# PCB_KioskMB_r3_4-01.net
KiCad netlist of a schematic drawn in EAGLE
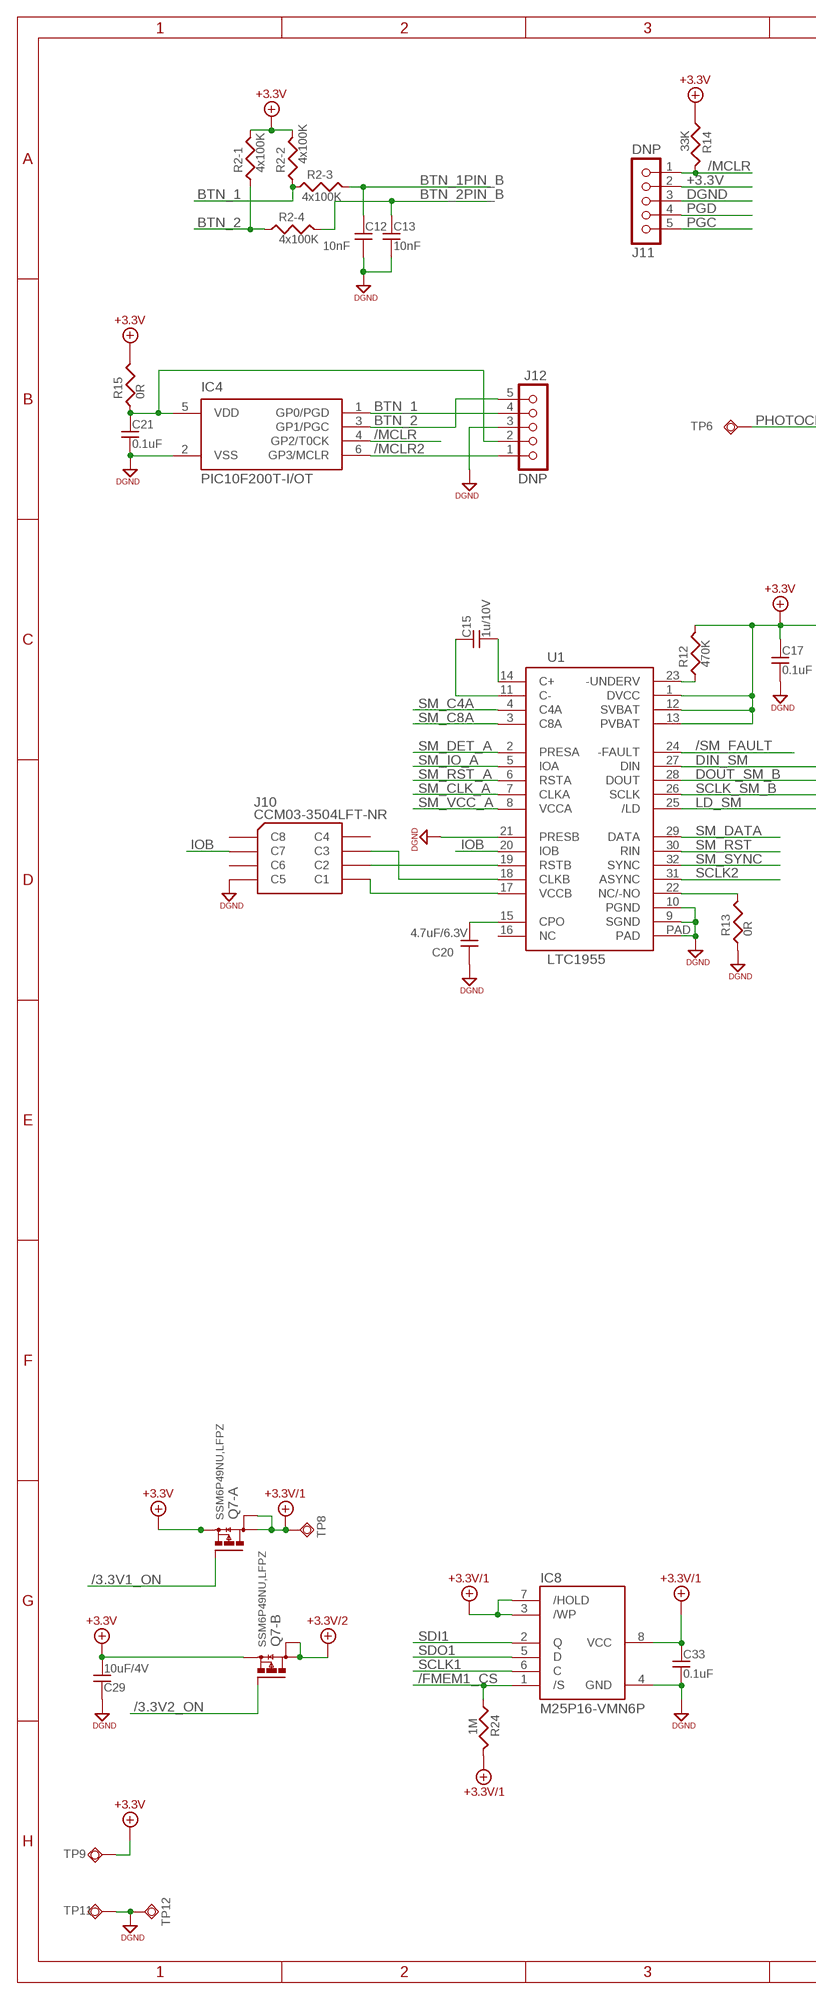
[diagram p0: schematic, sheet 1, part 1 of 2]
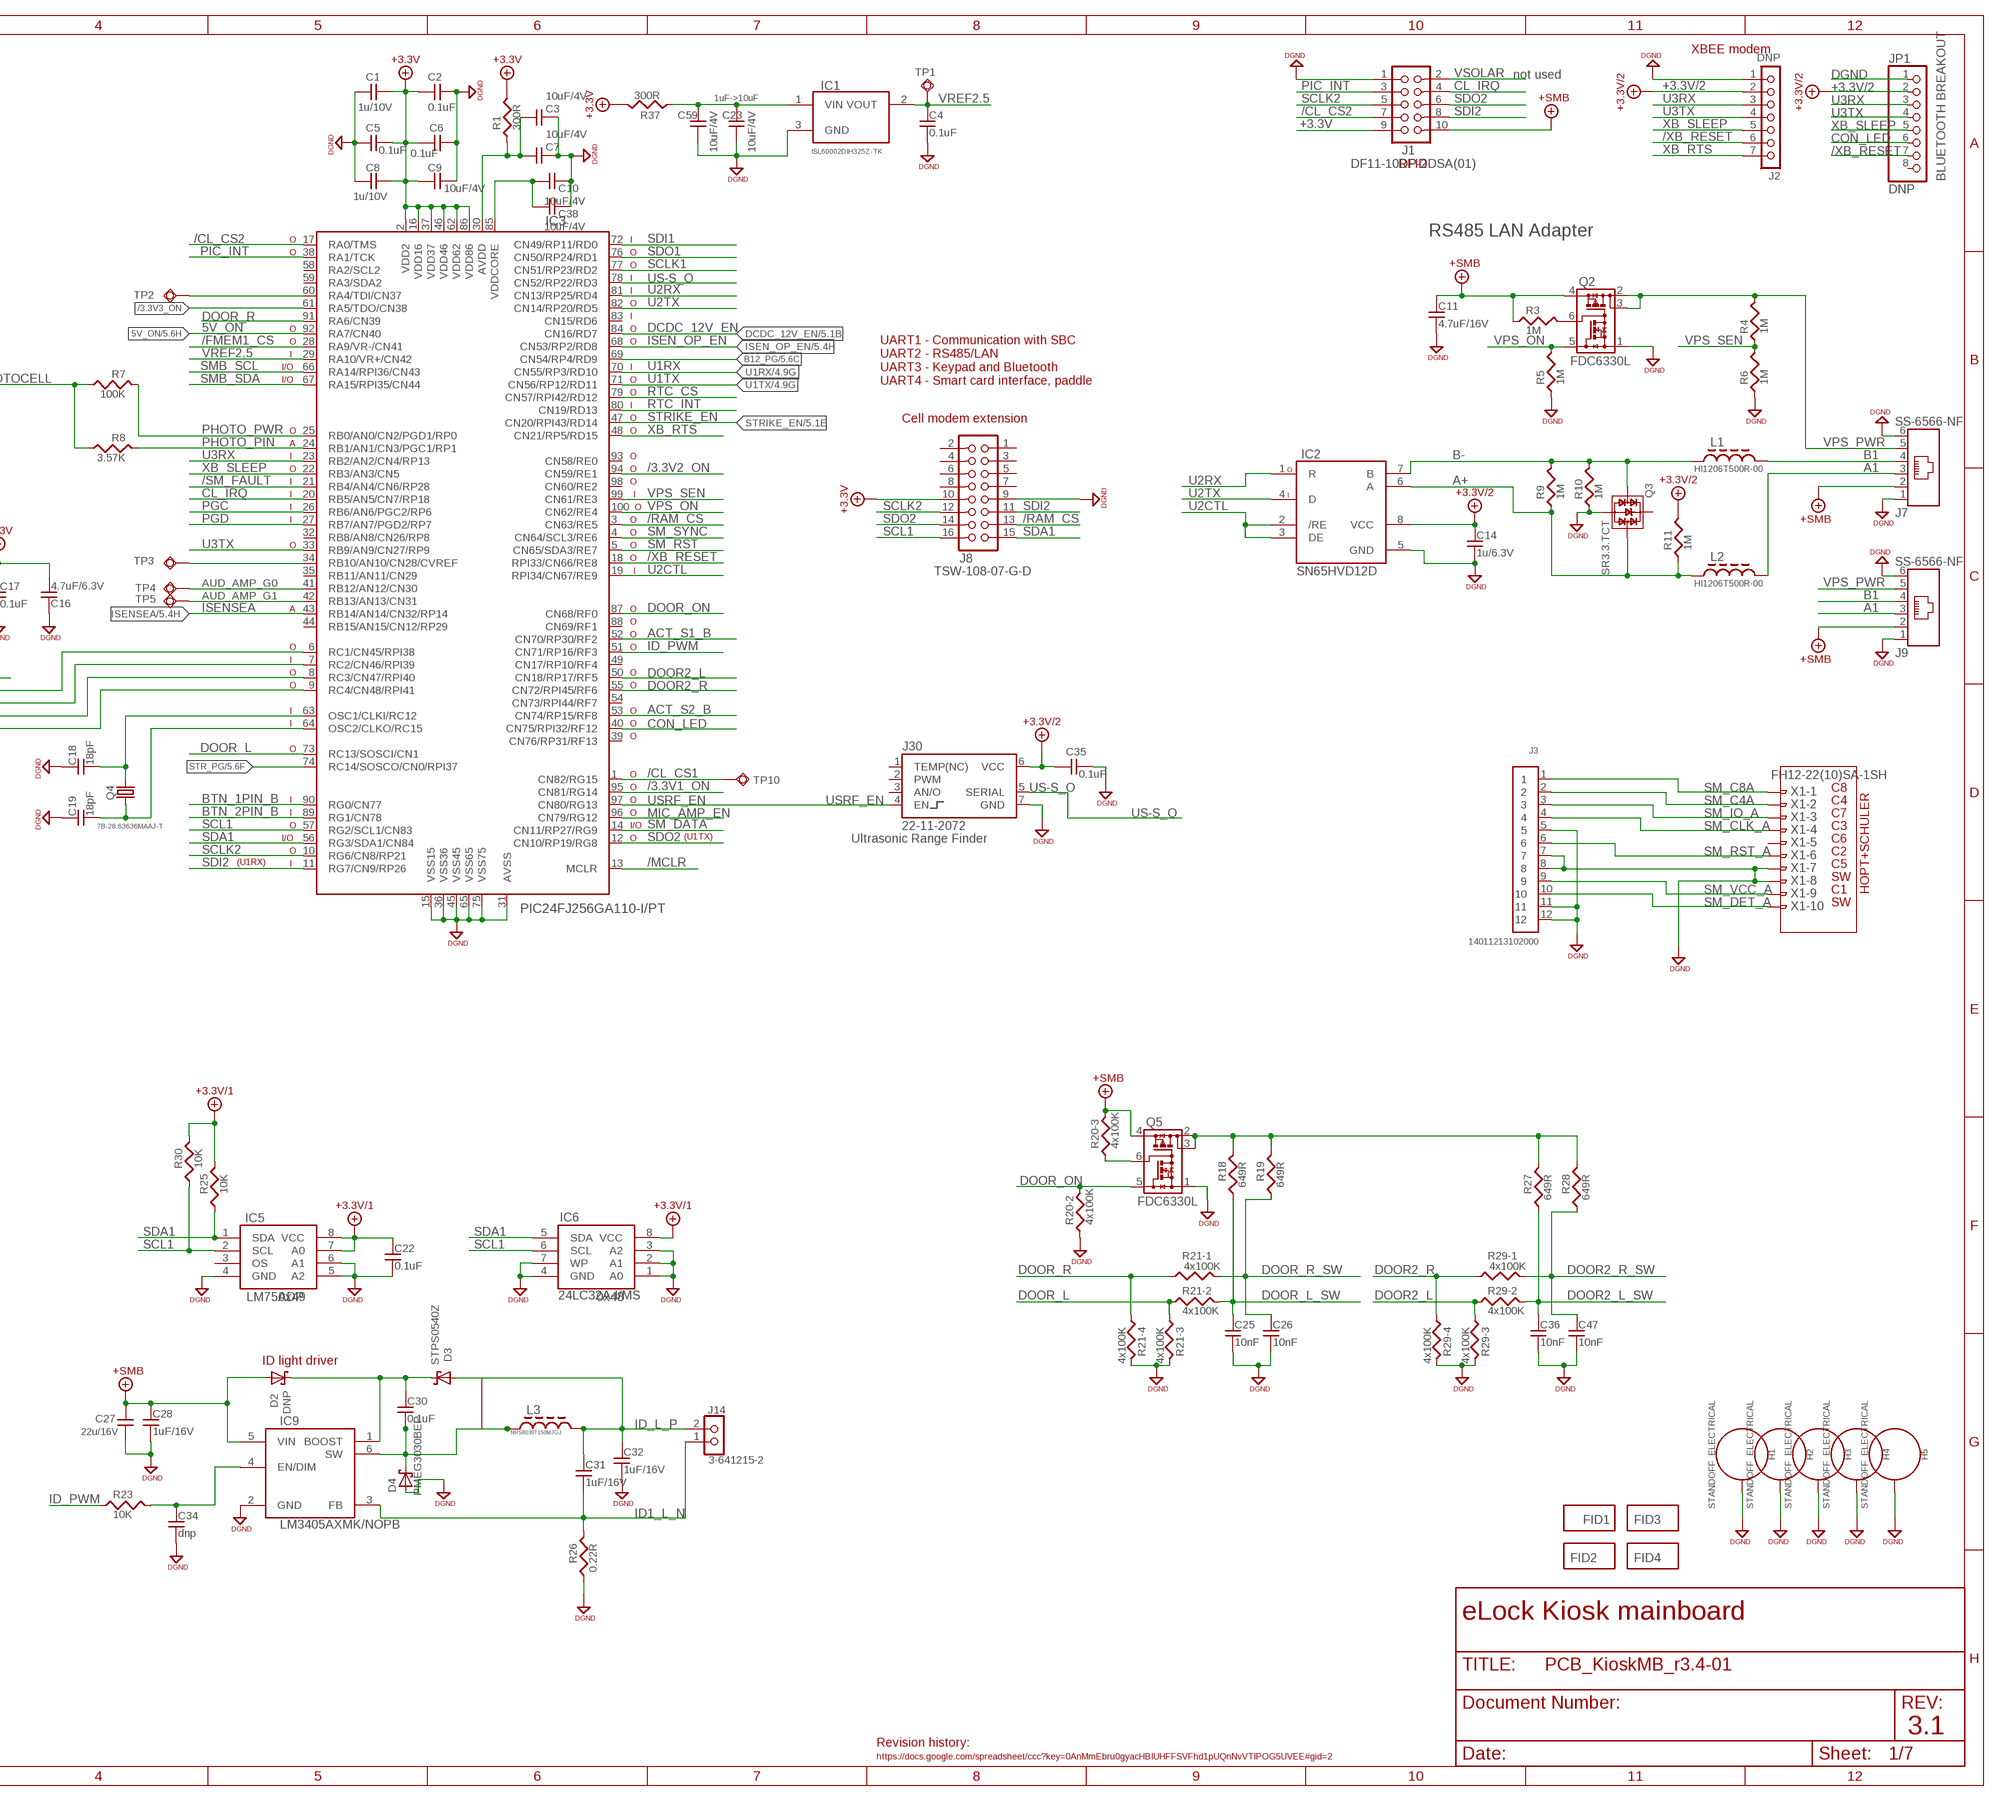
[diagram p1: schematic, sheet 1, part 2 of 2]
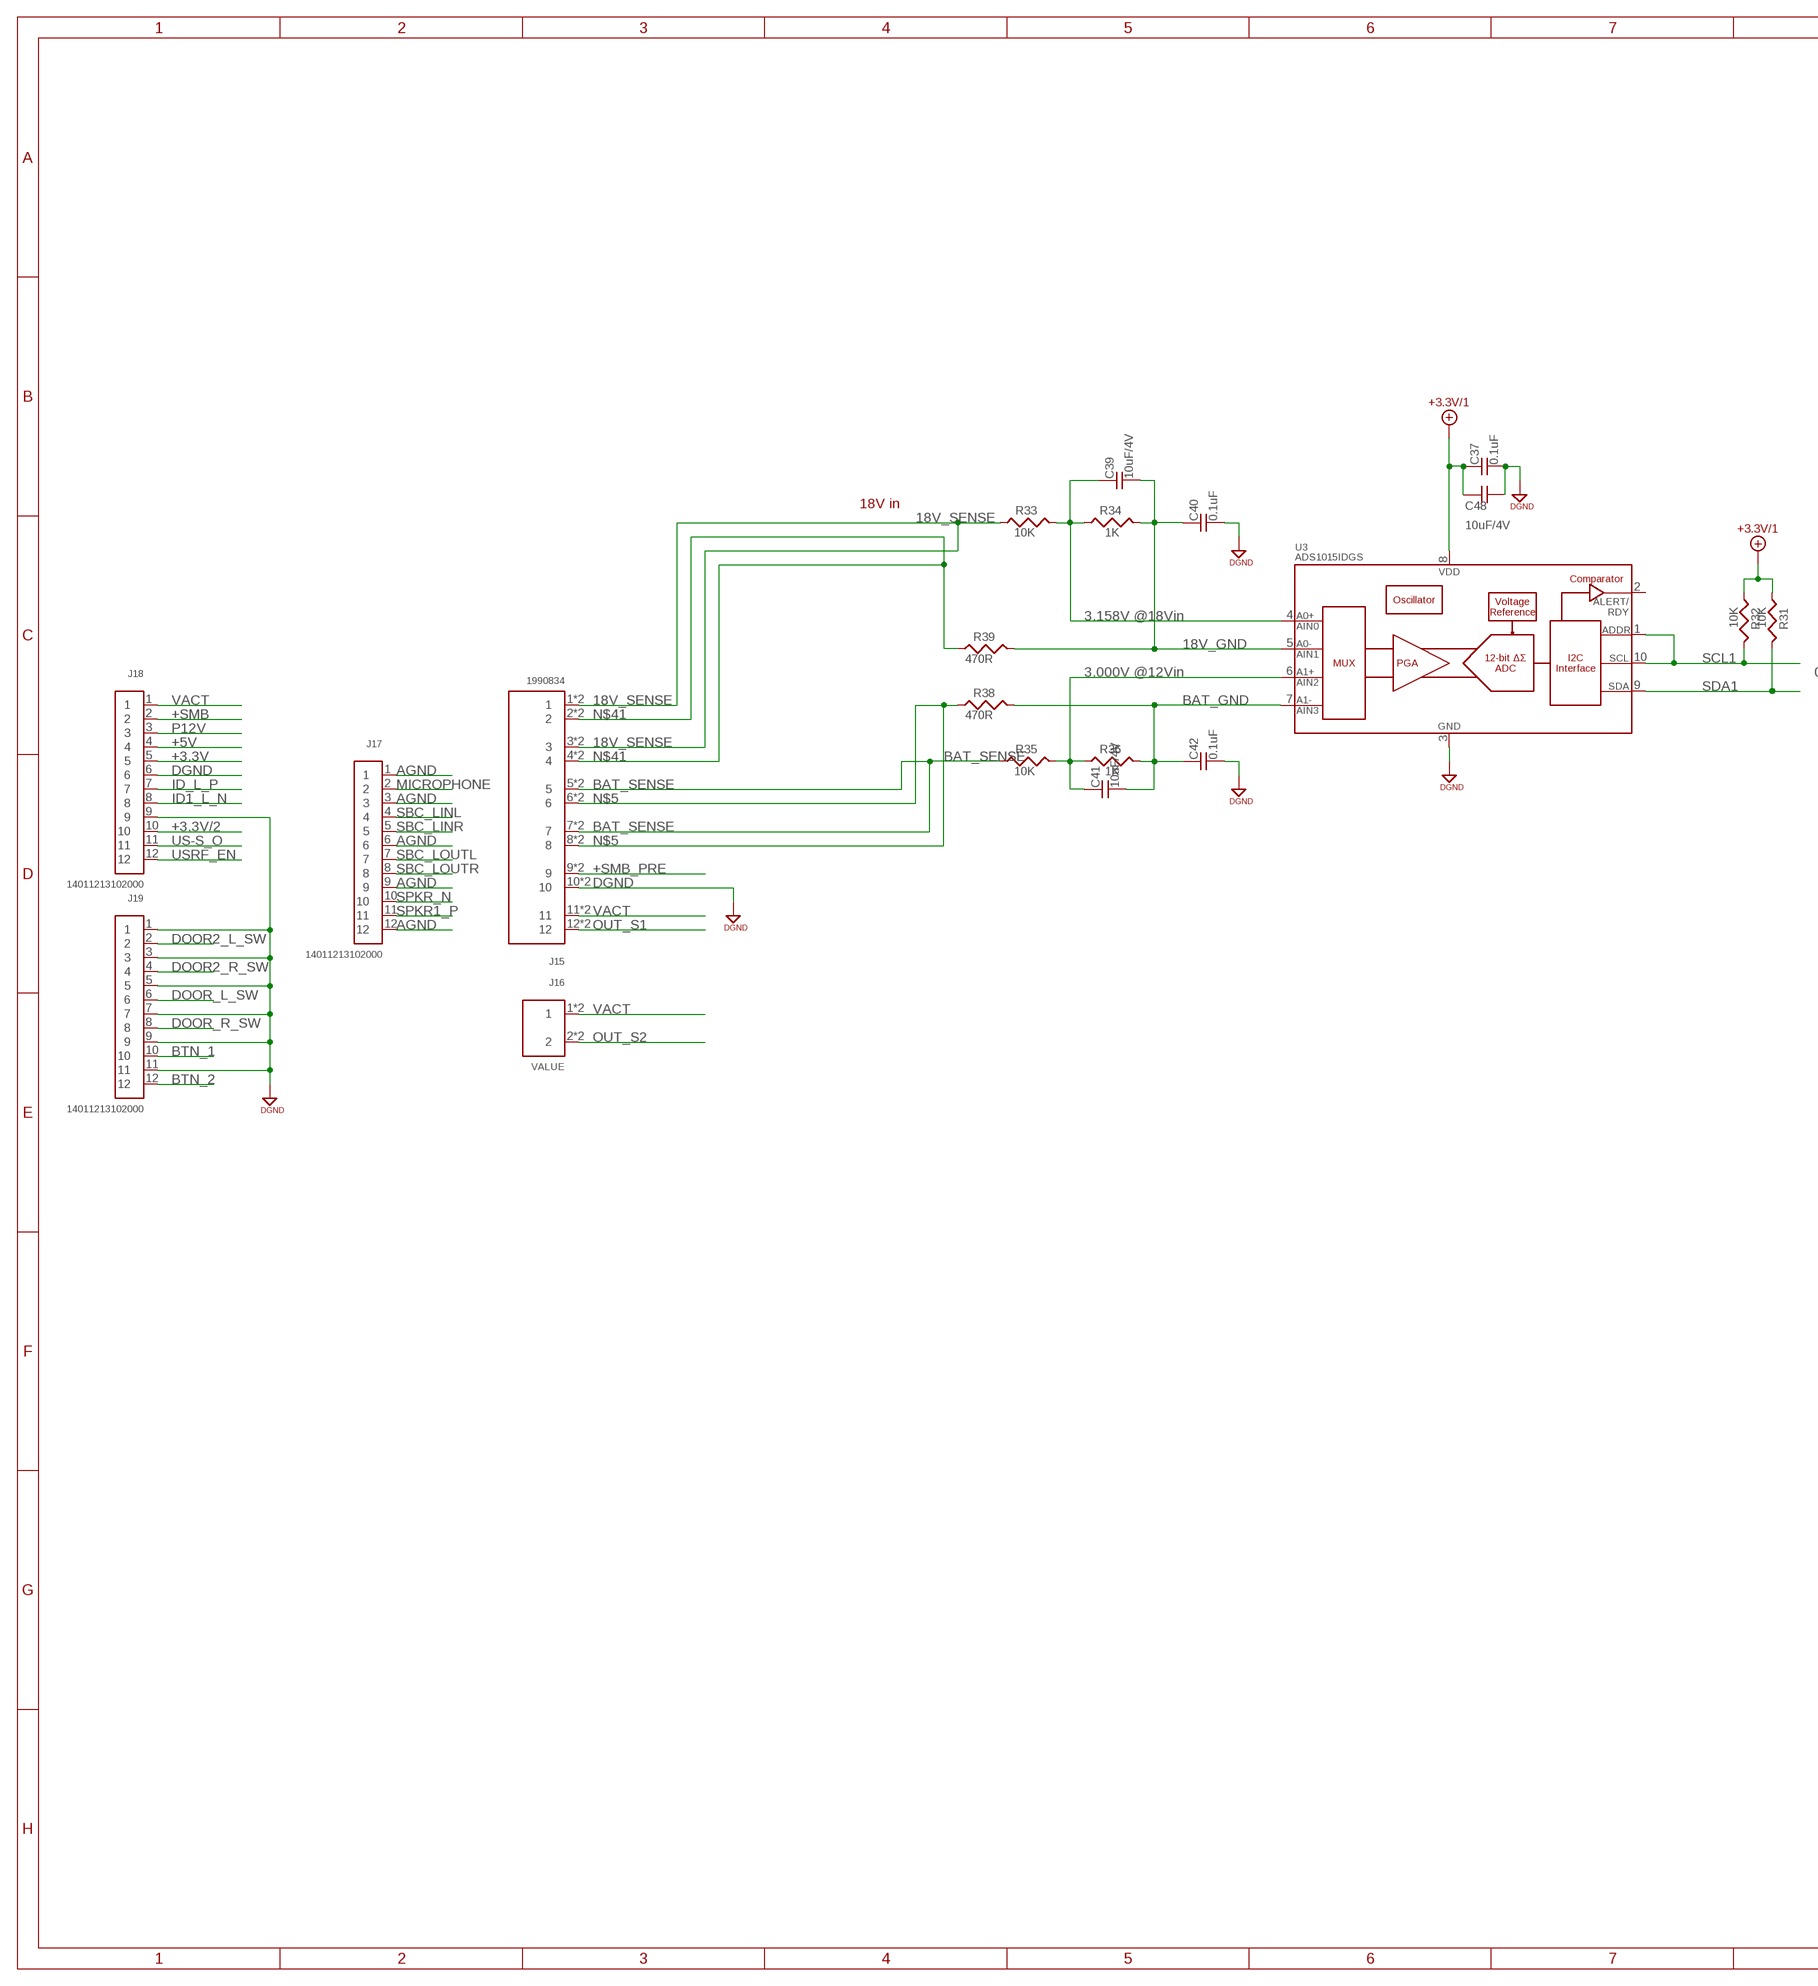
[diagram p2: schematic, sheet 2, part 1 of 2]
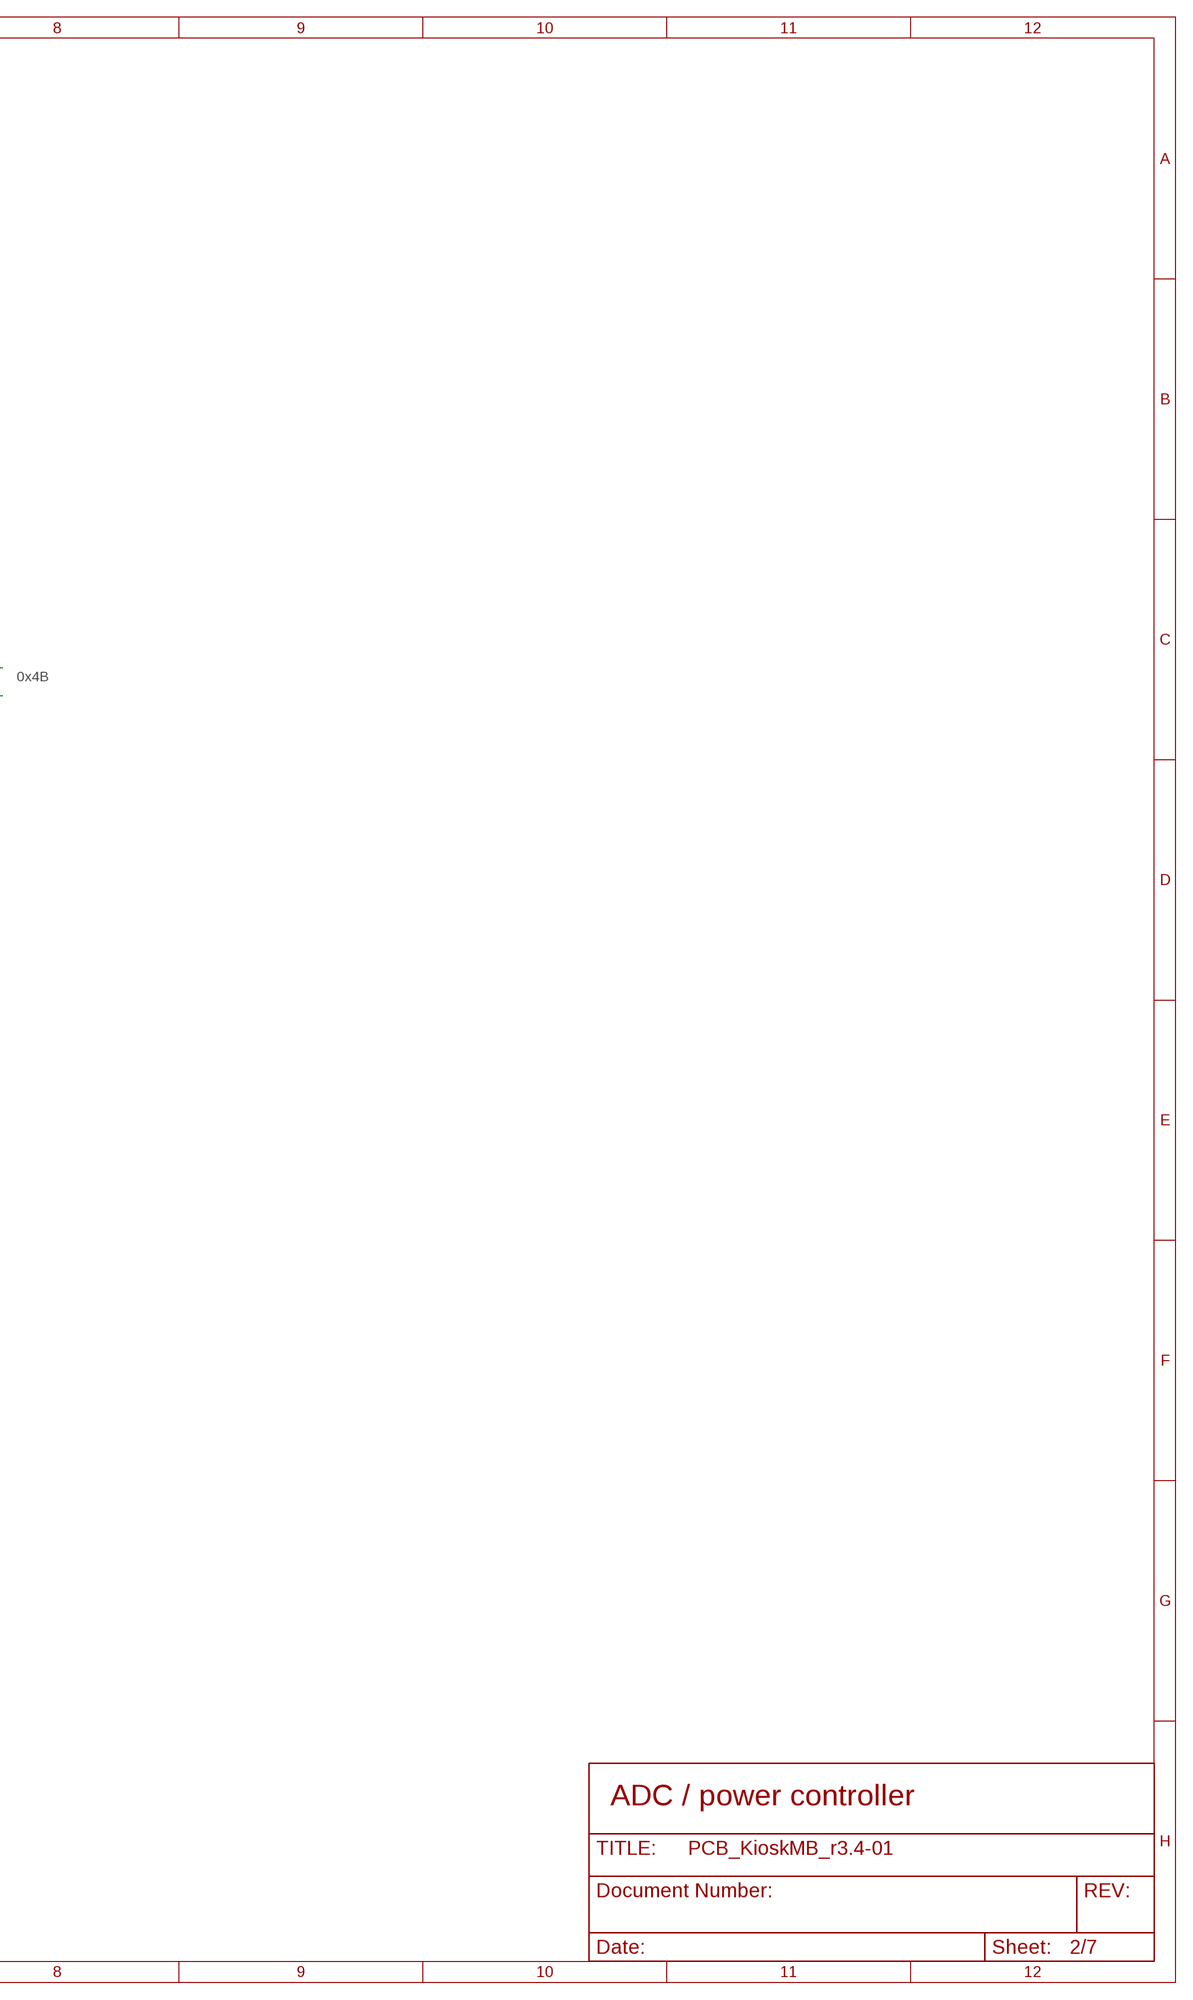
[diagram p3: schematic, sheet 2, part 2 of 2]
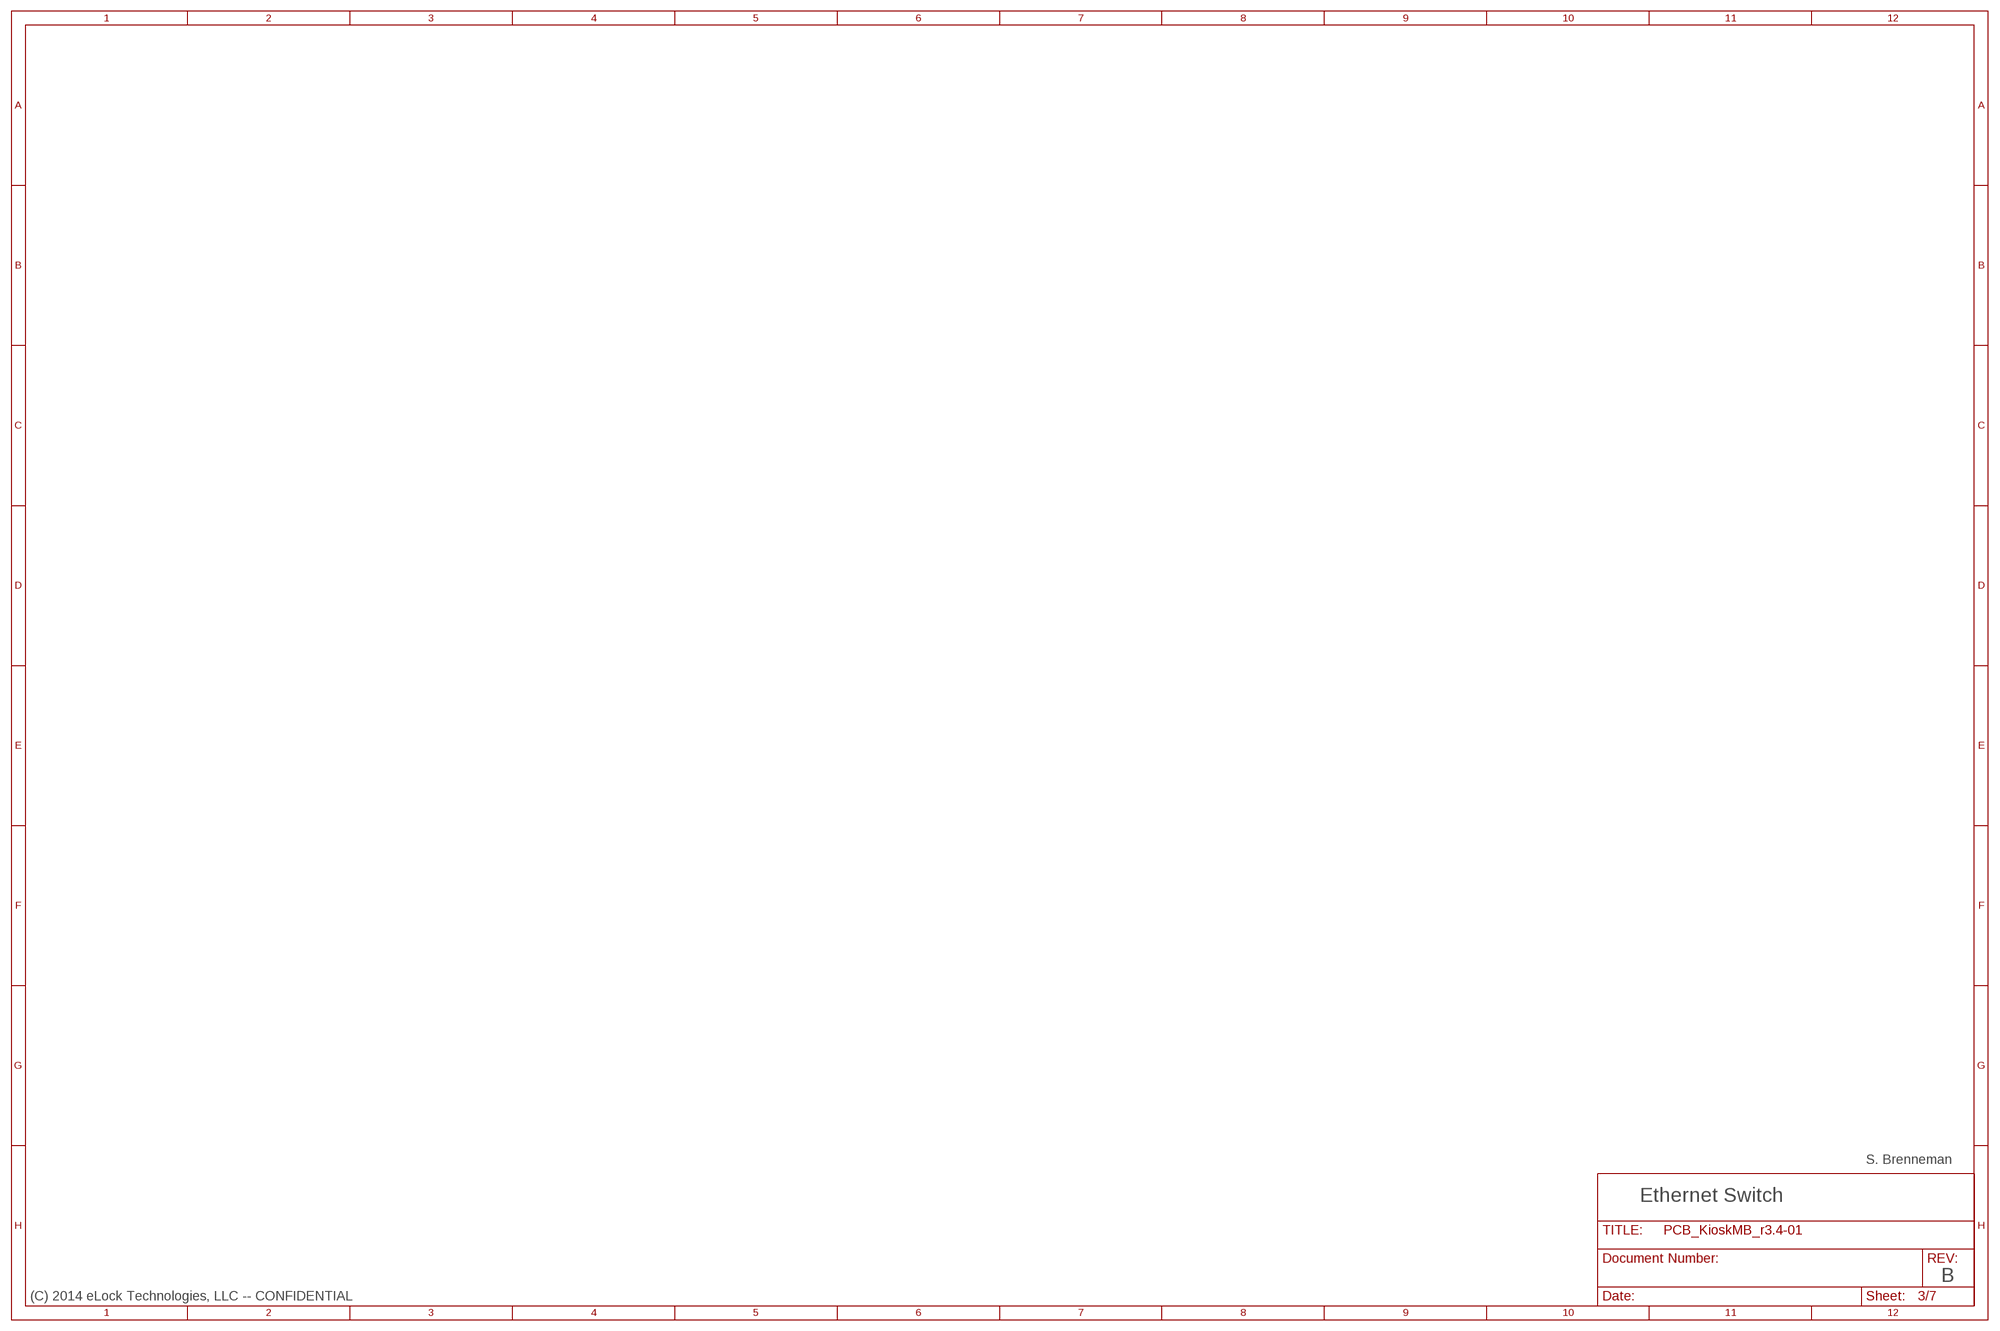
[diagram p4: schematic, sheet 3]
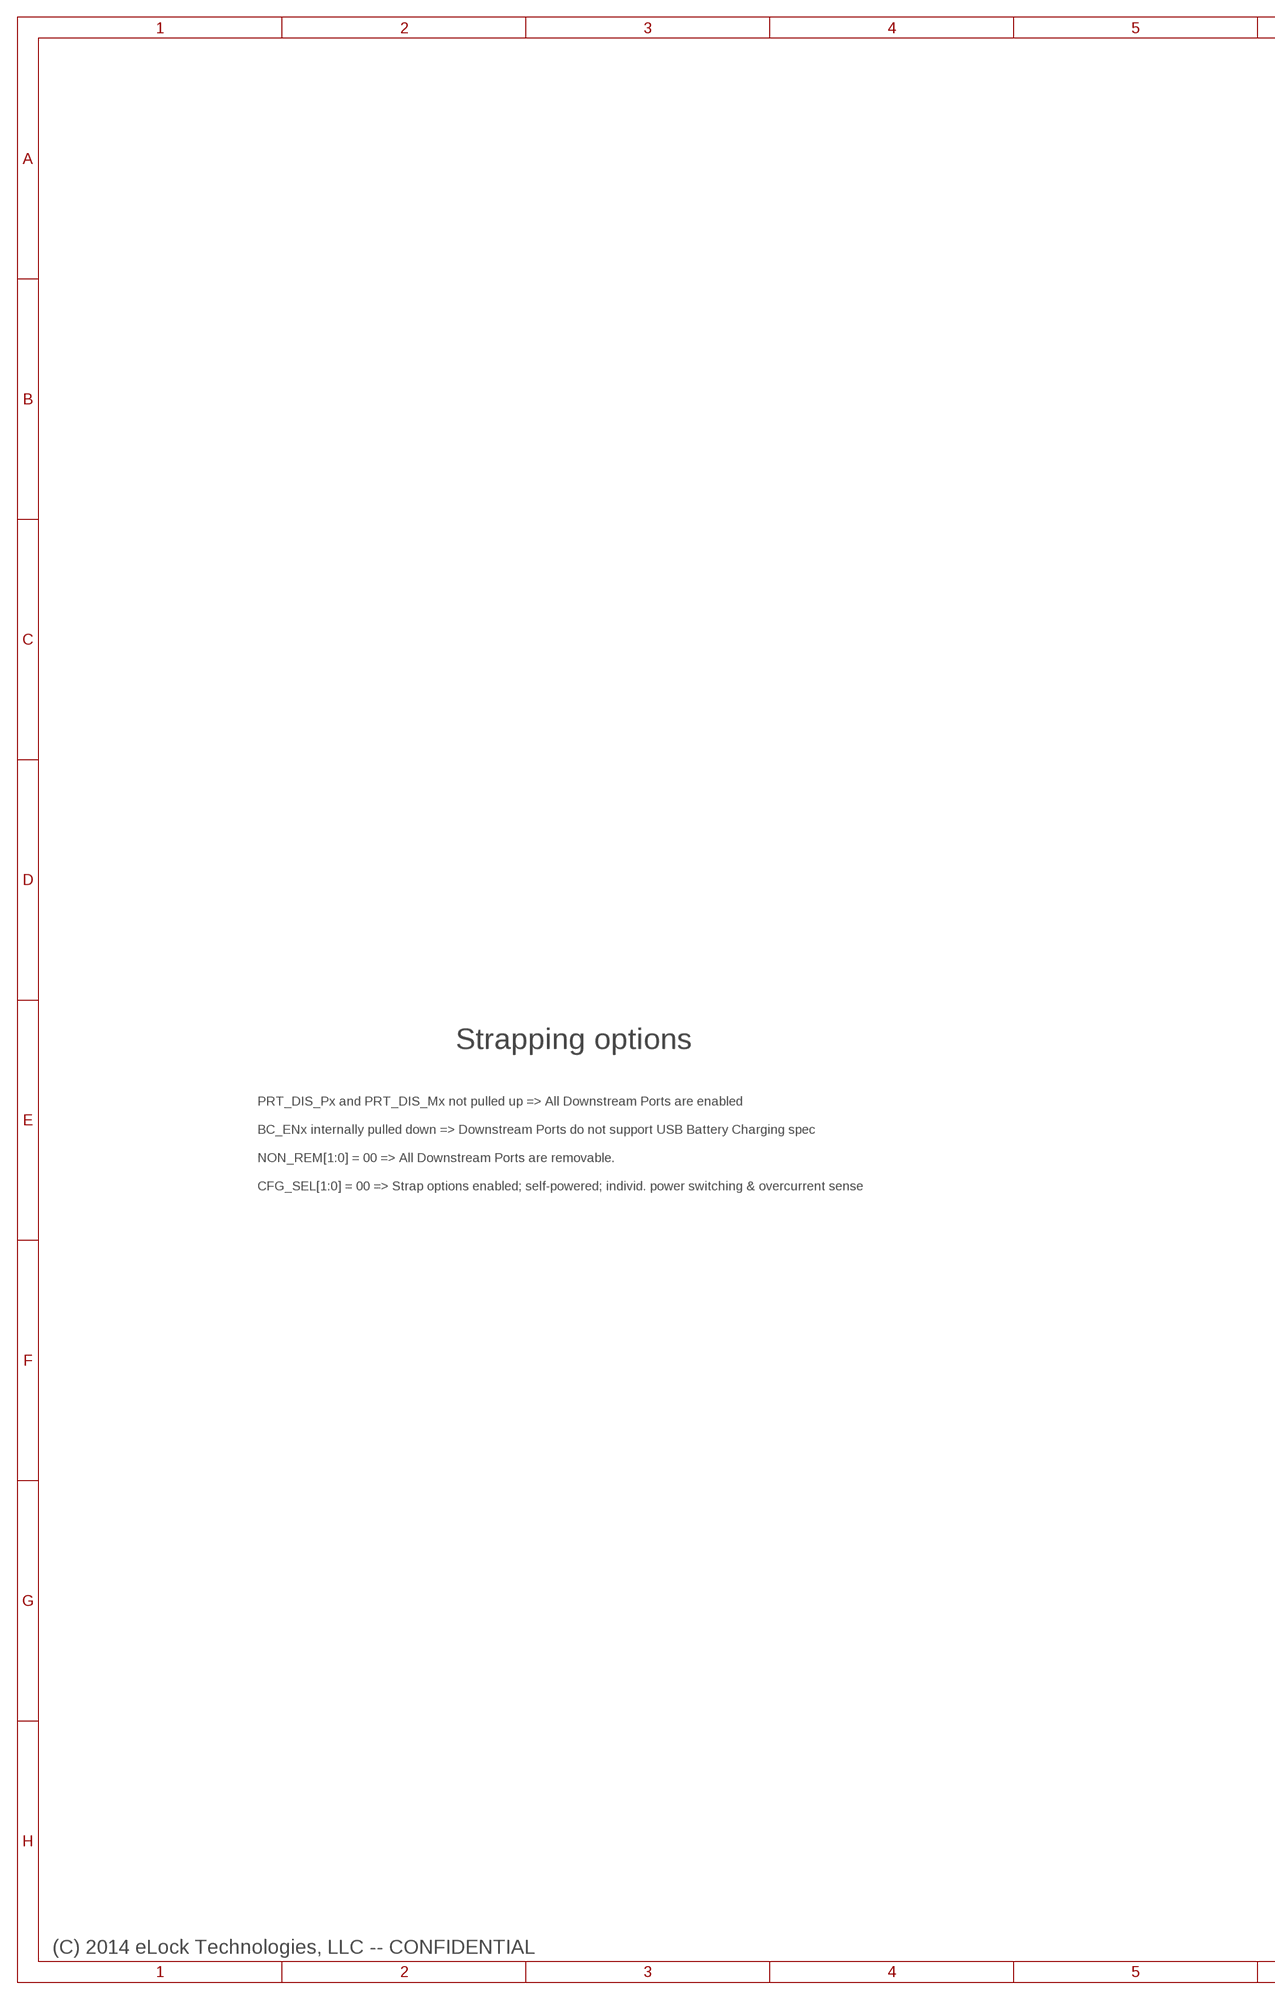
[diagram p5: schematic, sheet 4, part 1 of 2]
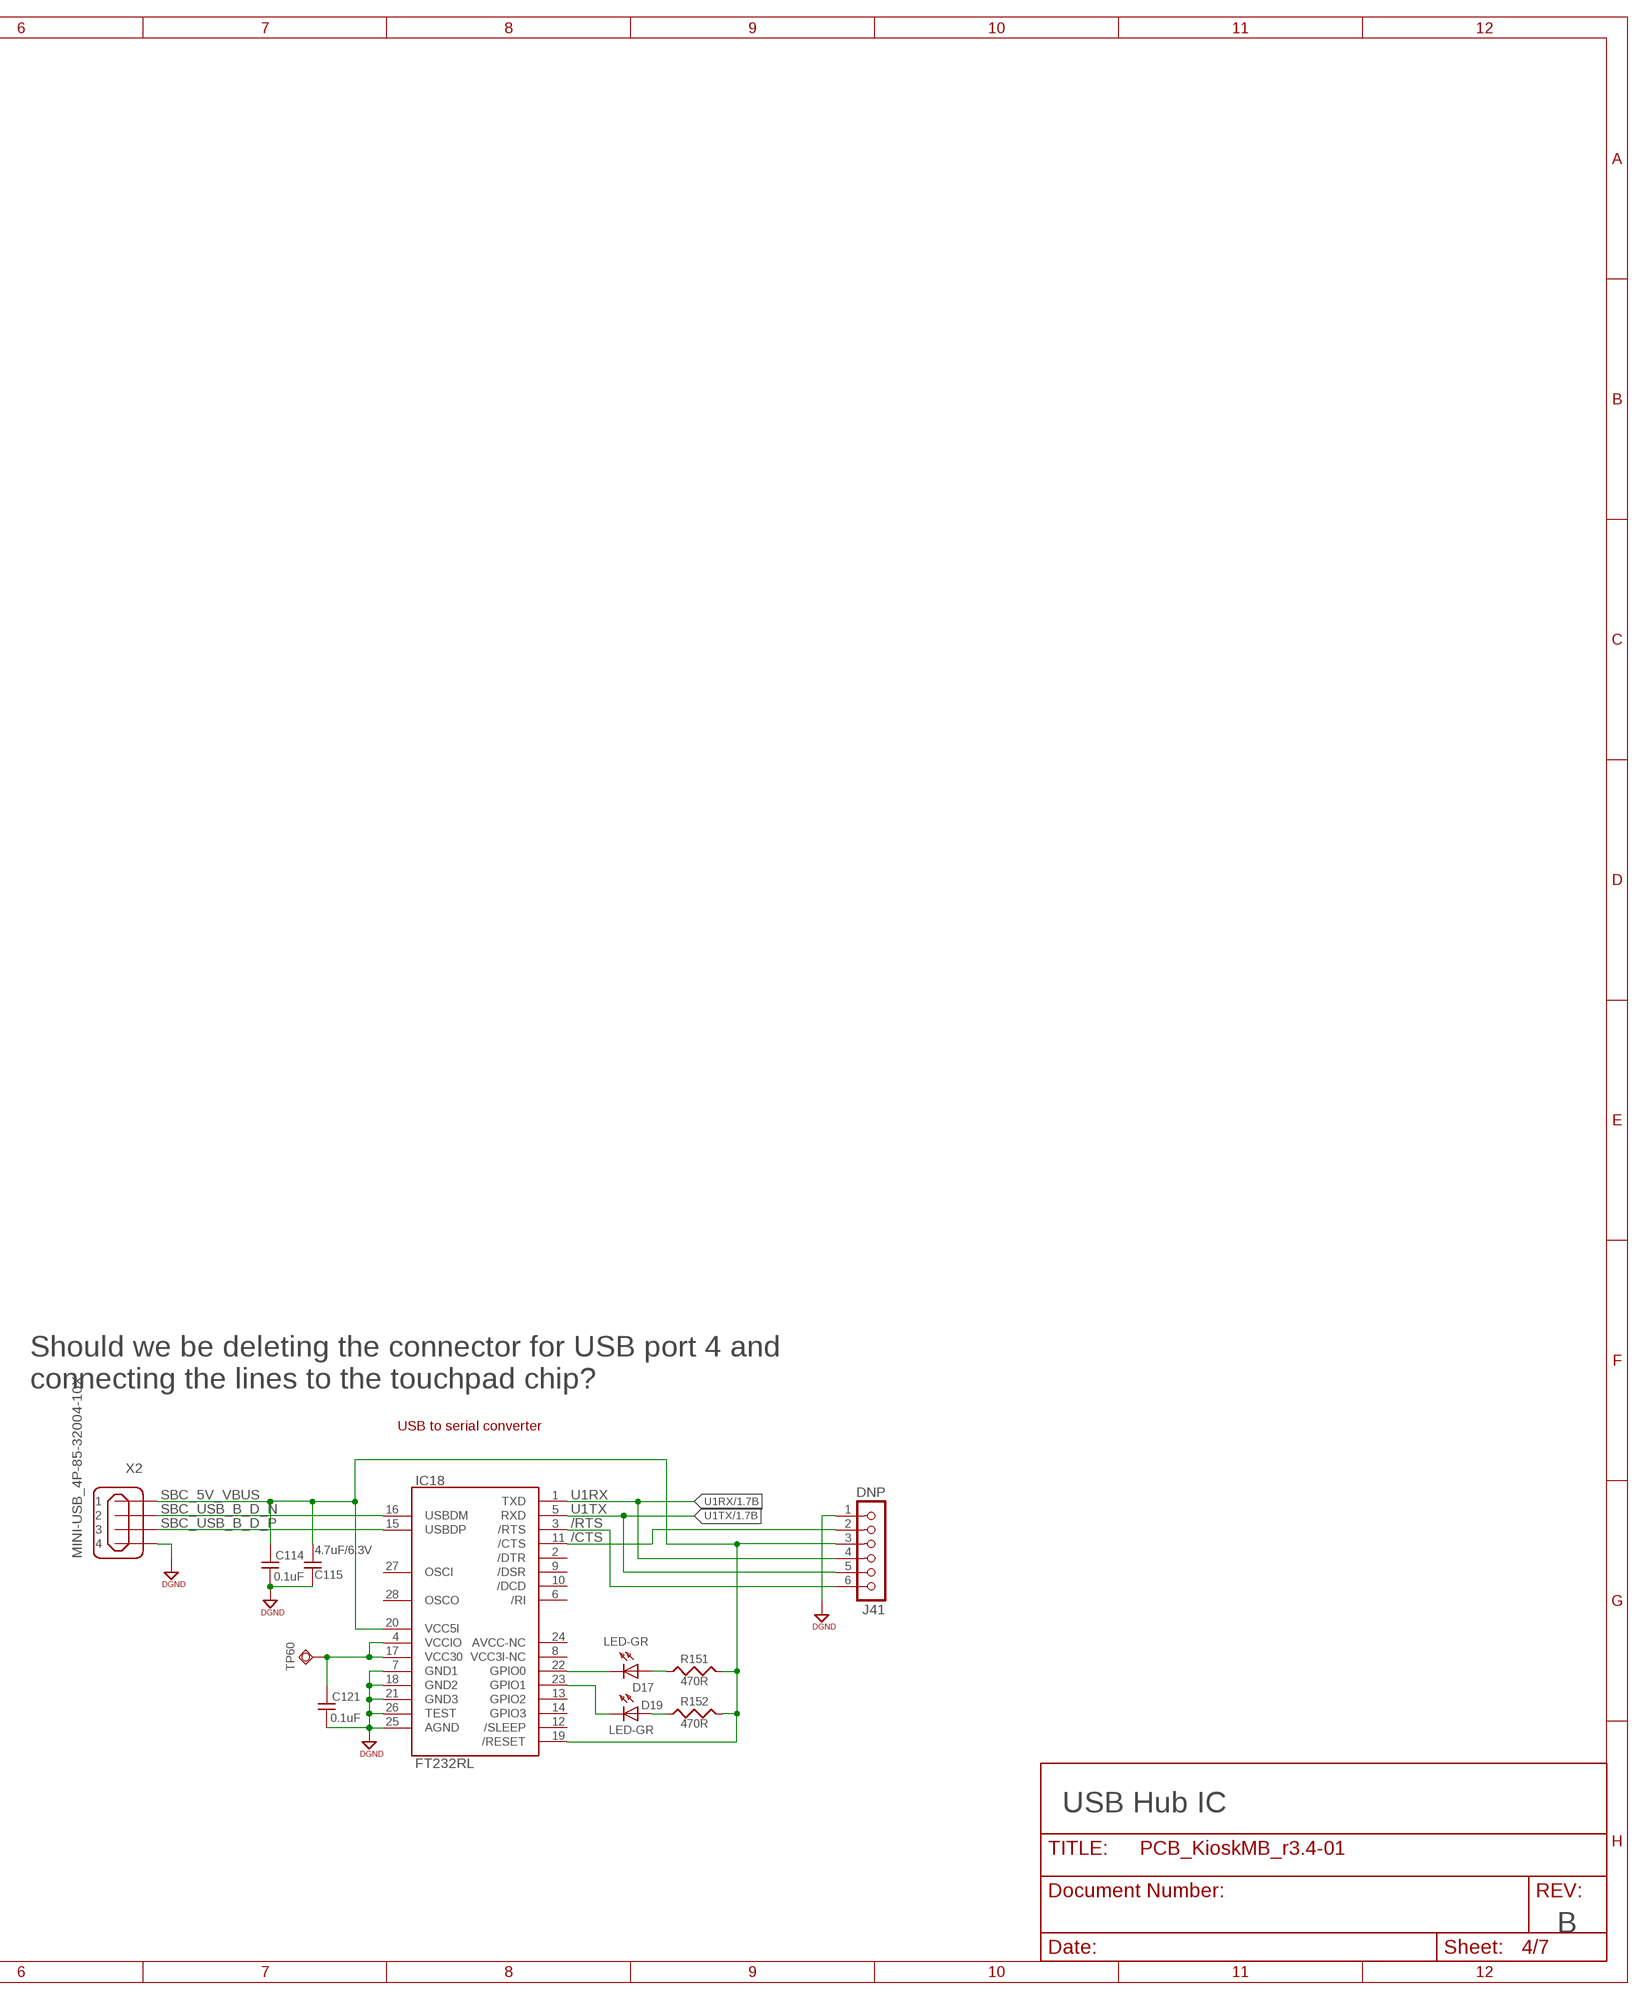
[diagram p6: schematic, sheet 4, part 2 of 2]
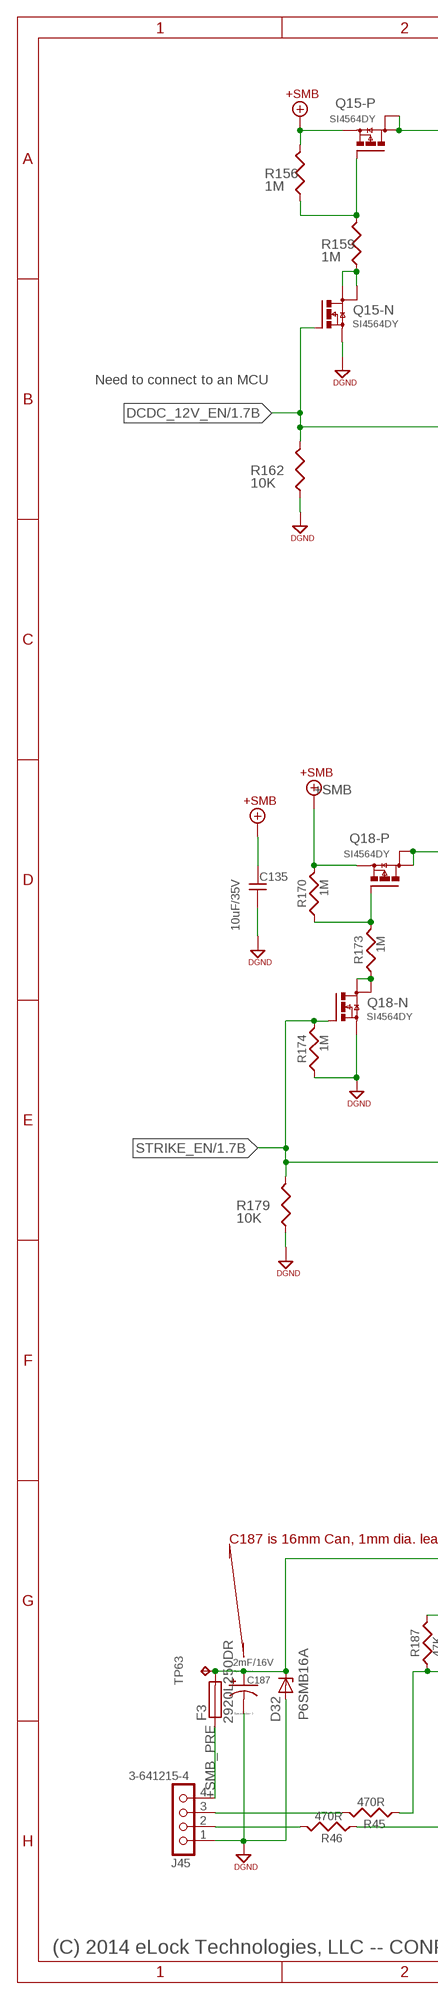
[diagram p7: schematic, sheet 5, part 1 of 2]
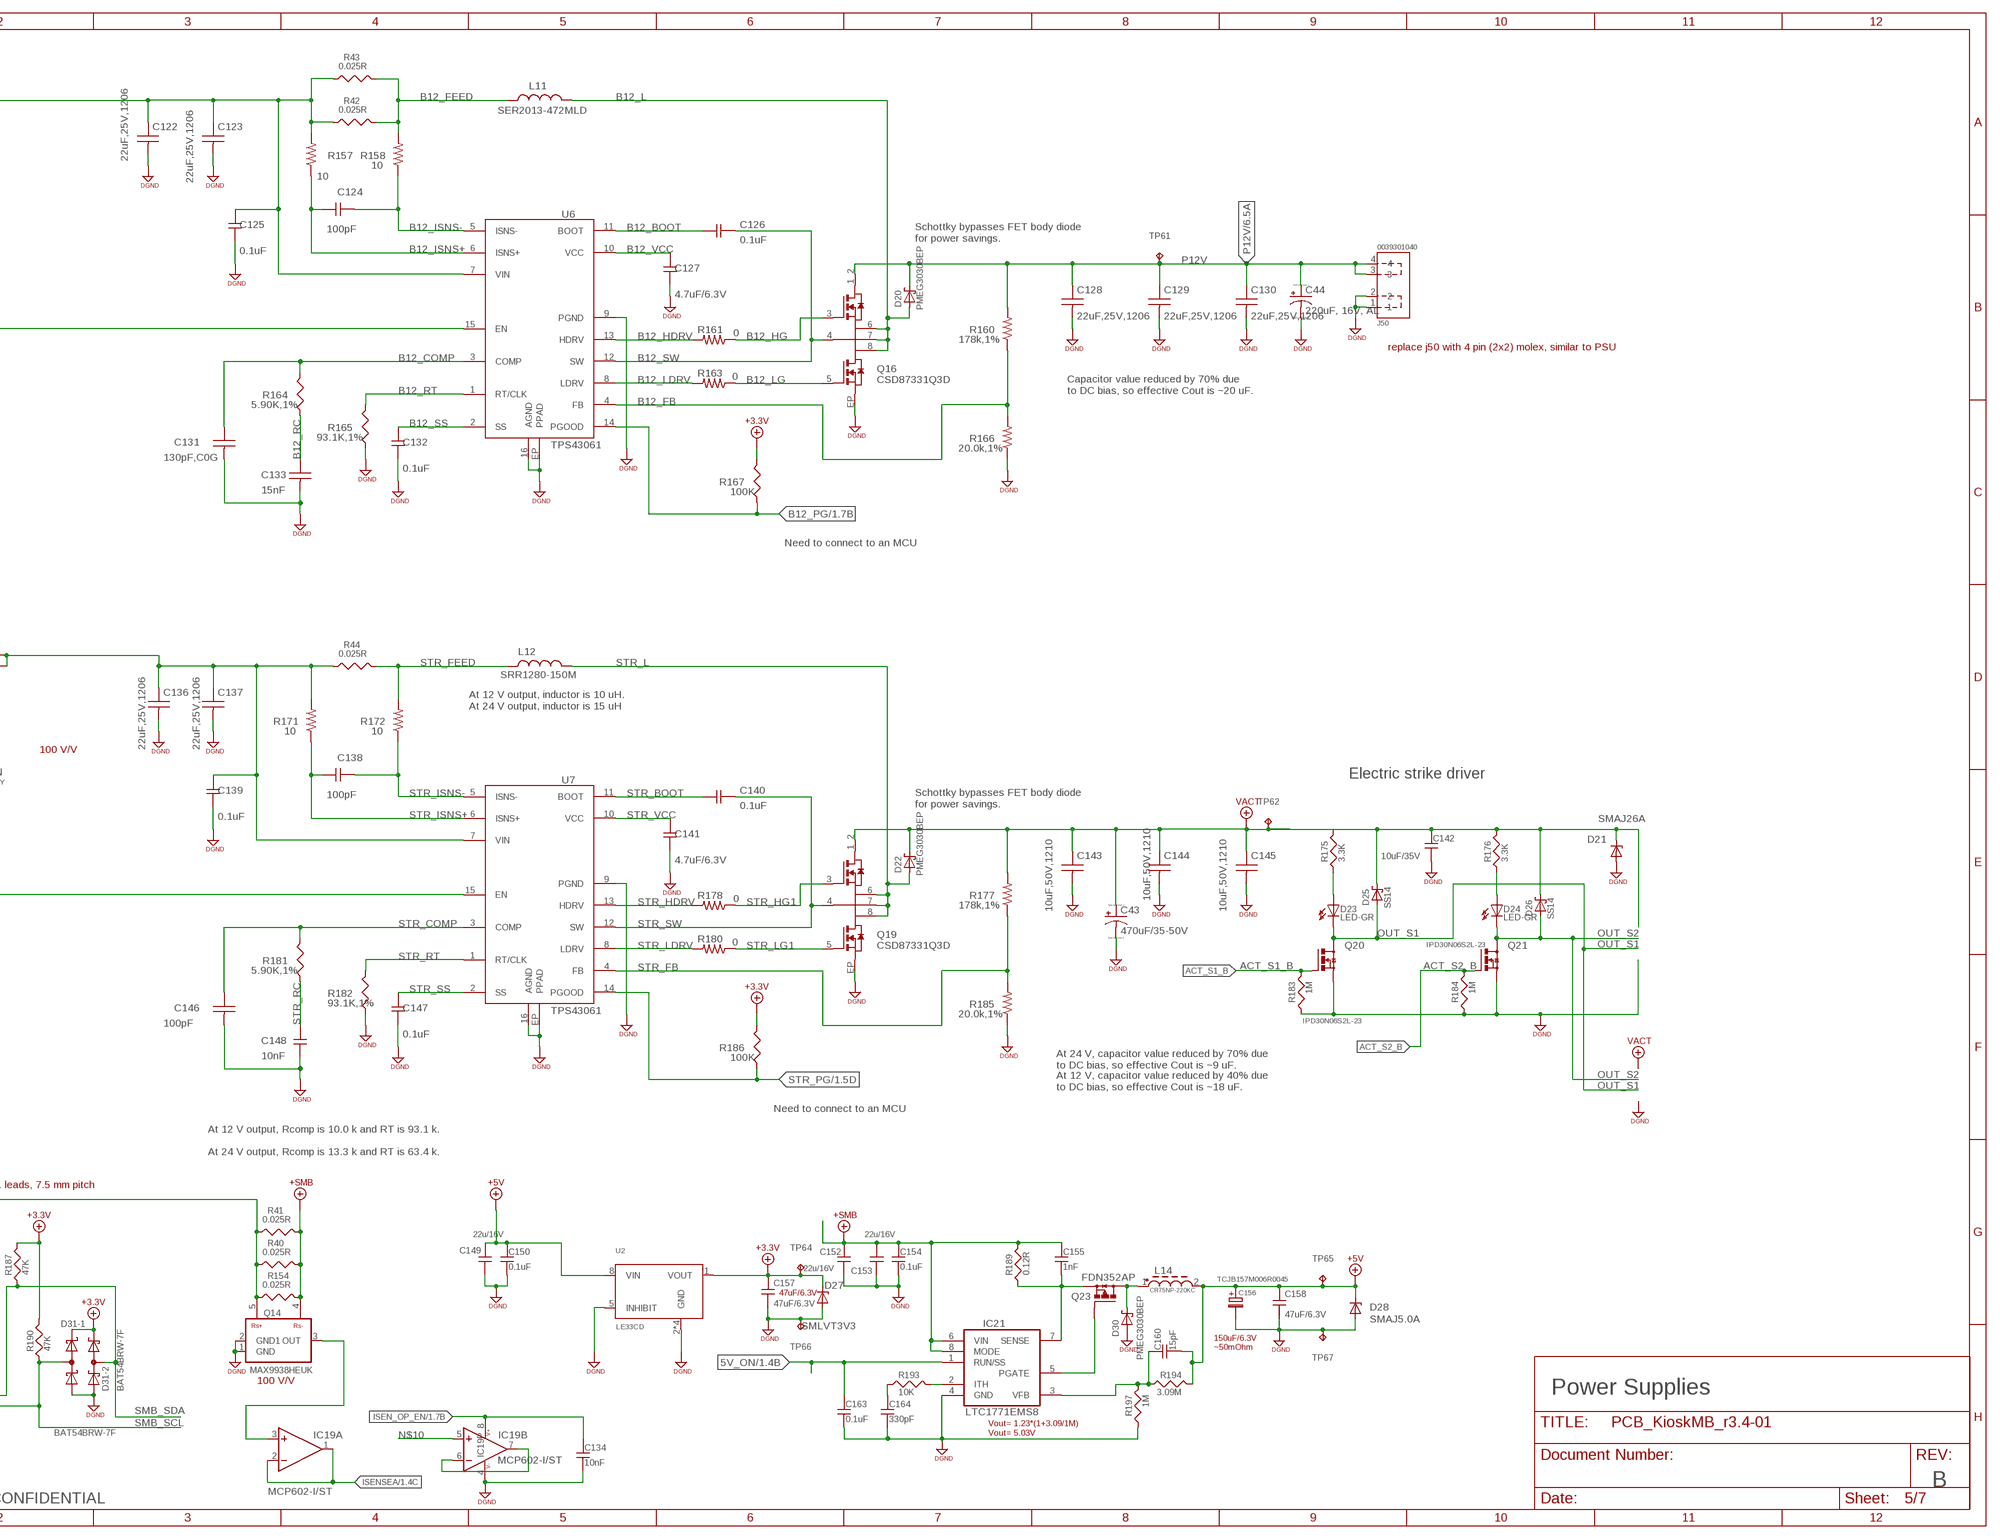
[diagram p8: schematic, sheet 5, part 2 of 2]
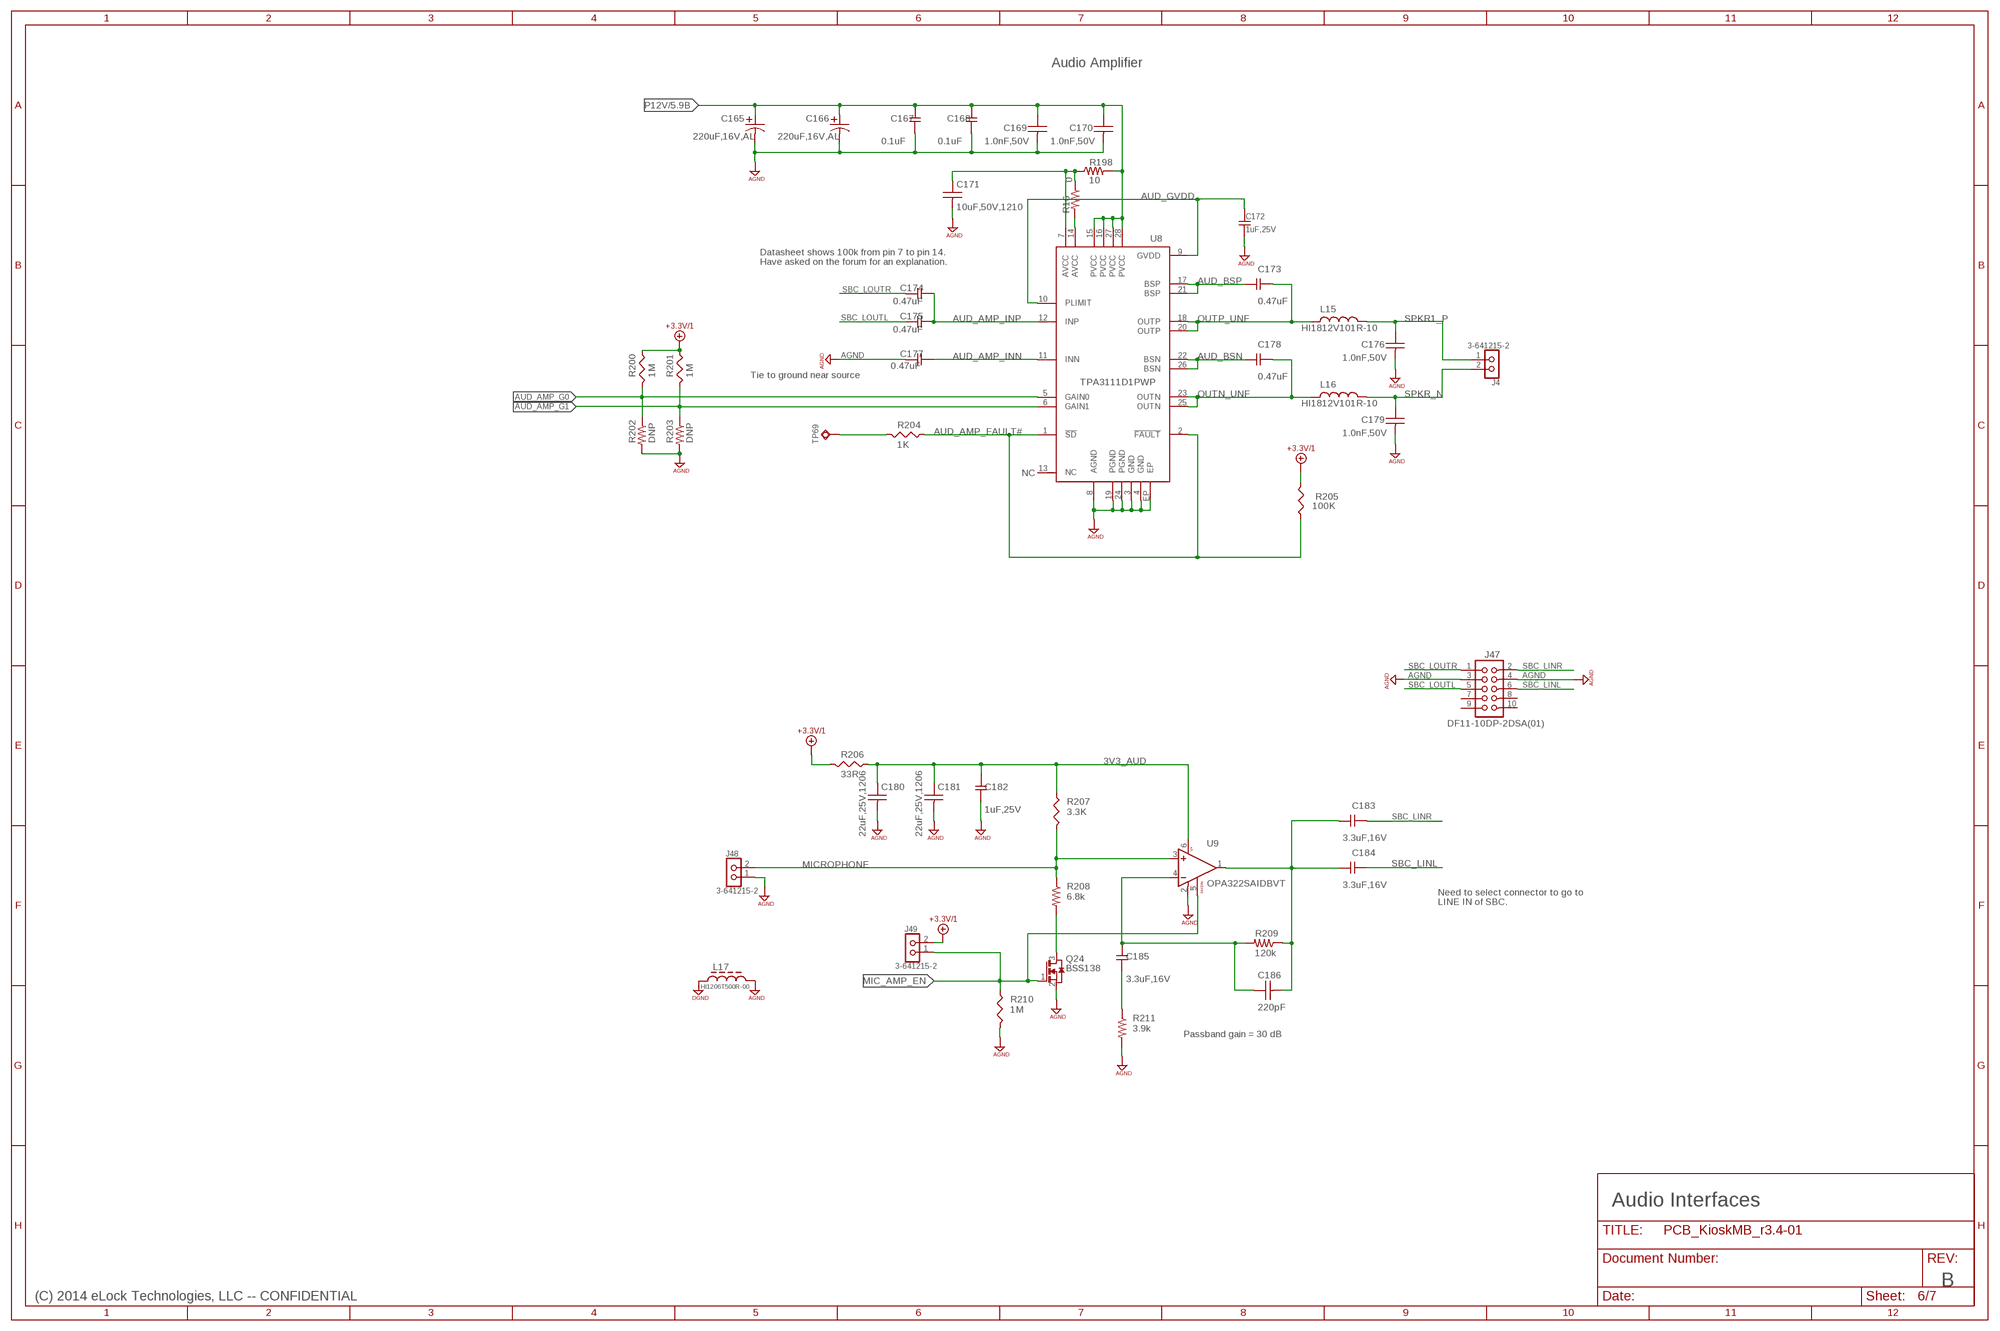
[diagram p9: schematic, sheet 6]
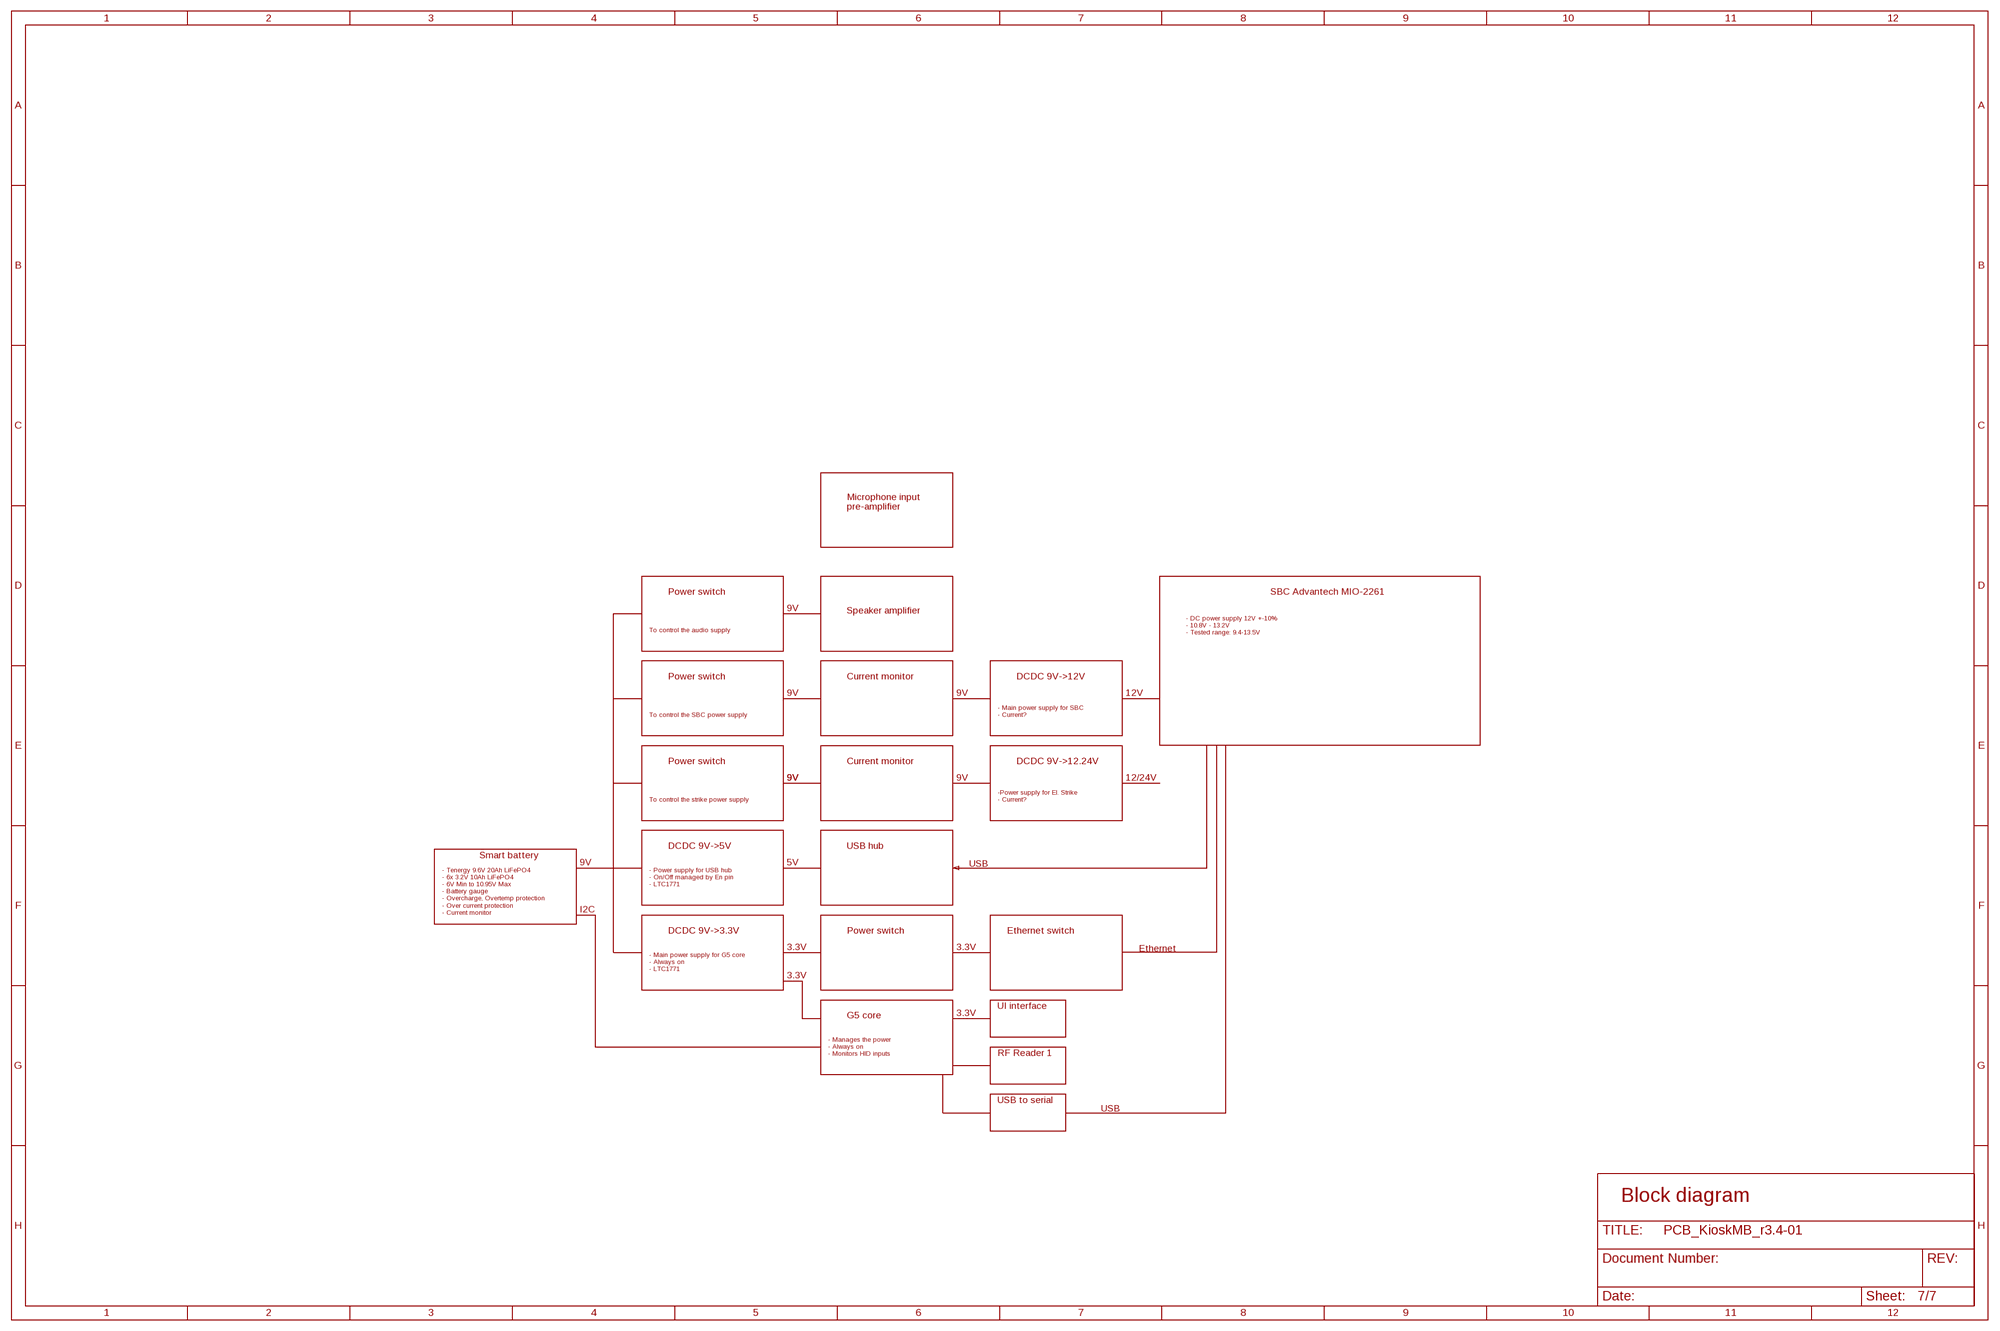
[diagram p10: schematic, sheet 7]

(export (version "E")
  (design (tool "Eeschema 10.0.6"))
  (components
    (comp (ref "C114")
      (value "0.1uF")
      (footprint "eagle-import:0603")
      (libsource (lib "eagle-import") (part "discrete_211_C-0603"))
    )
    (comp (ref "C115")
      (value "4.7uF/6.3V")
      (footprint "eagle-import:0603")
      (libsource (lib "eagle-import") (part "discrete_211_C-0603"))
    )
    (comp (ref "C121")
      (value "0.1uF")
      (footprint "eagle-import:0603")
      (libsource (lib "eagle-import") (part "discrete_211_C-0603"))
    )
    (comp (ref "D17")
      (value "LED-GR")
      (footprint "eagle-import:0805-POL")
      (libsource (lib "eagle-import") (part "LED-0805"))
    )
    (comp (ref "D19")
      (value "LED-GR")
      (footprint "eagle-import:0805-POL")
      (libsource (lib "eagle-import") (part "LED-0805"))
    )
    (comp (ref "IC18")
      (value "FT232RL")
      (footprint "eagle-import:SSOP28DB")
      (libsource (lib "eagle-import") (part "FT232RL"))
    )
    (comp (ref "J41")
      (value "DNP")
      (footprint "eagle-import:MA06-1")
      (libsource (lib "eagle-import") (part "MA06-1"))
    )
    (comp (ref "R151")
      (value "470R")
      (footprint "eagle-import:0603")
      (libsource (lib "eagle-import") (part "discrete_211_R-0603"))
    )
    (comp (ref "R152")
      (value "470R")
      (footprint "eagle-import:0603")
      (libsource (lib "eagle-import") (part "discrete_211_R-0603"))
    )
    (comp (ref "TP60")
      (value "ROUND_SMD0.7MM")
      (footprint "eagle-import:SMD_ROUND_07MM")
      (libsource (lib "eagle-import") (part "ROUND_SMD0.7MM"))
    )
    (comp (ref "X2")
      (value "MINI-USB_4P-85-32004-10X")
      (footprint "eagle-import:85-32004-10X")
      (libsource (lib "eagle-import") (part "MINI-USB_4P-85-32004-10X"))
    )
    (comp (ref "C1")
      (value "1u/10V")
      (footprint "eagle-import:0603")
      (libsource (lib "eagle-import") (part "discrete_211_C-0603"))
    )
    (comp (ref "C2")
      (value "0.1uF")
      (footprint "eagle-import:0603")
      (libsource (lib "eagle-import") (part "discrete_211_C-0603"))
    )
    (comp (ref "C3")
      (value "10uF/4V")
      (footprint "eagle-import:0603")
      (libsource (lib "eagle-import") (part "discrete_211_C-0603"))
    )
    (comp (ref "C4")
      (value "0.1uF")
      (footprint "eagle-import:0603")
      (libsource (lib "eagle-import") (part "discrete_211_C-0603"))
    )
    (comp (ref "C5")
      (value "0.1uF")
      (footprint "eagle-import:0603")
      (libsource (lib "eagle-import") (part "discrete_211_C-0603"))
    )
    (comp (ref "C6")
      (value "0.1uF")
      (footprint "eagle-import:0603")
      (libsource (lib "eagle-import") (part "discrete_211_C-0603"))
    )
    (comp (ref "C7")
      (value "10uF/4V")
      (footprint "eagle-import:0603")
      (libsource (lib "eagle-import") (part "discrete_211_C-0603"))
    )
    (comp (ref "C8")
      (value "1u/10V")
      (footprint "eagle-import:0603")
      (libsource (lib "eagle-import") (part "discrete_211_C-0603"))
    )
    (comp (ref "C9")
      (value "10uF/4V")
      (footprint "eagle-import:0603")
      (libsource (lib "eagle-import") (part "discrete_211_C-0603"))
    )
    (comp (ref "C10")
      (value "10uF/4V")
      (footprint "eagle-import:0603")
      (libsource (lib "eagle-import") (part "discrete_211_C-0603"))
    )
    (comp (ref "C11")
      (value "4.7uF/16V")
      (footprint "eagle-import:0805")
      (libsource (lib "eagle-import") (part "C-0805"))
    )
    (comp (ref "C12")
      (value "10nF")
      (footprint "eagle-import:0603")
      (libsource (lib "eagle-import") (part "discrete_211_C-0603"))
    )
    (comp (ref "C13")
      (value "10nF")
      (footprint "eagle-import:0603")
      (libsource (lib "eagle-import") (part "discrete_211_C-0603"))
    )
    (comp (ref "C14")
      (value "1u/6.3V")
      (footprint "eagle-import:0603")
      (libsource (lib "eagle-import") (part "discrete_211_C-0603"))
    )
    (comp (ref "C15")
      (value "1u/10V")
      (footprint "eagle-import:0603")
      (libsource (lib "eagle-import") (part "discrete_211_C-0603"))
    )
    (comp (ref "C16")
      (value "4.7uF/6.3V")
      (footprint "eagle-import:0603")
      (libsource (lib "eagle-import") (part "discrete_211_C-0603"))
    )
    (comp (ref "C17")
      (value "0.1uF")
      (footprint "eagle-import:0603")
      (libsource (lib "eagle-import") (part "discrete_211_C-0603"))
    )
    (comp (ref "C18")
      (value "18pF")
      (footprint "eagle-import:0603")
      (libsource (lib "eagle-import") (part "discrete_211_C-0603"))
    )
    (comp (ref "C19")
      (value "18pF")
      (footprint "eagle-import:0603")
      (libsource (lib "eagle-import") (part "discrete_211_C-0603"))
    )
    (comp (ref "C20")
      (value "4.7uF/6.3V")
      (footprint "eagle-import:0603")
      (libsource (lib "eagle-import") (part "discrete_211_C-0603"))
    )
    (comp (ref "C21")
      (value "0.1uF")
      (footprint "eagle-import:0603")
      (libsource (lib "eagle-import") (part "discrete_211_C-0603"))
    )
    (comp (ref "C22")
      (value "0.1uF")
      (footprint "eagle-import:0603")
      (libsource (lib "eagle-import") (part "discrete_211_C-0603"))
    )
    (comp (ref "C23")
      (value "10uF/4V")
      (footprint "eagle-import:0603")
      (libsource (lib "eagle-import") (part "discrete_211_C-0603"))
    )
    (comp (ref "C25")
      (value "10nF")
      (footprint "eagle-import:0603")
      (libsource (lib "eagle-import") (part "discrete_211_C-0603"))
    )
    (comp (ref "C26")
      (value "10nF")
      (footprint "eagle-import:0603")
      (libsource (lib "eagle-import") (part "discrete_211_C-0603"))
    )
    (comp (ref "C27")
      (value "22u/16V")
      (footprint "eagle-import:1210")
      (libsource (lib "eagle-import") (part "C-1210"))
    )
    (comp (ref "C28")
      (value "1uF/16V")
      (footprint "eagle-import:0603")
      (libsource (lib "eagle-import") (part "discrete_211_C-0603"))
    )
    (comp (ref "C29")
      (value "10uF/4V")
      (footprint "eagle-import:0603")
      (libsource (lib "eagle-import") (part "discrete_211_C-0603"))
    )
    (comp (ref "C30")
      (value "0.1uF")
      (footprint "eagle-import:0603")
      (libsource (lib "eagle-import") (part "discrete_211_C-0603"))
    )
    (comp (ref "C31")
      (value "1uF/16V")
      (footprint "eagle-import:0603")
      (libsource (lib "eagle-import") (part "discrete_211_C-0603"))
    )
    (comp (ref "C32")
      (value "1uF/16V")
      (footprint "eagle-import:0603")
      (libsource (lib "eagle-import") (part "discrete_211_C-0603"))
    )
    (comp (ref "C33")
      (value "0.1uF")
      (footprint "eagle-import:0603")
      (libsource (lib "eagle-import") (part "discrete_211_C-0603"))
    )
    (comp (ref "C34")
      (value "dnp")
      (footprint "eagle-import:0603")
      (libsource (lib "eagle-import") (part "discrete_211_C-0603"))
    )
    (comp (ref "C35")
      (value "0.1uF")
      (footprint "eagle-import:0603")
      (libsource (lib "eagle-import") (part "discrete_211_C-0603"))
    )
    (comp (ref "C36")
      (value "10nF")
      (footprint "eagle-import:0603")
      (libsource (lib "eagle-import") (part "discrete_211_C-0603"))
    )
    (comp (ref "C38")
      (value "10uF/4V")
      (footprint "eagle-import:0603")
      (libsource (lib "eagle-import") (part "discrete_211_C-0603"))
    )
    (comp (ref "C47")
      (value "10nF")
      (footprint "eagle-import:0603")
      (libsource (lib "eagle-import") (part "discrete_211_C-0603"))
    )
    (comp (ref "C59")
      (value "10uF/4V")
      (footprint "eagle-import:0603")
      (libsource (lib "eagle-import") (part "discrete_211_C-0603"))
    )
    (comp (ref "D2")
      (value "DNP")
      (footprint "eagle-import:SOD-123")
      (libsource (lib "eagle-import") (part "STPS0540Z"))
    )
    (comp (ref "D3")
      (value "STPS0540Z")
      (footprint "eagle-import:SOD-123")
      (libsource (lib "eagle-import") (part "STPS0540Z"))
    )
    (comp (ref "D4")
      (value "PMEG3030BEP")
      (footprint "eagle-import:SOD-128")
      (libsource (lib "eagle-import") (part "PMEG3030BEP"))
    )
    (comp (ref "FID1")
      (value "REF")
      (footprint "eagle-import:REF")
      (libsource (lib "eagle-import") (part "REF"))
    )
    (comp (ref "FID2")
      (value "REF")
      (footprint "eagle-import:REF")
      (libsource (lib "eagle-import") (part "REF"))
    )
    (comp (ref "FID3")
      (value "REF")
      (footprint "eagle-import:REF")
      (libsource (lib "eagle-import") (part "REF"))
    )
    (comp (ref "FID4")
      (value "REF")
      (footprint "eagle-import:REF")
      (libsource (lib "eagle-import") (part "REF"))
    )
    (comp (ref "H1")
      (value "STANDOFF_ELECTRICAL")
      (footprint "eagle-import:STANDOFF-ELECTRICAL")
      (libsource (lib "eagle-import") (part "STANDOFF_ELECTRICAL"))
    )
    (comp (ref "H2")
      (value "STANDOFF_ELECTRICAL")
      (footprint "eagle-import:STANDOFF-ELECTRICAL")
      (libsource (lib "eagle-import") (part "STANDOFF_ELECTRICAL"))
    )
    (comp (ref "H3")
      (value "STANDOFF_ELECTRICAL")
      (footprint "eagle-import:STANDOFF-ELECTRICAL")
      (libsource (lib "eagle-import") (part "STANDOFF_ELECTRICAL"))
    )
    (comp (ref "H4")
      (value "STANDOFF_ELECTRICAL")
      (footprint "eagle-import:STANDOFF-ELECTRICAL")
      (libsource (lib "eagle-import") (part "STANDOFF_ELECTRICAL"))
    )
    (comp (ref "H5")
      (value "STANDOFF_ELECTRICAL")
      (footprint "eagle-import:STANDOFF-ELECTRICAL")
      (libsource (lib "eagle-import") (part "STANDOFF_ELECTRICAL"))
    )
    (comp (ref "IC1")
      (value "ISL60002DIH325Z-TK")
      (footprint "eagle-import:SOT-23")
      (libsource (lib "eagle-import") (part "ISL60002DIH325Z-TK"))
    )
    (comp (ref "IC2")
      (value "SN65HVD12D")
      (footprint "eagle-import:SO08")
      (libsource (lib "eagle-import") (part "SN65HVD3082ED"))
    )
    (comp (ref "IC3")
      (value "PIC24FJ256GA110-I/PT")
      (footprint "eagle-import:SQFP-S-12X12-100")
      (libsource (lib "eagle-import") (part "PIC24FJ256GA110-I/PT"))
    )
    (comp (ref "IC4")
      (value "PIC10F200T-I/OT")
      (footprint "eagle-import:SOT23-6")
      (libsource (lib "eagle-import") (part "PIC10F200T-I/OT"))
    )
    (comp (ref "IC5")
      (value "LM75ADP")
      (footprint "eagle-import:TSSOP08-3")
      (libsource (lib "eagle-import") (part "LM75ADP"))
    )
    (comp (ref "IC6")
      (value "24LC32A-I/MS")
      (footprint "eagle-import:MSOP-08")
      (libsource (lib "eagle-import") (part "24-I/MS"))
    )
    (comp (ref "IC8")
      (value "M25P16-VMN6P")
      (footprint "eagle-import:SO-08")
      (libsource (lib "eagle-import") (part "M25P16-VMN6P"))
    )
    (comp (ref "IC9")
      (value "LM3405AXMK/NOPB")
      (footprint "eagle-import:SOT23-6")
      (libsource (lib "eagle-import") (part "LM3405AXMK/NOPB"))
    )
    (comp (ref "J1")
      (value "DF11-10DP-2DSA(01)")
      (footprint "eagle-import:DF11-10DP-2DSA")
      (libsource (lib "eagle-import") (part "DF11-10DP-2DSA(01)"))
    )
    (comp (ref "J2")
      (value "DNP")
      (footprint "eagle-import:MA07-1")
      (libsource (lib "eagle-import") (part "MA07-1"))
    )
    (comp (ref "J3")
      (value "14011213102000")
      (footprint "eagle-import:14011213102000")
      (libsource (lib "eagle-import") (part "14011213102000"))
    )
    (comp (ref "J7")
      (value "SS-6566-NF")
      (footprint "eagle-import:SS-6566-NF")
      (libsource (lib "eagle-import") (part "SS-6566-NF"))
    )
    (comp (ref "J8")
      (value "TSW-108-07-G-D")
      (footprint "eagle-import:MA08-2")
      (libsource (lib "eagle-import") (part "MA08-2"))
    )
    (comp (ref "J9")
      (value "SS-6566-NF")
      (footprint "eagle-import:SS-6566-NF")
      (libsource (lib "eagle-import") (part "SS-6566-NF"))
    )
    (comp (ref "J10")
      (value "CCM03-3504LFT-NR")
      (footprint "eagle-import:CCM03-3504LFT-NR")
      (libsource (lib "eagle-import") (part "CCM03-3504LFT-NR"))
    )
    (comp (ref "J11")
      (value "DNP")
      (footprint "eagle-import:MA05-1")
      (libsource (lib "eagle-import") (part "MA05-1"))
    )
    (comp (ref "J12")
      (value "DNP")
      (footprint "eagle-import:MA05-1")
      (libsource (lib "eagle-import") (part "MA05-1"))
    )
    (comp (ref "J14")
      (value "3-641215-2")
      (footprint "eagle-import:3-641215-2")
      (libsource (lib "eagle-import") (part "3-641215-2"))
    )
    (comp (ref "J30")
      (value "22-11-2072")
      (footprint "eagle-import:HRXL-MAXSONAR-WRC-MB7387")
      (libsource (lib "eagle-import") (part "HRXL-MAXSONAR-WRC-MB7387"))
    )
    (comp (ref "JP1")
      (value "DNP")
      (footprint "eagle-import:1X08-LOCK")
      (libsource (lib "eagle-import") (part "PINHD-1X8LOCK"))
    )
    (comp (ref "L1")
      (value "HI1206T500R-00")
      (footprint "eagle-import:1206")
      (libsource (lib "eagle-import") (part "L-1206"))
    )
    (comp (ref "L2")
      (value "HI1206T500R-00")
      (footprint "eagle-import:1206")
      (libsource (lib "eagle-import") (part "L-1206"))
    )
    (comp (ref "L3")
      (value "NRS8030T150MJGJ")
      (footprint "eagle-import:NRS8030")
      (libsource (lib "eagle-import") (part "NRS8030T150MJGJ"))
    )
    (comp (ref "Q2")
      (value "FDC6330L")
      (footprint "eagle-import:SSOT-6")
      (libsource (lib "eagle-import") (part "FDC6330L"))
    )
    (comp (ref "Q3")
      (value "SR3.3.TCT")
      (footprint "eagle-import:SOT-143")
      (libsource (lib "eagle-import") (part "SR05.TCT"))
    )
    (comp (ref "Q4")
      (value "7B-28.63636MAAJ-T")
      (footprint "eagle-import:7B")
      (libsource (lib "eagle-import") (part "7B-27.120MAAJ-T"))
    )
    (comp (ref "Q5")
      (value "FDC6330L")
      (footprint "eagle-import:SSOT-6")
      (libsource (lib "eagle-import") (part "FDC6324L"))
    )
    (comp (ref "Q7")
      (value "SSM6P49NU,LFPZ")
      (footprint "eagle-import:MICRO_FET")
      (libsource (lib "eagle-import") (part "SSM6P49PZNU,LF"))
    )
    (comp (ref "R1")
      (value "300R")
      (footprint "eagle-import:0603")
      (libsource (lib "eagle-import") (part "discrete_211_R-0603"))
    )
    (comp (ref "R2")
      (value "4x100K")
      (footprint "eagle-import:0603-ARRAY")
      (libsource (lib "eagle-import") (part "EXB-38"))
    )
    (comp (ref "R3")
      (value "1M")
      (footprint "eagle-import:0603")
      (libsource (lib "eagle-import") (part "discrete_211_R-0603"))
    )
    (comp (ref "R4")
      (value "1M")
      (footprint "eagle-import:0603")
      (libsource (lib "eagle-import") (part "discrete_211_R-0603"))
    )
    (comp (ref "R5")
      (value "1M")
      (footprint "eagle-import:0603")
      (libsource (lib "eagle-import") (part "discrete_211_R-0603"))
    )
    (comp (ref "R6")
      (value "1M")
      (footprint "eagle-import:0603")
      (libsource (lib "eagle-import") (part "discrete_211_R-0603"))
    )
    (comp (ref "R7")
      (value "100K")
      (footprint "eagle-import:0603")
      (libsource (lib "eagle-import") (part "R-0603"))
    )
    (comp (ref "R8")
      (value "3.57K")
      (footprint "eagle-import:0603")
      (libsource (lib "eagle-import") (part "discrete_211_R-0603"))
    )
    (comp (ref "R9")
      (value "1M")
      (footprint "eagle-import:0603")
      (libsource (lib "eagle-import") (part "discrete_211_R-0603"))
    )
    (comp (ref "R10")
      (value "1M")
      (footprint "eagle-import:0603")
      (libsource (lib "eagle-import") (part "discrete_211_R-0603"))
    )
    (comp (ref "R11")
      (value "1M")
      (footprint "eagle-import:0603")
      (libsource (lib "eagle-import") (part "discrete_211_R-0603"))
    )
    (comp (ref "R12")
      (value "470K")
      (footprint "eagle-import:0603-0RTOP")
      (libsource (lib "eagle-import") (part "R-0603-0RTOP"))
    )
    (comp (ref "R13")
      (value "0R")
      (footprint "eagle-import:0603-0RTOP")
      (libsource (lib "eagle-import") (part "R-0603-0RTOP"))
    )
    (comp (ref "R14")
      (value "33K")
      (footprint "eagle-import:0603")
      (libsource (lib "eagle-import") (part "discrete_211_R-0603"))
    )
    (comp (ref "R15")
      (value "0R")
      (footprint "eagle-import:0603-0RTOP")
      (libsource (lib "eagle-import") (part "R-0603-0RTOP"))
    )
    (comp (ref "R18")
      (value "649R")
      (footprint "eagle-import:0603")
      (libsource (lib "eagle-import") (part "discrete_211_R-0603"))
    )
    (comp (ref "R19")
      (value "649R")
      (footprint "eagle-import:0603")
      (libsource (lib "eagle-import") (part "discrete_211_R-0603"))
    )
    (comp (ref "R20")
      (value "4x100K")
      (footprint "eagle-import:0603-ARRAY")
      (libsource (lib "eagle-import") (part "EXB-38"))
    )
    (comp (ref "R21")
      (value "4x100K")
      (footprint "eagle-import:0603-ARRAY")
      (libsource (lib "eagle-import") (part "EXB-38"))
    )
    (comp (ref "R23")
      (value "10K")
      (footprint "eagle-import:0603")
      (libsource (lib "eagle-import") (part "R-0603"))
    )
    (comp (ref "R24")
      (value "1M")
      (footprint "eagle-import:0603")
      (libsource (lib "eagle-import") (part "discrete_211_R-0603"))
    )
    (comp (ref "R25")
      (value "10K")
      (footprint "eagle-import:0603")
      (libsource (lib "eagle-import") (part "discrete_211_R-0603"))
    )
    (comp (ref "R26")
      (value "0.22R")
      (footprint "eagle-import:0603")
      (libsource (lib "eagle-import") (part "discrete_211_R-0603"))
    )
    (comp (ref "R27")
      (value "649R")
      (footprint "eagle-import:0603")
      (libsource (lib "eagle-import") (part "discrete_211_R-0603"))
    )
    (comp (ref "R28")
      (value "649R")
      (footprint "eagle-import:0603")
      (libsource (lib "eagle-import") (part "discrete_211_R-0603"))
    )
    (comp (ref "R29")
      (value "4x100K")
      (footprint "eagle-import:0603-ARRAY")
      (libsource (lib "eagle-import") (part "EXB-38"))
    )
    (comp (ref "R30")
      (value "10K")
      (footprint "eagle-import:0603")
      (libsource (lib "eagle-import") (part "discrete_211_R-0603"))
    )
    (comp (ref "R37")
      (value "300R")
      (footprint "eagle-import:0603")
      (libsource (lib "eagle-import") (part "discrete_211_R-0603"))
    )
    (comp (ref "TP1")
      (value "ROUND_SMD1MM")
      (footprint "eagle-import:SMD_ROUND_1MM")
      (libsource (lib "eagle-import") (part "ROUND_SMD1MM"))
    )
    (comp (ref "TP2")
      (value "ROUND_SMD1MM")
      (footprint "eagle-import:SMD_ROUND_1MM")
      (libsource (lib "eagle-import") (part "ROUND_SMD1MM"))
    )
    (comp (ref "TP3")
      (value "ROUND_SMD1MM")
      (footprint "eagle-import:SMD_ROUND_1MM")
      (libsource (lib "eagle-import") (part "ROUND_SMD1MM"))
    )
    (comp (ref "TP4")
      (value "ROUND_SMD1MM")
      (footprint "eagle-import:SMD_ROUND_1MM")
      (libsource (lib "eagle-import") (part "ROUND_SMD1MM"))
    )
    (comp (ref "TP5")
      (value "ROUND_SMD1MM")
      (footprint "eagle-import:SMD_ROUND_1MM")
      (libsource (lib "eagle-import") (part "ROUND_SMD1MM"))
    )
    (comp (ref "TP6")
      (value "ROUND_SMD1MM")
      (footprint "eagle-import:SMD_ROUND_1MM")
      (libsource (lib "eagle-import") (part "ROUND_SMD1MM"))
    )
    (comp (ref "TP8")
      (value "ROUND_SMD1MM")
      (footprint "eagle-import:SMD_ROUND_1MM")
      (libsource (lib "eagle-import") (part "ROUND_SMD1MM"))
    )
    (comp (ref "TP9")
      (value "ROUND_SMD0.7MM")
      (footprint "eagle-import:SMD_ROUND_07MM")
      (libsource (lib "eagle-import") (part "ROUND_SMD0.7MM"))
    )
    (comp (ref "TP10")
      (value "ROUND_SMD1MM")
      (footprint "eagle-import:SMD_ROUND_1MM")
      (libsource (lib "eagle-import") (part "ROUND_SMD1MM"))
    )
    (comp (ref "TP11")
      (value "ROUND_SMD0.7MM")
      (footprint "eagle-import:SMD_ROUND_07MM")
      (libsource (lib "eagle-import") (part "ROUND_SMD0.7MM"))
    )
    (comp (ref "TP12")
      (value "TP_0812")
      (footprint "eagle-import:TP_0.8_1.2")
      (libsource (lib "eagle-import") (part "TP_0812"))
    )
    (comp (ref "U1")
      (value "LTC1955")
      (footprint "eagle-import:LFCSP_5X5_032")
      (libsource (lib "eagle-import") (part "LTC1955"))
    )
    (comp (ref "X1")
      (value "FH12-22(10)SA-1SH")
      (footprint "eagle-import:CON-FPC-1.0MM-10POS")
      (libsource (lib "eagle-import") (part "FH12-10S-0.5S1.00MM"))
    )
    (comp (ref "C43")
      (value "470uF/35-50V")
      (footprint "eagle-import:E5-13")
      (libsource (lib "eagle-import") (part "CPOL-USE5-13"))
    )
    (comp (ref "C44")
      (value "220uF, 16V, AL")
      (footprint "eagle-import:153CLV-0605")
      (libsource (lib "eagle-import") (part "CPOL-US153CLV-0605"))
    )
    (comp (ref "C122")
      (value "22uF,25V,1206")
      (footprint "eagle-import:C1206")
      (fields (field (name "MANUFACTURER") "Samsung"))
      (libsource (lib "eagle-import") (part "C-US-NP1206"))
    )
    (comp (ref "C123")
      (value "22uF,25V,1206")
      (footprint "eagle-import:C1206")
      (fields (field (name "MANUFACTURER") "Samsung"))
      (libsource (lib "eagle-import") (part "C-US-NP1206"))
    )
    (comp (ref "C124")
      (value "100pF")
      (footprint "eagle-import:0603")
      (fields (field (name "MANUFACTURER") "Samsung"))
      (libsource (lib "eagle-import") (part "C-0603"))
    )
    (comp (ref "C125")
      (value "0.1uF")
      (footprint "eagle-import:0603")
      (fields (field (name "MANUFACTURER") "Murata"))
      (libsource (lib "eagle-import") (part "C-0603"))
    )
    (comp (ref "C126")
      (value "0.1uF")
      (footprint "eagle-import:0603")
      (fields (field (name "MANUFACTURER") "Murata"))
      (libsource (lib "eagle-import") (part "C-0603"))
    )
    (comp (ref "C127")
      (value "4.7uF/6.3V")
      (footprint "eagle-import:0603")
      (fields (field (name "MANUFACTURER") "Samsung"))
      (libsource (lib "eagle-import") (part "C-0603"))
    )
    (comp (ref "C128")
      (value "22uF,25V,1206")
      (footprint "eagle-import:C1206")
      (fields (field (name "MANUFACTURER") "Samsung"))
      (libsource (lib "eagle-import") (part "C-US-NP1206"))
    )
    (comp (ref "C129")
      (value "22uF,25V,1206")
      (footprint "eagle-import:C1206")
      (fields (field (name "MANUFACTURER") "Samsung"))
      (libsource (lib "eagle-import") (part "C-US-NP1206"))
    )
    (comp (ref "C130")
      (value "22uF,25V,1206")
      (footprint "eagle-import:C1206")
      (fields (field (name "MANUFACTURER") "Samsung"))
      (libsource (lib "eagle-import") (part "C-US-NP1206"))
    )
    (comp (ref "C131")
      (value "130pF,C0G")
      (footprint "eagle-import:C0603")
      (fields (field (name "MANUFACTURER") "Samsung"))
      (libsource (lib "eagle-import") (part "C-US-NP0603"))
    )
    (comp (ref "C132")
      (value "0.1uF")
      (footprint "eagle-import:0603")
      (fields (field (name "MANUFACTURER") "Murata"))
      (libsource (lib "eagle-import") (part "C-0603"))
    )
    (comp (ref "C133")
      (value "15nF")
      (footprint "eagle-import:C0603")
      (fields (field (name "MANUFACTURER") "Samsung"))
      (libsource (lib "eagle-import") (part "C-US-NP0603"))
    )
    (comp (ref "C134")
      (value "10nF")
      (footprint "eagle-import:0603")
      (libsource (lib "eagle-import") (part "discrete_211_C-0603"))
    )
    (comp (ref "C135")
      (value "10uF/35V")
      (footprint "eagle-import:1206")
      (libsource (lib "eagle-import") (part "C-1206"))
    )
    (comp (ref "C136")
      (value "22uF,25V,1206")
      (footprint "eagle-import:C1206")
      (fields (field (name "MANUFACTURER") "Samsung"))
      (libsource (lib "eagle-import") (part "C-US-NP1206"))
    )
    (comp (ref "C137")
      (value "22uF,25V,1206")
      (footprint "eagle-import:C1206")
      (fields (field (name "MANUFACTURER") "Samsung"))
      (libsource (lib "eagle-import") (part "C-US-NP1206"))
    )
    (comp (ref "C138")
      (value "100pF")
      (footprint "eagle-import:0603")
      (fields (field (name "MANUFACTURER") "Samsung"))
      (libsource (lib "eagle-import") (part "C-0603"))
    )
    (comp (ref "C139")
      (value "0.1uF")
      (footprint "eagle-import:0603")
      (fields (field (name "MANUFACTURER") "Murata"))
      (libsource (lib "eagle-import") (part "C-0603"))
    )
    (comp (ref "C140")
      (value "0.1uF")
      (footprint "eagle-import:0603")
      (fields (field (name "MANUFACTURER") "Murata"))
      (libsource (lib "eagle-import") (part "C-0603"))
    )
    (comp (ref "C141")
      (value "4.7uF/6.3V")
      (footprint "eagle-import:0603")
      (fields (field (name "MANUFACTURER") "Samsung"))
      (libsource (lib "eagle-import") (part "C-0603"))
    )
    (comp (ref "C142")
      (value "10uF/35V")
      (footprint "eagle-import:1206")
      (libsource (lib "eagle-import") (part "C-1206"))
    )
    (comp (ref "C143")
      (value "10uF,50V,1210")
      (footprint "eagle-import:C1210")
      (fields (field (name "MANUFACTURER") "Samsung"))
      (libsource (lib "eagle-import") (part "C-US-NP1210"))
    )
    (comp (ref "C144")
      (value "10uF,50V,1210")
      (footprint "eagle-import:C1210")
      (fields (field (name "MANUFACTURER") "Samsung"))
      (libsource (lib "eagle-import") (part "C-US-NP1210"))
    )
    (comp (ref "C145")
      (value "10uF,50V,1210")
      (footprint "eagle-import:C1210")
      (fields (field (name "MANUFACTURER") "Samsung"))
      (libsource (lib "eagle-import") (part "C-US-NP1210"))
    )
    (comp (ref "C146")
      (value "100pF")
      (footprint "eagle-import:C0603")
      (fields (field (name "MANUFACTURER") "Samsung"))
      (libsource (lib "eagle-import") (part "C-US-NP0603"))
    )
    (comp (ref "C147")
      (value "0.1uF")
      (footprint "eagle-import:0603")
      (fields (field (name "MANUFACTURER") "Murata"))
      (libsource (lib "eagle-import") (part "C-0603"))
    )
    (comp (ref "C148")
      (value "10nF")
      (footprint "eagle-import:0603")
      (fields (field (name "MANUFACTURER") "Samsung"))
      (libsource (lib "eagle-import") (part "C-0603"))
    )
    (comp (ref "C149")
      (value "22u/16V")
      (footprint "eagle-import:1210")
      (libsource (lib "eagle-import") (part "C-1210"))
    )
    (comp (ref "C150")
      (value "0.1uF")
      (footprint "eagle-import:0603")
      (libsource (lib "eagle-import") (part "discrete_211_C-0603"))
    )
    (comp (ref "C152")
      (value "22u/16V")
      (footprint "eagle-import:1210")
      (libsource (lib "eagle-import") (part "C-1210"))
    )
    (comp (ref "C153")
      (value "22u/16V")
      (footprint "eagle-import:1210")
      (libsource (lib "eagle-import") (part "C-1210"))
    )
    (comp (ref "C154")
      (value "0.1uF")
      (footprint "eagle-import:0603")
      (libsource (lib "eagle-import") (part "discrete_211_C-0603"))
    )
    (comp (ref "C155")
      (value "1nF")
      (footprint "eagle-import:0603")
      (libsource (lib "eagle-import") (part "discrete_211_C-0603"))
    )
    (comp (ref "C156")
      (value "TCJB157M006R0045")
      (footprint "eagle-import:3528-POL")
      (libsource (lib "eagle-import") (part "C-POL-3528"))
    )
    (comp (ref "C157")
      (value "47uF/6.3V")
      (footprint "eagle-import:1210")
      (libsource (lib "eagle-import") (part "C-1210"))
    )
    (comp (ref "C158")
      (value "47uF/6.3V")
      (footprint "eagle-import:1210")
      (libsource (lib "eagle-import") (part "C-1210"))
    )
    (comp (ref "C160")
      (value "15pF")
      (footprint "eagle-import:0603")
      (libsource (lib "eagle-import") (part "discrete_211_C-0603"))
    )
    (comp (ref "C163")
      (value "0.1uF")
      (footprint "eagle-import:0603")
      (libsource (lib "eagle-import") (part "discrete_211_C-0603"))
    )
    (comp (ref "C164")
      (value "330pF")
      (footprint "eagle-import:0603")
      (libsource (lib "eagle-import") (part "discrete_211_C-0603"))
    )
    (comp (ref "C187")
      (value "2mF/16V")
      (footprint "eagle-import:E7,5-18")
      (libsource (lib "eagle-import") (part "CPOL-USE7.5-18"))
    )
    (comp (ref "D20")
      (value "PMEG3030BEP")
      (footprint "eagle-import:SOD-128")
      (libsource (lib "eagle-import") (part "PMEG3030BEP"))
    )
    (comp (ref "D21")
      (value "SMAJ26A")
      (footprint "eagle-import:SMA")
      (libsource (lib "eagle-import") (part "SMAJ5.0A"))
    )
    (comp (ref "D22")
      (value "PMEG3030BEP")
      (footprint "eagle-import:SOD-128")
      (libsource (lib "eagle-import") (part "PMEG3030BEP"))
    )
    (comp (ref "D23")
      (value "LED-GR")
      (footprint "eagle-import:0805-POL")
      (libsource (lib "eagle-import") (part "LED-0805"))
    )
    (comp (ref "D24")
      (value "LED-GR")
      (footprint "eagle-import:0805-POL")
      (libsource (lib "eagle-import") (part "LED-0805"))
    )
    (comp (ref "D25")
      (value "SS14")
      (footprint "eagle-import:SMA")
      (libsource (lib "eagle-import") (part "SS14"))
    )
    (comp (ref "D26")
      (value "SS14")
      (footprint "eagle-import:SMA")
      (libsource (lib "eagle-import") (part "SS14"))
    )
    (comp (ref "D27")
      (value "SMLVT3V3")
      (footprint "eagle-import:SMA")
      (libsource (lib "eagle-import") (part "SMLVT3V3"))
    )
    (comp (ref "D28")
      (value "SMAJ5.0A")
      (footprint "eagle-import:SMA")
      (libsource (lib "eagle-import") (part "SMAJ5.0A"))
    )
    (comp (ref "D30")
      (value "PMEG3030BEP")
      (footprint "eagle-import:SOD-128")
      (libsource (lib "eagle-import") (part "PMEG3030BEP"))
    )
    (comp (ref "D31")
      (value "BAT54BRW-7F")
      (footprint "eagle-import:SOT-363")
      (libsource (lib "eagle-import") (part "BAT54BRW-7F"))
    )
    (comp (ref "D32")
      (value "P6SMB16A")
      (footprint "eagle-import:SMB")
      (libsource (lib "eagle-import") (part "P6SMB16A"))
    )
    (comp (ref "F3")
      (value "2920L250DR")
      (footprint "eagle-import:1812")
      (libsource (lib "eagle-import") (part "1812L014DR"))
    )
    (comp (ref "IC19")
      (value "MCP602-I/ST")
      (footprint "eagle-import:TSSOP8")
      (libsource (lib "eagle-import") (part "MCP6022-I/ST"))
    )
    (comp (ref "IC21")
      (value "LTC1771EMS8")
      (footprint "eagle-import:MSOP-08")
      (libsource (lib "eagle-import") (part "LTC1771EMS8"))
    )
    (comp (ref "J45")
      (value "3-641215-4")
      (footprint "eagle-import:3-641215-4")
      (libsource (lib "eagle-import") (part "3-641215-4"))
    )
    (comp (ref "J50")
      (value "0039301040")
      (footprint "eagle-import:0039301040")
      (libsource (lib "eagle-import") (part "0039301040"))
    )
    (comp (ref "L11")
      (value "SER2013-472MLD")
      (footprint "eagle-import:L_SER20XX")
      (fields (field (name "MANUFACTURER") "Coilcraft"))
      (libsource (lib "eagle-import") (part "LSER20XX"))
    )
    (comp (ref "L12")
      (value "SRR1280-150M")
      (footprint "eagle-import:L_SRR1280")
      (fields (field (name "MANUFACTURER") "Bourns") (field (name "MFR_PN") "SRR1280-1x0M"))
      (libsource (lib "eagle-import") (part "LSRR1280"))
    )
    (comp (ref "L14")
      (value "CR75NP-220KC")
      (footprint "eagle-import:CR75")
      (libsource (lib "eagle-import") (part "CR75-330KC"))
    )
    (comp (ref "Q14")
      (value "MAX9938HEUK")
      (footprint "eagle-import:SOT23-5")
      (libsource (lib "eagle-import") (part "TSM9938HEUK+T"))
    )
    (comp (ref "Q15")
      (value "SI4564DY")
      (footprint "eagle-import:SO-08")
      (libsource (lib "eagle-import") (part "SI4564DY"))
    )
    (comp (ref "Q16")
      (value "CSD87331Q3D")
      (footprint "eagle-import:SON8_3.3X3.3_TI")
      (fields (field (name "MANUFACTURER") "TI") (field (name "MFR_PN") "CSD87331Q3D"))
      (libsource (lib "eagle-import") (part "TRANS_DUAL_NFET_HALF-BRQ3D"))
    )
    (comp (ref "Q18")
      (value "SI4564DY")
      (footprint "eagle-import:SO-08")
      (libsource (lib "eagle-import") (part "SI4564DY"))
    )
    (comp (ref "Q19")
      (value "CSD87331Q3D")
      (footprint "eagle-import:SON8_3.3X3.3_TI")
      (fields (field (name "MANUFACTURER") "TI") (field (name "MFR_PN") "CSD87331Q3D"))
      (libsource (lib "eagle-import") (part "TRANS_DUAL_NFET_HALF-BRQ3D"))
    )
    (comp (ref "Q20")
      (value "IPD30N06S2L-23")
      (footprint "eagle-import:TO252")
      (libsource (lib "eagle-import") (part "IPD30N06S2L-23"))
    )
    (comp (ref "Q21")
      (value "IPD30N06S2L-23")
      (footprint "eagle-import:TO252")
      (libsource (lib "eagle-import") (part "IPD30N06S2L-23"))
    )
    (comp (ref "Q23")
      (value "FDN352AP")
      (footprint "eagle-import:SOT-23")
      (libsource (lib "eagle-import") (part "FDN352AP"))
    )
    (comp (ref "R40")
      (value "0.025R")
      (footprint "eagle-import:0805")
      (libsource (lib "eagle-import") (part "R-0805"))
    )
    (comp (ref "R41")
      (value "0.025R")
      (footprint "eagle-import:0805")
      (libsource (lib "eagle-import") (part "R-0805"))
    )
    (comp (ref "R42")
      (value "0.025R")
      (footprint "eagle-import:0805")
      (libsource (lib "eagle-import") (part "R-0805"))
    )
    (comp (ref "R43")
      (value "0.025R")
      (footprint "eagle-import:0805")
      (libsource (lib "eagle-import") (part "R-0805"))
    )
    (comp (ref "R44")
      (value "0.025R")
      (footprint "eagle-import:0805")
      (libsource (lib "eagle-import") (part "R-0805"))
    )
    (comp (ref "R45")
      (value "470R")
      (footprint "eagle-import:0603")
      (libsource (lib "eagle-import") (part "discrete_211_R-0603"))
    )
    (comp (ref "R46")
      (value "470R")
      (footprint "eagle-import:0603")
      (libsource (lib "eagle-import") (part "discrete_211_R-0603"))
    )
    (comp (ref "R154")
      (value "0.025R")
      (footprint "eagle-import:0805")
      (libsource (lib "eagle-import") (part "R-0805"))
    )
    (comp (ref "R156")
      (value "1M")
      (footprint "eagle-import:0603")
      (fields (field (name "MANUFACTURER") "Panasonic"))
      (libsource (lib "eagle-import") (part "R-0603"))
    )
    (comp (ref "R157")
      (value "10")
      (footprint "eagle-import:R0603")
      (fields (field (name "MANUFACTURER") "Rohm"))
      (libsource (lib "eagle-import") (part "R-US_R0603"))
    )
    (comp (ref "R158")
      (value "10")
      (footprint "eagle-import:R0603")
      (fields (field (name "MANUFACTURER") "Rohm"))
      (libsource (lib "eagle-import") (part "R-US_R0603"))
    )
    (comp (ref "R159")
      (value "1M")
      (footprint "eagle-import:0603")
      (fields (field (name "MANUFACTURER") "Panasonic"))
      (libsource (lib "eagle-import") (part "R-0603"))
    )
    (comp (ref "R160")
      (value "178k,1%")
      (footprint "eagle-import:R0603")
      (fields (field (name "MANUFACTURER") "Panasonic"))
      (libsource (lib "eagle-import") (part "R-US_R0603"))
    )
    (comp (ref "R161")
      (value "0")
      (footprint "eagle-import:R0603")
      (fields (field (name "MANUFACTURER") "Panasonic"))
      (libsource (lib "eagle-import") (part "R-US_R0603"))
    )
    (comp (ref "R162")
      (value "10K")
      (footprint "eagle-import:0603")
      (fields (field (name "MANUFACTURER") "Panasonic"))
      (libsource (lib "eagle-import") (part "R-0603"))
    )
    (comp (ref "R163")
      (value "0")
      (footprint "eagle-import:R0603")
      (fields (field (name "MANUFACTURER") "Panasonic"))
      (libsource (lib "eagle-import") (part "R-US_R0603"))
    )
    (comp (ref "R164")
      (value "5.90K,1%")
      (footprint "eagle-import:0603")
      (fields (field (name "MANUFACTURER") "Panasonic"))
      (libsource (lib "eagle-import") (part "R-0603"))
    )
    (comp (ref "R165")
      (value "93.1K,1%")
      (footprint "eagle-import:0603")
      (fields (field (name "MANUFACTURER") "Panasonic"))
      (libsource (lib "eagle-import") (part "R-0603"))
    )
    (comp (ref "R166")
      (value "20.0k,1%")
      (footprint "eagle-import:R0603")
      (fields (field (name "MANUFACTURER") "Panasonic"))
      (libsource (lib "eagle-import") (part "R-US_R0603"))
    )
    (comp (ref "R167")
      (value "100K")
      (footprint "eagle-import:0603")
      (fields (field (name "MANUFACTURER") "Panasonic"))
      (libsource (lib "eagle-import") (part "R-0603"))
    )
    (comp (ref "R170")
      (value "1M")
      (footprint "eagle-import:0603")
      (libsource (lib "eagle-import") (part "discrete_211_R-0603"))
    )
    (comp (ref "R171")
      (value "10")
      (footprint "eagle-import:R0603")
      (fields (field (name "MANUFACTURER") "Rohm"))
      (libsource (lib "eagle-import") (part "R-US_R0603"))
    )
    (comp (ref "R172")
      (value "10")
      (footprint "eagle-import:R0603")
      (fields (field (name "MANUFACTURER") "Rohm"))
      (libsource (lib "eagle-import") (part "R-US_R0603"))
    )
    (comp (ref "R173")
      (value "1M")
      (footprint "eagle-import:0603")
      (libsource (lib "eagle-import") (part "discrete_211_R-0603"))
    )
    (comp (ref "R174")
      (value "1M")
      (footprint "eagle-import:0603")
      (libsource (lib "eagle-import") (part "discrete_211_R-0603"))
    )
    (comp (ref "R175")
      (value "3.3K")
      (footprint "eagle-import:0805")
      (libsource (lib "eagle-import") (part "R-0805"))
    )
    (comp (ref "R176")
      (value "3.3K")
      (footprint "eagle-import:0805")
      (libsource (lib "eagle-import") (part "R-0805"))
    )
    (comp (ref "R177")
      (value "178k,1%")
      (footprint "eagle-import:R0603")
      (fields (field (name "MANUFACTURER") "Panasonic"))
      (libsource (lib "eagle-import") (part "R-US_R0603"))
    )
    (comp (ref "R178")
      (value "0")
      (footprint "eagle-import:R0603")
      (fields (field (name "MANUFACTURER") "Panasonic"))
      (libsource (lib "eagle-import") (part "R-US_R0603"))
    )
    (comp (ref "R179")
      (value "10K")
      (footprint "eagle-import:0603")
      (fields (field (name "MANUFACTURER") "Panasonic"))
      (libsource (lib "eagle-import") (part "R-0603"))
    )
    (comp (ref "R180")
      (value "0")
      (footprint "eagle-import:R0603")
      (fields (field (name "MANUFACTURER") "Panasonic"))
      (libsource (lib "eagle-import") (part "R-US_R0603"))
    )
    (comp (ref "R181")
      (value "5.90K,1%")
      (footprint "eagle-import:0603")
      (fields (field (name "MANUFACTURER") "Panasonic"))
      (libsource (lib "eagle-import") (part "R-0603"))
    )
    (comp (ref "R182")
      (value "93.1K,1%")
      (footprint "eagle-import:0603")
      (fields (field (name "MANUFACTURER") "Panasonic"))
      (libsource (lib "eagle-import") (part "R-0603"))
    )
    (comp (ref "R183")
      (value "1M")
      (footprint "eagle-import:0603")
      (libsource (lib "eagle-import") (part "discrete_211_R-0603"))
    )
    (comp (ref "R184")
      (value "1M")
      (footprint "eagle-import:0603")
      (libsource (lib "eagle-import") (part "discrete_211_R-0603"))
    )
    (comp (ref "R185")
      (value "20.0k,1%")
      (footprint "eagle-import:R0603")
      (fields (field (name "MANUFACTURER") "Panasonic"))
      (libsource (lib "eagle-import") (part "R-US_R0603"))
    )
    (comp (ref "R186")
      (value "100K")
      (footprint "eagle-import:0603")
      (fields (field (name "MANUFACTURER") "Panasonic"))
      (libsource (lib "eagle-import") (part "R-0603"))
    )
    (comp (ref "R187")
      (value "47K")
      (footprint "eagle-import:0603")
      (libsource (lib "eagle-import") (part "discrete_211_R-0603"))
    )
    (comp (ref "R189")
      (value "0.12R")
      (footprint "eagle-import:0805")
      (libsource (lib "eagle-import") (part "R-0805"))
    )
    (comp (ref "R190")
      (value "47K")
      (footprint "eagle-import:0603")
      (libsource (lib "eagle-import") (part "discrete_211_R-0603"))
    )
    (comp (ref "R193")
      (value "10K")
      (footprint "eagle-import:0603")
      (libsource (lib "eagle-import") (part "discrete_211_R-0603"))
    )
    (comp (ref "R194")
      (value "3.09M")
      (footprint "eagle-import:0603")
      (libsource (lib "eagle-import") (part "discrete_211_R-0603"))
    )
    (comp (ref "R197")
      (value "1M")
      (footprint "eagle-import:0603")
      (libsource (lib "eagle-import") (part "discrete_211_R-0603"))
    )
    (comp (ref "TP61")
      (value "TPB1,27")
      (footprint "eagle-import:B1,27")
      (libsource (lib "eagle-import") (part "TPB1,27"))
    )
    (comp (ref "TP62")
      (value "TPB1,27")
      (footprint "eagle-import:B1,27")
      (libsource (lib "eagle-import") (part "TPB1,27"))
    )
    (comp (ref "TP63")
      (value "TPB1,27")
      (footprint "eagle-import:B1,27")
      (libsource (lib "eagle-import") (part "TPB1,27"))
    )
    (comp (ref "TP64")
      (value "TPB1,27")
      (footprint "eagle-import:B1,27")
      (libsource (lib "eagle-import") (part "TPB1,27"))
    )
    (comp (ref "TP65")
      (value "TPB1,27")
      (footprint "eagle-import:B1,27")
      (libsource (lib "eagle-import") (part "TPB1,27"))
    )
    (comp (ref "TP66")
      (value "TPB1,27")
      (footprint "eagle-import:B1,27")
      (libsource (lib "eagle-import") (part "TPB1,27"))
    )
    (comp (ref "TP67")
      (value "TPB1,27")
      (footprint "eagle-import:B1,27")
      (libsource (lib "eagle-import") (part "TPB1,27"))
    )
    (comp (ref "U2")
      (value "LE33CD")
      (footprint "eagle-import:LE33")
      (libsource (lib "eagle-import") (part "LE33"))
    )
    (comp (ref "U6")
      (value "TPS43061")
      (footprint "eagle-import:QFN16_3X3_EP")
      (fields (field (name "MANUFACTURER") "TI"))
      (libsource (lib "eagle-import") (part "IC_TI_TPS43061RTE"))
    )
    (comp (ref "U7")
      (value "TPS43061")
      (footprint "eagle-import:QFN16_3X3_EP")
      (fields (field (name "MANUFACTURER") "TI"))
      (libsource (lib "eagle-import") (part "IC_TI_TPS43061RTE"))
    )
    (comp (ref "C37")
      (value "0.1uF")
      (footprint "eagle-import:0603")
      (libsource (lib "eagle-import") (part "discrete_211_C-0603"))
    )
    (comp (ref "C39")
      (value "10uF/4V")
      (footprint "eagle-import:0603")
      (libsource (lib "eagle-import") (part "discrete_211_C-0603"))
    )
    (comp (ref "C40")
      (value "0.1uF")
      (footprint "eagle-import:0603")
      (libsource (lib "eagle-import") (part "discrete_211_C-0603"))
    )
    (comp (ref "C41")
      (value "10uF/4V")
      (footprint "eagle-import:0603")
      (libsource (lib "eagle-import") (part "discrete_211_C-0603"))
    )
    (comp (ref "C42")
      (value "0.1uF")
      (footprint "eagle-import:0603")
      (libsource (lib "eagle-import") (part "discrete_211_C-0603"))
    )
    (comp (ref "C48")
      (value "10uF/4V")
      (footprint "eagle-import:0603")
      (libsource (lib "eagle-import") (part "discrete_211_C-0603"))
    )
    (comp (ref "J15")
      (value "1990834")
      (footprint "eagle-import:1990834")
      (libsource (lib "eagle-import") (part "1990834"))
    )
    (comp (ref "J16")
      (value "1990737")
      (footprint "eagle-import:1990737")
      (libsource (lib "eagle-import") (part "1990737"))
    )
    (comp (ref "J17")
      (value "14011213102000")
      (footprint "eagle-import:14011213102000")
      (libsource (lib "eagle-import") (part "14011213102000"))
    )
    (comp (ref "J18")
      (value "14011213102000")
      (footprint "eagle-import:14011213102000")
      (libsource (lib "eagle-import") (part "14011213102000"))
    )
    (comp (ref "J19")
      (value "14011213102000")
      (footprint "eagle-import:14011213102000")
      (libsource (lib "eagle-import") (part "14011213102000"))
    )
    (comp (ref "R31")
      (value "10K")
      (footprint "eagle-import:0603")
      (libsource (lib "eagle-import") (part "discrete_211_R-0603"))
    )
    (comp (ref "R32")
      (value "10K")
      (footprint "eagle-import:0603")
      (libsource (lib "eagle-import") (part "discrete_211_R-0603"))
    )
    (comp (ref "R33")
      (value "10K")
      (footprint "eagle-import:0603")
      (libsource (lib "eagle-import") (part "discrete_211_R-0603"))
    )
    (comp (ref "R34")
      (value "1K")
      (footprint "eagle-import:0603")
      (libsource (lib "eagle-import") (part "discrete_211_R-0603"))
    )
    (comp (ref "R35")
      (value "10K")
      (footprint "eagle-import:0603")
      (libsource (lib "eagle-import") (part "discrete_211_R-0603"))
    )
    (comp (ref "R36")
      (value "1K")
      (footprint "eagle-import:0603")
      (libsource (lib "eagle-import") (part "discrete_211_R-0603"))
    )
    (comp (ref "R38")
      (value "470R")
      (footprint "eagle-import:0603")
      (libsource (lib "eagle-import") (part "discrete_211_R-0603"))
    )
    (comp (ref "R39")
      (value "470R")
      (footprint "eagle-import:0603")
      (libsource (lib "eagle-import") (part "discrete_211_R-0603"))
    )
    (comp (ref "U3")
      (value "ADS1015IDGS")
      (footprint "eagle-import:MSOP10")
      (libsource (lib "eagle-import") (part "ADS1015"))
    )
    (comp (ref "C165")
      (value "220uF,16V,AL")
      (footprint "eagle-import:CAP_6.3MM_DIA_SMT")
      (fields (field (name "MANUFACTURER") "Kemet") (field (name "MFR_PN") "EEV227M016A9HAA"))
      (libsource (lib "eagle-import") (part "CAP_ELEC_6.3MM_SMD"))
    )
    (comp (ref "C166")
      (value "220uF,16V,AL")
      (footprint "eagle-import:CAP_6.3MM_DIA_SMT")
      (fields (field (name "MANUFACTURER") "Kemet") (field (name "MFR_PN") "EEV227M016A9HAA"))
      (libsource (lib "eagle-import") (part "CAP_ELEC_6.3MM_SMD"))
    )
    (comp (ref "C167")
      (value "0.1uF")
      (footprint "eagle-import:0603")
      (libsource (lib "eagle-import") (part "C-0603"))
    )
    (comp (ref "C168")
      (value "0.1uF")
      (footprint "eagle-import:0603")
      (libsource (lib "eagle-import") (part "C-0603"))
    )
    (comp (ref "C169")
      (value "1.0nF,50V")
      (footprint "eagle-import:C0603")
      (fields (field (name "MANUFACTURER") "Samsung"))
      (libsource (lib "eagle-import") (part "C-US-NP0603"))
    )
    (comp (ref "C170")
      (value "1.0nF,50V")
      (footprint "eagle-import:C0603")
      (fields (field (name "MANUFACTURER") "Samsung"))
      (libsource (lib "eagle-import") (part "C-US-NP0603"))
    )
    (comp (ref "C171")
      (value "10uF,50V,1210")
      (footprint "eagle-import:C1210")
      (fields (field (name "MANUFACTURER") "Samsung"))
      (libsource (lib "eagle-import") (part "C-US-NP1210"))
    )
    (comp (ref "C172")
      (value "1uF,25V")
      (footprint "eagle-import:0603")
      (libsource (lib "eagle-import") (part "discrete_211_C-0603"))
    )
    (comp (ref "C173")
      (value "0.47uF")
      (footprint "eagle-import:0603")
      (fields (field (name "MANUFACTURER") "Taiyo Yuden"))
      (libsource (lib "eagle-import") (part "C-0603"))
    )
    (comp (ref "C174")
      (value "0.47uF")
      (footprint "eagle-import:0603")
      (fields (field (name "MANUFACTURER") "Samsung"))
      (libsource (lib "eagle-import") (part "C-0603"))
    )
    (comp (ref "C175")
      (value "0.47uF")
      (footprint "eagle-import:0603")
      (fields (field (name "MANUFACTURER") "Samsung"))
      (libsource (lib "eagle-import") (part "C-0603"))
    )
    (comp (ref "C176")
      (value "1.0nF,50V")
      (footprint "eagle-import:C0603")
      (fields (field (name "MANUFACTURER") "Samsung"))
      (libsource (lib "eagle-import") (part "C-US-NP0603"))
    )
    (comp (ref "C177")
      (value "0.47uF")
      (footprint "eagle-import:0603")
      (fields (field (name "MANUFACTURER") "Samsung"))
      (libsource (lib "eagle-import") (part "C-0603"))
    )
    (comp (ref "C178")
      (value "0.47uF")
      (footprint "eagle-import:0603")
      (fields (field (name "MANUFACTURER") "Taiyo Yuden"))
      (libsource (lib "eagle-import") (part "C-0603"))
    )
    (comp (ref "C179")
      (value "1.0nF,50V")
      (footprint "eagle-import:C0603")
      (fields (field (name "MANUFACTURER") "Samsung"))
      (libsource (lib "eagle-import") (part "C-US-NP0603"))
    )
    (comp (ref "C180")
      (value "22uF,25V,1206")
      (footprint "eagle-import:C1206")
      (fields (field (name "MANUFACTURER") "Samsung"))
      (libsource (lib "eagle-import") (part "C-US-NP1206"))
    )
    (comp (ref "C181")
      (value "22uF,25V,1206")
      (footprint "eagle-import:C1206")
      (fields (field (name "MANUFACTURER") "Samsung"))
      (libsource (lib "eagle-import") (part "C-US-NP1206"))
    )
    (comp (ref "C182")
      (value "1uF,25V")
      (footprint "eagle-import:0603")
      (libsource (lib "eagle-import") (part "C-0603"))
    )
    (comp (ref "C183")
      (value "3.3uF,16V")
      (footprint "eagle-import:0603")
      (libsource (lib "eagle-import") (part "C-0603"))
    )
    (comp (ref "C184")
      (value "3.3uF,16V")
      (footprint "eagle-import:0603")
      (libsource (lib "eagle-import") (part "C-0603"))
    )
    (comp (ref "C185")
      (value "3.3uF,16V")
      (footprint "eagle-import:0603")
      (libsource (lib "eagle-import") (part "C-0603"))
    )
    (comp (ref "C186")
      (value "220pF")
      (footprint "eagle-import:C0603")
      (libsource (lib "eagle-import") (part "C-US-NP0603"))
    )
    (comp (ref "J4")
      (value "3-641215-2")
      (footprint "eagle-import:3-641215-2")
      (libsource (lib "eagle-import") (part "3-641215-2"))
    )
    (comp (ref "J47")
      (value "DF11-10DP-2DSA(01)")
      (footprint "eagle-import:DF11-10DP-2DSA")
      (libsource (lib "eagle-import") (part "DF11-10DP-2DSA(01)"))
    )
    (comp (ref "J48")
      (value "3-641215-2")
      (footprint "eagle-import:3-641215-2")
      (libsource (lib "eagle-import") (part "3-641215-2"))
    )
    (comp (ref "J49")
      (value "3-641215-2")
      (footprint "eagle-import:3-641215-2")
      (libsource (lib "eagle-import") (part "3-641215-2"))
    )
    (comp (ref "L15")
      (value "HI1812V101R-10")
      (footprint "eagle-import:L1812")
      (fields (field (name "MANUFACTURER") "Laird") (field (name "MFR_PN") "HI1812V101R-10"))
      (libsource (lib "eagle-import") (part "L1812"))
    )
    (comp (ref "L16")
      (value "HI1812V101R-10")
      (footprint "eagle-import:L1812")
      (fields (field (name "MANUFACTURER") "Laird") (field (name "MFR_PN") "HI1812V101R-10"))
      (libsource (lib "eagle-import") (part "L1812"))
    )
    (comp (ref "L17")
      (value "HI1206T500R-00")
      (footprint "eagle-import:1206")
      (libsource (lib "eagle-import") (part "L-1206"))
    )
    (comp (ref "Q24")
      (value "BSS138")
      (footprint "eagle-import:SOT23")
      (libsource (lib "eagle-import") (part "BSS138"))
    )
    (comp (ref "R16")
      (value "0")
      (footprint "eagle-import:R0603")
      (fields (field (name "MANUFACTURER") "Panasonic"))
      (libsource (lib "eagle-import") (part "R-US_R0603"))
    )
    (comp (ref "R198")
      (value "10")
      (footprint "eagle-import:R0603")
      (fields (field (name "MANUFACTURER") "Rohm"))
      (libsource (lib "eagle-import") (part "R-US_R0603"))
    )
    (comp (ref "R200")
      (value "1M")
      (footprint "eagle-import:0603")
      (libsource (lib "eagle-import") (part "R-0603"))
    )
    (comp (ref "R201")
      (value "1M")
      (footprint "eagle-import:0603")
      (libsource (lib "eagle-import") (part "R-0603"))
    )
    (comp (ref "R202")
      (value "DNP")
      (footprint "eagle-import:R0603")
      (libsource (lib "eagle-import") (part "R-US_R0603"))
    )
    (comp (ref "R203")
      (value "DNP")
      (footprint "eagle-import:R0603")
      (libsource (lib "eagle-import") (part "R-US_R0603"))
    )
    (comp (ref "R204")
      (value "1K")
      (footprint "eagle-import:0603")
      (libsource (lib "eagle-import") (part "R-0603"))
    )
    (comp (ref "R205")
      (value "100K")
      (footprint "eagle-import:0603")
      (libsource (lib "eagle-import") (part "R-0603"))
    )
    (comp (ref "R206")
      (value "33R")
      (footprint "eagle-import:0603")
      (libsource (lib "eagle-import") (part "R-0603"))
    )
    (comp (ref "R207")
      (value "3.3K")
      (footprint "eagle-import:0603")
      (libsource (lib "eagle-import") (part "R-0603"))
    )
    (comp (ref "R208")
      (value "6.8k")
      (footprint "eagle-import:R0603")
      (libsource (lib "eagle-import") (part "R-US_R0603"))
    )
    (comp (ref "R209")
      (value "120k")
      (footprint "eagle-import:R0603")
      (libsource (lib "eagle-import") (part "R-US_R0603"))
    )
    (comp (ref "R210")
      (value "1M")
      (footprint "eagle-import:0603")
      (libsource (lib "eagle-import") (part "R-0603"))
    )
    (comp (ref "R211")
      (value "3.9k")
      (footprint "eagle-import:R0603")
      (libsource (lib "eagle-import") (part "R-US_R0603"))
    )
    (comp (ref "TP69")
      (value "P1-13")
      (footprint "eagle-import:P1-13@1")
      (libsource (lib "eagle-import") (part "P1-13"))
    )
    (comp (ref "U8")
      (value "TPA3111D1PWP")
      (footprint "eagle-import:TSSOP28_EP")
      (fields (field (name "MANUFACTURER") "TI"))
      (libsource (lib "eagle-import") (part "IC_TI_TPA3111D1PWP"))
    )
    (comp (ref "U9")
      (value "OPA322SAIDBVT")
      (footprint "eagle-import:SOT23-6")
      (fields (field (name "MANUFACTURER") "TI"))
      (libsource (lib "eagle-import") (part "IC_TI_OPA322SDBVAI"))
    )
  )
  (nets
    (net (code "1") (name "+3.3V") (class "Default")
      (node (ref "C1") (pin "1") (pinfunction "1_1") (pintype "passive"))
      (node (ref "C157") (pin "1") (pinfunction "1_1") (pintype "passive"))
      (node (ref "C16") (pin "2") (pinfunction "2_2") (pintype "passive"))
      (node (ref "C17") (pin "1") (pinfunction "1_1") (pintype "passive"))
      (node (ref "C2") (pin "1") (pinfunction "1_1") (pintype "passive"))
      (node (ref "C29") (pin "2") (pinfunction "2_2") (pintype "passive"))
      (node (ref "C5") (pin "1") (pinfunction "1_1") (pintype "passive"))
      (node (ref "C6") (pin "1") (pinfunction "1_1") (pintype "passive"))
      (node (ref "C8") (pin "1") (pinfunction "1_1") (pintype "passive"))
      (node (ref "C9") (pin "1") (pinfunction "1_1") (pintype "passive"))
      (node (ref "D27") (pin "+") (pinfunction "C_+") (pintype "passive"))
      (node (ref "D31") (pin "4") (pinfunction "K_4") (pintype "passive"))
      (node (ref "D31") (pin "5") (pinfunction "K_5") (pintype "passive"))
      (node (ref "IC3") (pin "16") (pinfunction "VDD16_16") (pintype "power_in"))
      (node (ref "IC3") (pin "2") (pinfunction "VDD2_2") (pintype "power_in"))
      (node (ref "IC3") (pin "37") (pinfunction "VDD37_37") (pintype "power_in"))
      (node (ref "IC3") (pin "46") (pinfunction "VDD46_46") (pintype "power_in"))
      (node (ref "IC3") (pin "62") (pinfunction "VDD62_62") (pintype "power_in"))
      (node (ref "IC3") (pin "86") (pinfunction "VDD86_86") (pintype "power_in"))
      (node (ref "J1") (pin "9") (pinfunction "9_9") (pintype "passive"))
      (node (ref "J11") (pin "2") (pinfunction "2_2") (pintype "passive"))
      (node (ref "J18") (pin "5") (pinfunction "5_5") (pintype "bidirectional"))
      (node (ref "J8") (pin "10") (pinfunction "10_10") (pintype "passive"))
      (node (ref "Q7") (pin "1") (pinfunction "S_1") (pintype "passive"))
      (node (ref "Q7") (pin "4") (pinfunction "S_4") (pintype "passive"))
      (node (ref "R1") (pin "2") (pinfunction "2_2") (pintype "passive"))
      (node (ref "R12") (pin "2") (pinfunction "2_2") (pintype "passive"))
      (node (ref "R14") (pin "2") (pinfunction "2_2") (pintype "passive"))
      (node (ref "R15") (pin "2") (pinfunction "2_2") (pintype "passive"))
      (node (ref "R167") (pin "2") (pinfunction "2_2") (pintype "passive"))
      (node (ref "R186") (pin "2") (pinfunction "2_2") (pintype "passive"))
      (node (ref "R187") (pin "2") (pinfunction "2_2") (pintype "passive"))
      (node (ref "R190") (pin "2") (pinfunction "2_2") (pintype "passive"))
      (node (ref "R2") (pin "7") (pinfunction "2_7") (pintype "passive"))
      (node (ref "R2") (pin "8") (pinfunction "2_8") (pintype "passive"))
      (node (ref "R37") (pin "2") (pinfunction "2_2") (pintype "passive"))
      (node (ref "TP64") (pin "TP") (pinfunction "TP_TP") (pintype "input"))
      (node (ref "TP9") (pin "P$1") (pinfunction "TP_P$1") (pintype "passive"))
      (node (ref "U1") (pin "1") (pinfunction "DVCC_1") (pintype "bidirectional"))
      (node (ref "U1") (pin "12") (pinfunction "SVBAT_12") (pintype "bidirectional"))
      (node (ref "U1") (pin "13") (pinfunction "PVBAT_13") (pintype "bidirectional"))
      (node (ref "U2") (pin "1") (pinfunction "VOUT_1") (pintype "bidirectional"))
    )
    (net (code "2") (name "+3.3V{slash}1") (class "Default")
      (node (ref "C22") (pin "1") (pinfunction "1_1") (pintype "passive"))
      (node (ref "C33") (pin "1") (pinfunction "1_1") (pintype "passive"))
      (node (ref "C37") (pin "1") (pinfunction "1_1") (pintype "passive"))
      (node (ref "C48") (pin "1") (pinfunction "1_1") (pintype "passive"))
      (node (ref "IC5") (pin "7") (pinfunction "A0_7") (pintype "input"))
      (node (ref "IC5") (pin "8") (pinfunction "VCC_8") (pintype "power_in"))
      (node (ref "IC6") (pin "8") (pinfunction "VCC_8") (pintype "power_in"))
      (node (ref "IC8") (pin "3") (pinfunction "/WP_3") (pintype "input"))
      (node (ref "IC8") (pin "7") (pinfunction "/HOLD_7") (pintype "input"))
      (node (ref "IC8") (pin "8") (pinfunction "VCC_8") (pintype "power_in"))
      (node (ref "J49") (pin "2") (pinfunction "2_2") (pintype "passive"))
      (node (ref "Q7") (pin "6") (pinfunction "D_6") (pintype "passive"))
      (node (ref "Q7") (pin "P1") (pinfunction "D1_P1") (pintype "passive"))
      (node (ref "R200") (pin "1") (pinfunction "1_1") (pintype "passive"))
      (node (ref "R201") (pin "1") (pinfunction "1_1") (pintype "passive"))
      (node (ref "R205") (pin "2") (pinfunction "2_2") (pintype "passive"))
      (node (ref "R206") (pin "2") (pinfunction "2_2") (pintype "passive"))
      (node (ref "R24") (pin "1") (pinfunction "1_1") (pintype "passive"))
      (node (ref "R25") (pin "1") (pinfunction "1_1") (pintype "passive"))
      (node (ref "R30") (pin "1") (pinfunction "1_1") (pintype "passive"))
      (node (ref "R31") (pin "2") (pinfunction "2_2") (pintype "passive"))
      (node (ref "R32") (pin "2") (pinfunction "2_2") (pintype "passive"))
      (node (ref "TP8") (pin "P$1") (pinfunction "TP_P$1") (pintype "passive"))
      (node (ref "U3") (pin "8") (pinfunction "VDD_8") (pintype "bidirectional"))
    )
    (net (code "3") (name "+3.3V{slash}2") (class "Default")
      (node (ref "C14") (pin "1") (pinfunction "1_1") (pintype "passive"))
      (node (ref "C35") (pin "2") (pinfunction "2_2") (pintype "passive"))
      (node (ref "IC2") (pin "8") (pinfunction "VCC_8") (pintype "power_in"))
      (node (ref "J18") (pin "10") (pinfunction "10_10") (pintype "bidirectional"))
      (node (ref "J2") (pin "2") (pinfunction "2_2") (pintype "passive"))
      (node (ref "J30") (pin "6") (pinfunction "VCC_6") (pintype "bidirectional"))
      (node (ref "JP1") (pin "2") (pinfunction "2_2") (pintype "passive"))
      (node (ref "Q7") (pin "3") (pinfunction "D_3") (pintype "passive"))
      (node (ref "Q7") (pin "P2") (pinfunction "D1_P2") (pintype "passive"))
      (node (ref "R11") (pin "2") (pinfunction "2_2") (pintype "passive"))
    )
    (net (code "4") (name "+5V") (class "Default")
      (node (ref "C149") (pin "1") (pinfunction "1_1") (pintype "passive"))
      (node (ref "C150") (pin "1") (pinfunction "1_1") (pintype "passive"))
      (node (ref "C156") (pin "1") (pinfunction "PIN+_1") (pintype "passive"))
      (node (ref "C158") (pin "1") (pinfunction "1_1") (pintype "passive"))
      (node (ref "C160") (pin "2") (pinfunction "2_2") (pintype "passive"))
      (node (ref "D28") (pin "+") (pinfunction "C_+") (pintype "passive"))
      (node (ref "J18") (pin "4") (pinfunction "4_4") (pintype "bidirectional"))
      (node (ref "L14") (pin "2") (pinfunction "2_2") (pintype "passive"))
      (node (ref "R194") (pin "1") (pinfunction "1_1") (pintype "passive"))
      (node (ref "TP65") (pin "TP") (pinfunction "TP_TP") (pintype "input"))
      (node (ref "U2") (pin "8") (pinfunction "VIN_8") (pintype "bidirectional"))
    )
    (net (code "5") (name "+SMB") (class "Default")
      (node (ref "C11") (pin "1") (pinfunction "1_1") (pintype "passive"))
      (node (ref "C135") (pin "1") (pinfunction "1_1") (pintype "passive"))
      (node (ref "C152") (pin "1") (pinfunction "1_1") (pintype "passive"))
      (node (ref "C153") (pin "1") (pinfunction "1_1") (pintype "passive"))
      (node (ref "C154") (pin "1") (pinfunction "1_1") (pintype "passive"))
      (node (ref "C155") (pin "1") (pinfunction "1_1") (pintype "passive"))
      (node (ref "C27") (pin "1") (pinfunction "1_1") (pintype "passive"))
      (node (ref "C28") (pin "1") (pinfunction "1_1") (pintype "passive"))
      (node (ref "D2") (pin "A") (pinfunction "A_A") (pintype "passive"))
      (node (ref "IC21") (pin "6") (pinfunction "VIN_6") (pintype "power_in"))
      (node (ref "IC21") (pin "8") (pinfunction "MODE_8") (pintype "input"))
      (node (ref "IC9") (pin "5") (pinfunction "VIN_5") (pintype "power_in"))
      (node (ref "J1") (pin "10") (pinfunction "10_10") (pintype "passive"))
      (node (ref "J18") (pin "2") (pinfunction "2_2") (pintype "bidirectional"))
      (node (ref "J7") (pin "2") (pinfunction "2_2") (pintype "passive"))
      (node (ref "J9") (pin "2") (pinfunction "2_2") (pintype "passive"))
      (node (ref "Q14") (pin "4") (pinfunction "VIN-_4") (pintype "input"))
      (node (ref "Q15") (pin "3") (pinfunction "S_3") (pintype "passive"))
      (node (ref "Q18") (pin "3") (pinfunction "S_3") (pintype "passive"))
      (node (ref "Q2") (pin "4") (pinfunction "Q2S_4") (pintype "bidirectional"))
      (node (ref "Q5") (pin "4") (pinfunction "Q2S_4") (pintype "bidirectional"))
      (node (ref "R154") (pin "2") (pinfunction "2_2") (pintype "passive"))
      (node (ref "R156") (pin "2") (pinfunction "2_2") (pintype "passive"))
      (node (ref "R170") (pin "1") (pinfunction "1_1") (pintype "passive"))
      (node (ref "R189") (pin "2") (pinfunction "2_2") (pintype "passive"))
      (node (ref "R20") (pin "6") (pinfunction "2_6") (pintype "passive"))
      (node (ref "R3") (pin "1") (pinfunction "1_1") (pintype "passive"))
      (node (ref "R40") (pin "2") (pinfunction "2_2") (pintype "passive"))
      (node (ref "R41") (pin "2") (pinfunction "2_2") (pintype "passive"))
    )
    (net (code "6") (name "+SMB_PRE") (class "Default")
      (node (ref "F3") (pin "1") (pinfunction "1_1") (pintype "passive"))
      (node (ref "J15") (pin "9") (pinfunction "9_9") (pintype "bidirectional"))
      (node (ref "J15") (pin "9A") (pinfunction "9_9A") (pintype "bidirectional"))
      (node (ref "J45") (pin "4") (pinfunction "4_4") (pintype "passive"))
    )
    (net (code "7") (name "3V3_AUD") (class "Default")
      (node (ref "C180") (pin "1") (pinfunction "1_1") (pintype "passive"))
      (node (ref "C181") (pin "1") (pinfunction "1_1") (pintype "passive"))
      (node (ref "C182") (pin "1") (pinfunction "1_1") (pintype "passive"))
      (node (ref "R206") (pin "1") (pinfunction "1_1") (pintype "passive"))
      (node (ref "R207") (pin "1") (pinfunction "1_1") (pintype "passive"))
      (node (ref "U9") (pin "6") (pinfunction "V+_6") (pintype "power_in"))
    )
    (net (code "8") (name "5V_ON") (class "Default")
      (node (ref "C163") (pin "1") (pinfunction "1_1") (pintype "passive"))
      (node (ref "IC21") (pin "1") (pinfunction "RUN/SS_1") (pintype "input"))
      (node (ref "IC3") (pin "92") (pinfunction "RA7/CN40_92") (pintype "bidirectional"))
    )
    (net (code "9") (name "18V_GND") (class "Default")
      (node (ref "C39") (pin "2") (pinfunction "2_2") (pintype "passive"))
      (node (ref "C40") (pin "1") (pinfunction "1_1") (pintype "passive"))
      (node (ref "R34") (pin "1") (pinfunction "1_1") (pintype "passive"))
      (node (ref "R39") (pin "1") (pinfunction "1_1") (pintype "passive"))
      (node (ref "U3") (pin "5") (pinfunction "AIN1_5") (pintype "bidirectional"))
    )
    (net (code "10") (name "18V_SENSE") (class "Default")
      (node (ref "J15") (pin "1") (pinfunction "1_1") (pintype "bidirectional"))
      (node (ref "J15") (pin "1A") (pinfunction "1_1A") (pintype "bidirectional"))
      (node (ref "J15") (pin "3") (pinfunction "3_3") (pintype "bidirectional"))
      (node (ref "J15") (pin "3A") (pinfunction "3_3A") (pintype "bidirectional"))
      (node (ref "R33") (pin "2") (pinfunction "2_2") (pintype "passive"))
    )
    (net (code "11") (name "A+") (class "Default")
      (node (ref "IC2") (pin "6") (pinfunction "A_6") (pintype "bidirectional"))
      (node (ref "L2") (pin "1") (pinfunction "1_1") (pintype "passive"))
      (node (ref "Q3") (pin "3") (pinfunction "3_3") (pintype "passive"))
      (node (ref "R11") (pin "1") (pinfunction "1_1") (pintype "passive"))
      (node (ref "R9") (pin "1") (pinfunction "1_1") (pintype "passive"))
    )
    (net (code "12") (name "A1") (class "Default")
      (node (ref "J7") (pin "3") (pinfunction "3_3") (pintype "passive"))
      (node (ref "J9") (pin "3") (pinfunction "3_3") (pintype "passive"))
      (node (ref "L2") (pin "2") (pinfunction "2_2") (pintype "passive"))
    )
    (net (code "13") (name "ACT_S1_B") (class "Default")
      (node (ref "IC3") (pin "52") (pinfunction "CN70/RP30/RF2_52") (pintype "bidirectional"))
      (node (ref "Q20") (pin "1") (pinfunction "G_1") (pintype "passive"))
      (node (ref "R183") (pin "1") (pinfunction "1_1") (pintype "passive"))
    )
    (net (code "14") (name "ACT_S2_B") (class "Default")
      (node (ref "IC3") (pin "53") (pinfunction "CN74/RP15/RF8_53") (pintype "bidirectional"))
      (node (ref "Q21") (pin "1") (pinfunction "G_1") (pintype "passive"))
      (node (ref "R184") (pin "1") (pinfunction "1_1") (pintype "passive"))
    )
    (net (code "15") (name "AGND") (class "Default")
      (node (ref "C165") (pin "2") (pinfunction "2_2") (pintype "passive"))
      (node (ref "C166") (pin "2") (pinfunction "2_2") (pintype "passive"))
      (node (ref "C167") (pin "2") (pinfunction "2_2") (pintype "passive"))
      (node (ref "C168") (pin "2") (pinfunction "2_2") (pintype "passive"))
      (node (ref "C169") (pin "2") (pinfunction "2_2") (pintype "passive"))
      (node (ref "C170") (pin "2") (pinfunction "2_2") (pintype "passive"))
      (node (ref "C171") (pin "2") (pinfunction "2_2") (pintype "passive"))
      (node (ref "C172") (pin "2") (pinfunction "2_2") (pintype "passive"))
      (node (ref "C176") (pin "2") (pinfunction "2_2") (pintype "passive"))
      (node (ref "C177") (pin "1") (pinfunction "1_1") (pintype "passive"))
      (node (ref "C179") (pin "2") (pinfunction "2_2") (pintype "passive"))
      (node (ref "C180") (pin "2") (pinfunction "2_2") (pintype "passive"))
      (node (ref "C181") (pin "2") (pinfunction "2_2") (pintype "passive"))
      (node (ref "C182") (pin "2") (pinfunction "2_2") (pintype "passive"))
      (node (ref "J17") (pin "1") (pinfunction "1_1") (pintype "bidirectional"))
      (node (ref "J17") (pin "12") (pinfunction "12_12") (pintype "bidirectional"))
      (node (ref "J17") (pin "3") (pinfunction "3_3") (pintype "bidirectional"))
      (node (ref "J17") (pin "6") (pinfunction "6_6") (pintype "bidirectional"))
      (node (ref "J17") (pin "9") (pinfunction "9_9") (pintype "bidirectional"))
      (node (ref "J47") (pin "3") (pinfunction "3_3") (pintype "passive"))
      (node (ref "J47") (pin "4") (pinfunction "4_4") (pintype "passive"))
      (node (ref "J48") (pin "1") (pinfunction "1_1") (pintype "passive"))
      (node (ref "L17") (pin "2") (pinfunction "2_2") (pintype "passive"))
      (node (ref "Q24") (pin "2") (pinfunction "S_2") (pintype "passive"))
      (node (ref "R202") (pin "2") (pinfunction "2_2") (pintype "passive"))
      (node (ref "R203") (pin "2") (pinfunction "2_2") (pintype "passive"))
      (node (ref "R210") (pin "2") (pinfunction "2_2") (pintype "passive"))
      (node (ref "R211") (pin "2") (pinfunction "2_2") (pintype "passive"))
      (node (ref "U8") (pin "19") (pinfunction "PGND_19") (pintype "power_in"))
      (node (ref "U8") (pin "24") (pinfunction "PGND_24") (pintype "power_in"))
      (node (ref "U8") (pin "3") (pinfunction "GND_3") (pintype "power_in"))
      (node (ref "U8") (pin "4") (pinfunction "GND_4") (pintype "power_in"))
      (node (ref "U8") (pin "8") (pinfunction "AGND_8") (pintype "power_in"))
      (node (ref "U8") (pin "EP") (pinfunction "EP_EP") (pintype "power_in"))
      (node (ref "U9") (pin "2") (pinfunction "V-_2") (pintype "power_in"))
    )
    (net (code "16") (name "AUD_AMP_FAULT#") (class "Default")
      (node (ref "R204") (pin "1") (pinfunction "1_1") (pintype "passive"))
      (node (ref "R205") (pin "1") (pinfunction "1_1") (pintype "passive"))
      (node (ref "U8") (pin "1") (pinfunction "~{SD}_1") (pintype "input"))
      (node (ref "U8") (pin "2") (pinfunction "~{FAULT}_2") (pintype "output"))
    )
    (net (code "17") (name "AUD_AMP_G0") (class "Default")
      (node (ref "IC3") (pin "41") (pinfunction "RB12/AN12/CN30_41") (pintype "bidirectional"))
      (node (ref "R200") (pin "2") (pinfunction "2_2") (pintype "passive"))
      (node (ref "R202") (pin "1") (pinfunction "1_1") (pintype "passive"))
      (node (ref "TP4") (pin "P$1") (pinfunction "TP_P$1") (pintype "passive"))
      (node (ref "U8") (pin "5") (pinfunction "GAIN0_5") (pintype "input"))
    )
    (net (code "18") (name "AUD_AMP_G1") (class "Default")
      (node (ref "IC3") (pin "42") (pinfunction "RB13/AN13/CN31_42") (pintype "bidirectional"))
      (node (ref "R201") (pin "2") (pinfunction "2_2") (pintype "passive"))
      (node (ref "R203") (pin "1") (pinfunction "1_1") (pintype "passive"))
      (node (ref "TP5") (pin "P$1") (pinfunction "TP_P$1") (pintype "passive"))
      (node (ref "U8") (pin "6") (pinfunction "GAIN1_6") (pintype "input"))
    )
    (net (code "19") (name "AUD_AMP_INN") (class "Default")
      (node (ref "C177") (pin "2") (pinfunction "2_2") (pintype "passive"))
      (node (ref "U8") (pin "11") (pinfunction "INN_11") (pintype "input"))
    )
    (net (code "20") (name "AUD_AMP_INP") (class "Default")
      (node (ref "C174") (pin "2") (pinfunction "2_2") (pintype "passive"))
      (node (ref "C175") (pin "2") (pinfunction "2_2") (pintype "passive"))
      (node (ref "U8") (pin "12") (pinfunction "INP_12") (pintype "input"))
    )
    (net (code "21") (name "AUD_BSN") (class "Default")
      (node (ref "C178") (pin "1") (pinfunction "1_1") (pintype "passive"))
      (node (ref "U8") (pin "22") (pinfunction "BSN_22") (pintype "input"))
      (node (ref "U8") (pin "26") (pinfunction "BSN_26") (pintype "input"))
    )
    (net (code "22") (name "AUD_BSP") (class "Default")
      (node (ref "C173") (pin "1") (pinfunction "1_1") (pintype "passive"))
      (node (ref "U8") (pin "17") (pinfunction "BSP_17") (pintype "input"))
      (node (ref "U8") (pin "21") (pinfunction "BSP_21") (pintype "input"))
    )
    (net (code "23") (name "AUD_GVDD") (class "Default")
      (node (ref "C172") (pin "1") (pinfunction "1_1") (pintype "passive"))
      (node (ref "U8") (pin "10") (pinfunction "PLIMIT_10") (pintype "input"))
      (node (ref "U8") (pin "9") (pinfunction "GVDD_9") (pintype "output"))
    )
    (net (code "24") (name "B-") (class "Default")
      (node (ref "IC2") (pin "7") (pinfunction "B_7") (pintype "bidirectional"))
      (node (ref "L1") (pin "1") (pinfunction "1_1") (pintype "passive"))
      (node (ref "Q3") (pin "2") (pinfunction "2_2") (pintype "passive"))
      (node (ref "R10") (pin "2") (pinfunction "2_2") (pintype "passive"))
      (node (ref "R9") (pin "2") (pinfunction "2_2") (pintype "passive"))
    )
    (net (code "25") (name "B1") (class "Default")
      (node (ref "J7") (pin "4") (pinfunction "4_4") (pintype "passive"))
      (node (ref "J9") (pin "4") (pinfunction "4_4") (pintype "passive"))
      (node (ref "L1") (pin "2") (pinfunction "2_2") (pintype "passive"))
    )
    (net (code "26") (name "B12_BOOT") (class "Default")
      (node (ref "C126") (pin "1") (pinfunction "1_1") (pintype "passive"))
      (node (ref "U6") (pin "11") (pinfunction "BOOT_11") (pintype "passive"))
    )
    (net (code "27") (name "B12_COMP") (class "Default")
      (node (ref "C131") (pin "1") (pinfunction "1_1") (pintype "passive"))
      (node (ref "R164") (pin "2") (pinfunction "2_2") (pintype "passive"))
      (node (ref "U6") (pin "3") (pinfunction "COMP_3") (pintype "passive"))
    )
    (net (code "28") (name "B12_FB") (class "Default")
      (node (ref "R160") (pin "1") (pinfunction "1_1") (pintype "passive"))
      (node (ref "R166") (pin "2") (pinfunction "2_2") (pintype "passive"))
      (node (ref "U6") (pin "4") (pinfunction "FB_4") (pintype "input"))
    )
    (net (code "29") (name "B12_FEED") (class "Default")
      (node (ref "L11") (pin "2") (pinfunction "2_2") (pintype "passive"))
      (node (ref "R158") (pin "2") (pinfunction "2_2") (pintype "passive"))
      (node (ref "R42") (pin "2") (pinfunction "2_2") (pintype "passive"))
      (node (ref "R43") (pin "2") (pinfunction "2_2") (pintype "passive"))
    )
    (net (code "30") (name "B12_HDRV") (class "Default")
      (node (ref "R161") (pin "2") (pinfunction "2_2") (pintype "passive"))
      (node (ref "U6") (pin "13") (pinfunction "HDRV_13") (pintype "output"))
    )
    (net (code "31") (name "B12_HG") (class "Default")
      (node (ref "Q16") (pin "3") (pinfunction "TG_3") (pintype "passive"))
      (node (ref "R161") (pin "1") (pinfunction "1_1") (pintype "passive"))
    )
    (net (code "32") (name "B12_ISNS+") (class "Default")
      (node (ref "C124") (pin "1") (pinfunction "1_1") (pintype "passive"))
      (node (ref "R157") (pin "1") (pinfunction "1_1") (pintype "passive"))
      (node (ref "U6") (pin "6") (pinfunction "ISNS+_6") (pintype "input"))
    )
    (net (code "33") (name "B12_ISNS-") (class "Default")
      (node (ref "C124") (pin "2") (pinfunction "2_2") (pintype "passive"))
      (node (ref "R158") (pin "1") (pinfunction "1_1") (pintype "passive"))
      (node (ref "U6") (pin "5") (pinfunction "ISNS-_5") (pintype "input"))
    )
    (net (code "34") (name "B12_L") (class "Default")
      (node (ref "D20") (pin "A") (pinfunction "A_A") (pintype "passive"))
      (node (ref "L11") (pin "1") (pinfunction "1_1") (pintype "passive"))
      (node (ref "Q16") (pin "6") (pinfunction "VSW_6") (pintype "passive"))
      (node (ref "Q16") (pin "7") (pinfunction "VSW_7") (pintype "passive"))
      (node (ref "Q16") (pin "8") (pinfunction "VSW_8") (pintype "passive"))
    )
    (net (code "35") (name "B12_LDRV") (class "Default")
      (node (ref "R163") (pin "2") (pinfunction "2_2") (pintype "passive"))
      (node (ref "U6") (pin "8") (pinfunction "LDRV_8") (pintype "output"))
    )
    (net (code "36") (name "B12_LG") (class "Default")
      (node (ref "Q16") (pin "5") (pinfunction "BG_5") (pintype "passive"))
      (node (ref "R163") (pin "1") (pinfunction "1_1") (pintype "passive"))
    )
    (net (code "37") (name "B12_PG") (class "Default")
      (node (ref "IC3") (pin "69") (pinfunction "CN54/RP4/RD9_69") (pintype "bidirectional"))
      (node (ref "R167") (pin "1") (pinfunction "1_1") (pintype "passive"))
      (node (ref "U6") (pin "14") (pinfunction "PGOOD_14") (pintype "open_collector"))
    )
    (net (code "38") (name "B12_RC") (class "Default")
      (node (ref "C133") (pin "1") (pinfunction "1_1") (pintype "passive"))
      (node (ref "R164") (pin "1") (pinfunction "1_1") (pintype "passive"))
    )
    (net (code "39") (name "B12_RT") (class "Default")
      (node (ref "R165") (pin "2") (pinfunction "2_2") (pintype "passive"))
      (node (ref "U6") (pin "1") (pinfunction "RT/CLK_1") (pintype "passive"))
    )
    (net (code "40") (name "B12_SS") (class "Default")
      (node (ref "C132") (pin "1") (pinfunction "1_1") (pintype "passive"))
      (node (ref "U6") (pin "2") (pinfunction "SS_2") (pintype "passive"))
    )
    (net (code "41") (name "B12_SW") (class "Default")
      (node (ref "C126") (pin "2") (pinfunction "2_2") (pintype "passive"))
      (node (ref "Q16") (pin "4") (pinfunction "TGR_4") (pintype "passive"))
      (node (ref "U6") (pin "12") (pinfunction "SW_12") (pintype "output"))
    )
    (net (code "42") (name "B12_VCC") (class "Default")
      (node (ref "C127") (pin "1") (pinfunction "1_1") (pintype "passive"))
      (node (ref "U6") (pin "10") (pinfunction "VCC_10") (pintype "output"))
    )
    (net (code "43") (name "BAT_GND") (class "Default")
      (node (ref "C41") (pin "2") (pinfunction "2_2") (pintype "passive"))
      (node (ref "C42") (pin "1") (pinfunction "1_1") (pintype "passive"))
      (node (ref "R36") (pin "1") (pinfunction "1_1") (pintype "passive"))
      (node (ref "R38") (pin "1") (pinfunction "1_1") (pintype "passive"))
      (node (ref "U3") (pin "7") (pinfunction "AIN3_7") (pintype "bidirectional"))
    )
    (net (code "44") (name "BAT_SENSE") (class "Default")
      (node (ref "J15") (pin "5") (pinfunction "5_5") (pintype "bidirectional"))
      (node (ref "J15") (pin "5A") (pinfunction "5_5A") (pintype "bidirectional"))
      (node (ref "J15") (pin "7") (pinfunction "7_7") (pintype "bidirectional"))
      (node (ref "J15") (pin "7A") (pinfunction "7_7A") (pintype "bidirectional"))
      (node (ref "R35") (pin "2") (pinfunction "2_2") (pintype "passive"))
    )
    (net (code "45") (name "BTN_1") (class "Default")
      (node (ref "IC4") (pin "1") (pinfunction "GP0/PGD_1") (pintype "bidirectional"))
      (node (ref "J12") (pin "4") (pinfunction "4_4") (pintype "passive"))
      (node (ref "J19") (pin "10") (pinfunction "10_10") (pintype "bidirectional"))
      (node (ref "R2") (pin "2") (pinfunction "1_2") (pintype "passive"))
      (node (ref "R2") (pin "3") (pinfunction "1_3") (pintype "passive"))
    )
    (net (code "46") (name "BTN_1PIN_B") (class "Default")
      (node (ref "C12") (pin "1") (pinfunction "1_1") (pintype "passive"))
      (node (ref "IC3") (pin "90") (pinfunction "RG0/CN77_90") (pintype "bidirectional"))
      (node (ref "R2") (pin "6") (pinfunction "2_6") (pintype "passive"))
    )
    (net (code "47") (name "BTN_2") (class "Default")
      (node (ref "IC4") (pin "3") (pinfunction "GP1/PGC_3") (pintype "bidirectional"))
      (node (ref "J12") (pin "5") (pinfunction "5_5") (pintype "passive"))
      (node (ref "J19") (pin "12") (pinfunction "12_12") (pintype "bidirectional"))
      (node (ref "R2") (pin "1") (pinfunction "1_1") (pintype "passive"))
      (node (ref "R2") (pin "4") (pinfunction "1_4") (pintype "passive"))
    )
    (net (code "48") (name "BTN_2PIN_B") (class "Default")
      (node (ref "C13") (pin "1") (pinfunction "1_1") (pintype "passive"))
      (node (ref "IC3") (pin "89") (pinfunction "RG1/CN78_89") (pintype "bidirectional"))
      (node (ref "R2") (pin "5") (pinfunction "2_5") (pintype "passive"))
    )
    (net (code "49") (name "CL_IRQ") (class "Default")
      (node (ref "IC3") (pin "20") (pinfunction "RB5/AN5/CN7/RP18_20") (pintype "bidirectional"))
      (node (ref "J1") (pin "4") (pinfunction "4_4") (pintype "passive"))
    )
    (net (code "50") (name "CON_LED") (class "Default")
      (node (ref "IC3") (pin "40") (pinfunction "CN75/RPI32/RF12_40") (pintype "bidirectional"))
      (node (ref "JP1") (pin "6") (pinfunction "6_6") (pintype "passive"))
    )
    (net (code "51") (name "DCDC_12V_EN") (class "Default")
      (node (ref "IC3") (pin "84") (pinfunction "CN16/RD7_84") (pintype "bidirectional"))
      (node (ref "Q15") (pin "2") (pinfunction "G_2") (pintype "passive"))
      (node (ref "R162") (pin "2") (pinfunction "2_2") (pintype "passive"))
      (node (ref "U6") (pin "15") (pinfunction "EN_15") (pintype "input"))
    )
    (net (code "52") (name "DGND") (class "Default")
      (node (ref "C1") (pin "2") (pinfunction "2_2") (pintype "passive"))
      (node (ref "C10") (pin "1") (pinfunction "1_1") (pintype "passive"))
      (node (ref "C11") (pin "2") (pinfunction "2_2") (pintype "passive"))
      (node (ref "C114") (pin "1") (pinfunction "1_1") (pintype "passive"))
      (node (ref "C115") (pin "1") (pinfunction "1_1") (pintype "passive"))
      (node (ref "C12") (pin "2") (pinfunction "2_2") (pintype "passive"))
      (node (ref "C121") (pin "1") (pinfunction "1_1") (pintype "passive"))
      (node (ref "C122") (pin "2") (pinfunction "2_2") (pintype "passive"))
      (node (ref "C123") (pin "2") (pinfunction "2_2") (pintype "passive"))
      (node (ref "C125") (pin "2") (pinfunction "2_2") (pintype "passive"))
      (node (ref "C127") (pin "2") (pinfunction "2_2") (pintype "passive"))
      (node (ref "C128") (pin "2") (pinfunction "2_2") (pintype "passive"))
      (node (ref "C129") (pin "2") (pinfunction "2_2") (pintype "passive"))
      (node (ref "C13") (pin "2") (pinfunction "2_2") (pintype "passive"))
      (node (ref "C130") (pin "2") (pinfunction "2_2") (pintype "passive"))
      (node (ref "C131") (pin "2") (pinfunction "2_2") (pintype "passive"))
      (node (ref "C132") (pin "2") (pinfunction "2_2") (pintype "passive"))
      (node (ref "C133") (pin "2") (pinfunction "2_2") (pintype "passive"))
      (node (ref "C134") (pin "2") (pinfunction "2_2") (pintype "passive"))
      (node (ref "C135") (pin "2") (pinfunction "2_2") (pintype "passive"))
      (node (ref "C136") (pin "2") (pinfunction "2_2") (pintype "passive"))
      (node (ref "C137") (pin "2") (pinfunction "2_2") (pintype "passive"))
      (node (ref "C139") (pin "2") (pinfunction "2_2") (pintype "passive"))
      (node (ref "C14") (pin "2") (pinfunction "2_2") (pintype "passive"))
      (node (ref "C141") (pin "2") (pinfunction "2_2") (pintype "passive"))
      (node (ref "C142") (pin "2") (pinfunction "2_2") (pintype "passive"))
      (node (ref "C143") (pin "2") (pinfunction "2_2") (pintype "passive"))
      (node (ref "C144") (pin "2") (pinfunction "2_2") (pintype "passive"))
      (node (ref "C145") (pin "2") (pinfunction "2_2") (pintype "passive"))
      (node (ref "C146") (pin "2") (pinfunction "2_2") (pintype "passive"))
      (node (ref "C147") (pin "2") (pinfunction "2_2") (pintype "passive"))
      (node (ref "C148") (pin "2") (pinfunction "2_2") (pintype "passive"))
      (node (ref "C149") (pin "2") (pinfunction "2_2") (pintype "passive"))
      (node (ref "C150") (pin "2") (pinfunction "2_2") (pintype "passive"))
      (node (ref "C152") (pin "2") (pinfunction "2_2") (pintype "passive"))
      (node (ref "C153") (pin "2") (pinfunction "2_2") (pintype "passive"))
      (node (ref "C154") (pin "2") (pinfunction "2_2") (pintype "passive"))
      (node (ref "C156") (pin "2") (pinfunction "PIN-_2") (pintype "passive"))
      (node (ref "C157") (pin "2") (pinfunction "2_2") (pintype "passive"))
      (node (ref "C158") (pin "2") (pinfunction "2_2") (pintype "passive"))
      (node (ref "C16") (pin "1") (pinfunction "1_1") (pintype "passive"))
      (node (ref "C163") (pin "2") (pinfunction "2_2") (pintype "passive"))
      (node (ref "C164") (pin "2") (pinfunction "2_2") (pintype "passive"))
      (node (ref "C17") (pin "2") (pinfunction "2_2") (pintype "passive"))
      (node (ref "C18") (pin "1") (pinfunction "1_1") (pintype "passive"))
      (node (ref "C187") (pin "-") (pinfunction "-_-") (pintype "passive"))
      (node (ref "C19") (pin "1") (pinfunction "1_1") (pintype "passive"))
      (node (ref "C2") (pin "2") (pinfunction "2_2") (pintype "passive"))
      (node (ref "C20") (pin "1") (pinfunction "1_1") (pintype "passive"))
      (node (ref "C21") (pin "2") (pinfunction "2_2") (pintype "passive"))
      (node (ref "C22") (pin "2") (pinfunction "2_2") (pintype "passive"))
      (node (ref "C23") (pin "2") (pinfunction "2_2") (pintype "passive"))
      (node (ref "C25") (pin "2") (pinfunction "2_2") (pintype "passive"))
      (node (ref "C26") (pin "2") (pinfunction "2_2") (pintype "passive"))
      (node (ref "C27") (pin "2") (pinfunction "2_2") (pintype "passive"))
      (node (ref "C28") (pin "2") (pinfunction "2_2") (pintype "passive"))
      (node (ref "C29") (pin "1") (pinfunction "1_1") (pintype "passive"))
      (node (ref "C3") (pin "2") (pinfunction "2_2") (pintype "passive"))
      (node (ref "C32") (pin "2") (pinfunction "2_2") (pintype "passive"))
      (node (ref "C33") (pin "2") (pinfunction "2_2") (pintype "passive"))
      (node (ref "C34") (pin "2") (pinfunction "2_2") (pintype "passive"))
      (node (ref "C35") (pin "1") (pinfunction "1_1") (pintype "passive"))
      (node (ref "C36") (pin "2") (pinfunction "2_2") (pintype "passive"))
      (node (ref "C37") (pin "2") (pinfunction "2_2") (pintype "passive"))
      (node (ref "C38") (pin "1") (pinfunction "1_1") (pintype "passive"))
      (node (ref "C4") (pin "2") (pinfunction "2_2") (pintype "passive"))
      (node (ref "C40") (pin "2") (pinfunction "2_2") (pintype "passive"))
      (node (ref "C42") (pin "2") (pinfunction "2_2") (pintype "passive"))
      (node (ref "C43") (pin "-") (pinfunction "-_-") (pintype "passive"))
      (node (ref "C44") (pin "-") (pinfunction "-_-") (pintype "passive"))
      (node (ref "C47") (pin "2") (pinfunction "2_2") (pintype "passive"))
      (node (ref "C48") (pin "2") (pinfunction "2_2") (pintype "passive"))
      (node (ref "C5") (pin "2") (pinfunction "2_2") (pintype "passive"))
      (node (ref "C59") (pin "2") (pinfunction "2_2") (pintype "passive"))
      (node (ref "C6") (pin "2") (pinfunction "2_2") (pintype "passive"))
      (node (ref "C7") (pin "2") (pinfunction "2_2") (pintype "passive"))
      (node (ref "C8") (pin "2") (pinfunction "2_2") (pintype "passive"))
      (node (ref "C9") (pin "2") (pinfunction "2_2") (pintype "passive"))
      (node (ref "D21") (pin "-") (pinfunction "A_-") (pintype "passive"))
      (node (ref "D27") (pin "-") (pinfunction "A_-") (pintype "passive"))
      (node (ref "D28") (pin "-") (pinfunction "A_-") (pintype "passive"))
      (node (ref "D30") (pin "A") (pinfunction "A_A") (pintype "passive"))
      (node (ref "D31") (pin "1") (pinfunction "A_1") (pintype "passive"))
      (node (ref "D31") (pin "2") (pinfunction "A_2") (pintype "passive"))
      (node (ref "D32") (pin "A") (pinfunction "A_A") (pintype "passive"))
      (node (ref "D4") (pin "A") (pinfunction "A_A") (pintype "passive"))
      (node (ref "H1") (pin "P1") (pinfunction "P$1_P1") (pintype "bidirectional"))
      (node (ref "H2") (pin "P1") (pinfunction "P$1_P1") (pintype "bidirectional"))
      (node (ref "H3") (pin "P1") (pinfunction "P$1_P1") (pintype "bidirectional"))
      (node (ref "H4") (pin "P1") (pinfunction "P$1_P1") (pintype "bidirectional"))
      (node (ref "H5") (pin "P1") (pinfunction "P$1_P1") (pintype "bidirectional"))
      (node (ref "IC1") (pin "3") (pinfunction "GND_3") (pintype "power_in"))
      (node (ref "IC18") (pin "18") (pinfunction "GND2_18") (pintype "power_in"))
      (node (ref "IC18") (pin "21") (pinfunction "GND3_21") (pintype "power_in"))
      (node (ref "IC18") (pin "25") (pinfunction "AGND_25") (pintype "power_in"))
      (node (ref "IC18") (pin "26") (pinfunction "TEST_26") (pintype "bidirectional"))
      (node (ref "IC18") (pin "7") (pinfunction "GND1_7") (pintype "power_in"))
      (node (ref "IC19") (pin "4") (pinfunction "V-_4") (pintype "power_in"))
      (node (ref "IC2") (pin "5") (pinfunction "GND_5") (pintype "power_in"))
      (node (ref "IC21") (pin "4") (pinfunction "GND_4") (pintype "power_in"))
      (node (ref "IC3") (pin "15") (pinfunction "VSS15_15") (pintype "power_in"))
      (node (ref "IC3") (pin "31") (pinfunction "AVSS_31") (pintype "power_in"))
      (node (ref "IC3") (pin "36") (pinfunction "VSS36_36") (pintype "power_in"))
      (node (ref "IC3") (pin "45") (pinfunction "VSS45_45") (pintype "power_in"))
      (node (ref "IC3") (pin "65") (pinfunction "VSS65_65") (pintype "power_in"))
      (node (ref "IC3") (pin "75") (pinfunction "VSS75_75") (pintype "power_in"))
      (node (ref "IC4") (pin "2") (pinfunction "VSS_2") (pintype "power_in"))
      (node (ref "IC5") (pin "4") (pinfunction "GND_4") (pintype "power_in"))
      (node (ref "IC5") (pin "5") (pinfunction "A2_5") (pintype "input"))
      (node (ref "IC5") (pin "6") (pinfunction "A1_6") (pintype "input"))
      (node (ref "IC6") (pin "1") (pinfunction "A0_1") (pintype "input"))
      (node (ref "IC6") (pin "2") (pinfunction "A1_2") (pintype "input"))
      (node (ref "IC6") (pin "3") (pinfunction "A2_3") (pintype "input"))
      (node (ref "IC6") (pin "4") (pinfunction "GND_4") (pintype "power_in"))
      (node (ref "IC6") (pin "7") (pinfunction "WP_7") (pintype "input"))
      (node (ref "IC8") (pin "4") (pinfunction "GND_4") (pintype "power_in"))
      (node (ref "IC9") (pin "2") (pinfunction "GND_2") (pintype "power_in"))
      (node (ref "J1") (pin "1") (pinfunction "1_1") (pintype "passive"))
      (node (ref "J10") (pin "C5") (pinfunction "C5_C5") (pintype "bidirectional"))
      (node (ref "J11") (pin "3") (pinfunction "3_3") (pintype "passive"))
      (node (ref "J12") (pin "3") (pinfunction "3_3") (pintype "passive"))
      (node (ref "J15") (pin "10") (pinfunction "10_10") (pintype "bidirectional"))
      (node (ref "J15") (pin "10A") (pinfunction "10_10A") (pintype "bidirectional"))
      (node (ref "J18") (pin "6") (pinfunction "6_6") (pintype "bidirectional"))
      (node (ref "J18") (pin "9") (pinfunction "9_9") (pintype "bidirectional"))
      (node (ref "J19") (pin "1") (pinfunction "1_1") (pintype "bidirectional"))
      (node (ref "J19") (pin "11") (pinfunction "11_11") (pintype "bidirectional"))
      (node (ref "J19") (pin "3") (pinfunction "3_3") (pintype "bidirectional"))
      (node (ref "J19") (pin "5") (pinfunction "5_5") (pintype "bidirectional"))
      (node (ref "J19") (pin "7") (pinfunction "7_7") (pintype "bidirectional"))
      (node (ref "J19") (pin "9") (pinfunction "9_9") (pintype "bidirectional"))
      (node (ref "J2") (pin "1") (pinfunction "1_1") (pintype "passive"))
      (node (ref "J3") (pin "11") (pinfunction "11_11") (pintype "bidirectional"))
      (node (ref "J3") (pin "12") (pinfunction "12_12") (pintype "bidirectional"))
      (node (ref "J3") (pin "5") (pinfunction "5_5") (pintype "bidirectional"))
      (node (ref "J3") (pin "7") (pinfunction "7_7") (pintype "bidirectional"))
      (node (ref "J3") (pin "8") (pinfunction "8_8") (pintype "bidirectional"))
      (node (ref "J30") (pin "7") (pinfunction "GND_7") (pintype "bidirectional"))
      (node (ref "J41") (pin "1") (pinfunction "1_1") (pintype "passive"))
      (node (ref "J45") (pin "1") (pinfunction "1_1") (pintype "passive"))
      (node (ref "J50") (pin "1") (pinfunction "1_1") (pintype "bidirectional"))
      (node (ref "J50") (pin "2") (pinfunction "2_2") (pintype "bidirectional"))
      (node (ref "J7") (pin "1") (pinfunction "1_1") (pintype "passive"))
      (node (ref "J7") (pin "6") (pinfunction "6_6") (pintype "passive"))
      (node (ref "J8") (pin "9") (pinfunction "9_9") (pintype "passive"))
      (node (ref "J9") (pin "1") (pinfunction "1_1") (pintype "passive"))
      (node (ref "J9") (pin "6") (pinfunction "6_6") (pintype "passive"))
      (node (ref "JP1") (pin "1") (pinfunction "1_1") (pintype "passive"))
      (node (ref "L17") (pin "1") (pinfunction "1_1") (pintype "passive"))
      (node (ref "Q14") (pin "1") (pinfunction "GND_1") (pintype "power_in"))
      (node (ref "Q14") (pin "2") (pinfunction "GND1_2") (pintype "power_in"))
      (node (ref "Q15") (pin "1") (pinfunction "S_1") (pintype "passive"))
      (node (ref "Q16") (pin "EP") (pinfunction "PGND_EP") (pintype "passive"))
      (node (ref "Q18") (pin "1") (pinfunction "S_1") (pintype "passive"))
      (node (ref "Q19") (pin "EP") (pinfunction "PGND_EP") (pintype "passive"))
      (node (ref "Q2") (pin "1") (pinfunction "Q1S_1") (pintype "bidirectional"))
      (node (ref "Q20") (pin "2") (pinfunction "S_2") (pintype "passive"))
      (node (ref "Q21") (pin "2") (pinfunction "S_2") (pintype "passive"))
      (node (ref "Q3") (pin "1") (pinfunction "1_1") (pintype "passive"))
      (node (ref "Q5") (pin "1") (pinfunction "Q1S_1") (pintype "bidirectional"))
      (node (ref "R10") (pin "1") (pinfunction "1_1") (pintype "passive"))
      (node (ref "R13") (pin "1") (pinfunction "1_1") (pintype "passive"))
      (node (ref "R162") (pin "1") (pinfunction "1_1") (pintype "passive"))
      (node (ref "R165") (pin "1") (pinfunction "1_1") (pintype "passive"))
      (node (ref "R166") (pin "1") (pinfunction "1_1") (pintype "passive"))
      (node (ref "R174") (pin "2") (pinfunction "2_2") (pintype "passive"))
      (node (ref "R179") (pin "1") (pinfunction "1_1") (pintype "passive"))
      (node (ref "R182") (pin "1") (pinfunction "1_1") (pintype "passive"))
      (node (ref "R183") (pin "2") (pinfunction "2_2") (pintype "passive"))
      (node (ref "R184") (pin "2") (pinfunction "2_2") (pintype "passive"))
      (node (ref "R185") (pin "1") (pinfunction "1_1") (pintype "passive"))
      (node (ref "R197") (pin "2") (pinfunction "2_2") (pintype "passive"))
      (node (ref "R20") (pin "2") (pinfunction "1_2") (pintype "passive"))
      (node (ref "R21") (pin "5") (pinfunction "2_5") (pintype "passive"))
      (node (ref "R21") (pin "6") (pinfunction "2_6") (pintype "passive"))
      (node (ref "R26") (pin "2") (pinfunction "2_2") (pintype "passive"))
      (node (ref "R29") (pin "5") (pinfunction "2_5") (pintype "passive"))
      (node (ref "R29") (pin "6") (pinfunction "2_6") (pintype "passive"))
      (node (ref "R5") (pin "1") (pinfunction "1_1") (pintype "passive"))
      (node (ref "R6") (pin "1") (pinfunction "1_1") (pintype "passive"))
      (node (ref "TP11") (pin "P$1") (pinfunction "TP_P$1") (pintype "passive"))
      (node (ref "TP12") (pin "1") (pinfunction "TP_1") (pintype "passive"))
      (node (ref "TP66") (pin "TP") (pinfunction "TP_TP") (pintype "input"))
      (node (ref "TP67") (pin "TP") (pinfunction "TP_TP") (pintype "input"))
      (node (ref "U1") (pin "10") (pinfunction "PGND_10") (pintype "bidirectional"))
      (node (ref "U1") (pin "21") (pinfunction "PRESB_21") (pintype "bidirectional"))
      (node (ref "U1") (pin "9") (pinfunction "SGND_9") (pintype "bidirectional"))
      (node (ref "U1") (pin "PAD") (pinfunction "PAD_PAD") (pintype "bidirectional"))
      (node (ref "U2") (pin "2") (pinfunction "GND_2") (pintype "bidirectional"))
      (node (ref "U2") (pin "3") (pinfunction "GND_3") (pintype "bidirectional"))
      (node (ref "U2") (pin "5") (pinfunction "INHIBIT_5") (pintype "bidirectional"))
      (node (ref "U2") (pin "6") (pinfunction "GND_6") (pintype "bidirectional"))
      (node (ref "U2") (pin "7") (pinfunction "GND_7") (pintype "bidirectional"))
      (node (ref "U3") (pin "3") (pinfunction "VSS_3") (pintype "bidirectional"))
      (node (ref "U6") (pin "16") (pinfunction "AGND_16") (pintype "power_in"))
      (node (ref "U6") (pin "9") (pinfunction "PGND_9") (pintype "power_in"))
      (node (ref "U6") (pin "EP") (pinfunction "PPAD_EP") (pintype "power_in"))
      (node (ref "U7") (pin "16") (pinfunction "AGND_16") (pintype "power_in"))
      (node (ref "U7") (pin "9") (pinfunction "PGND_9") (pintype "power_in"))
      (node (ref "U7") (pin "EP") (pinfunction "PPAD_EP") (pintype "power_in"))
      (node (ref "X1") (pin "7") (pinfunction "1_7") (pintype "passive"))
      (node (ref "X1") (pin "8") (pinfunction "1_8") (pintype "passive"))
      (node (ref "X2") (pin "4") (pinfunction "4_4") (pintype "passive"))
    )
    (net (code "53") (name "DIN_SM") (class "Default")
      (node (ref "IC3") (pin "6") (pinfunction "RC1/CN45/RPI38_6") (pintype "bidirectional"))
      (node (ref "U1") (pin "27") (pinfunction "DIN_27") (pintype "bidirectional"))
    )
    (net (code "54") (name "DOOR2_L") (class "Default")
      (node (ref "IC3") (pin "50") (pinfunction "CN18/RP17/RF5_50") (pintype "bidirectional"))
      (node (ref "R29") (pin "2") (pinfunction "1_2") (pintype "passive"))
      (node (ref "R29") (pin "3") (pinfunction "1_3") (pintype "passive"))
    )
    (net (code "55") (name "DOOR2_L_SW") (class "Default")
      (node (ref "C36") (pin "1") (pinfunction "1_1") (pintype "passive"))
      (node (ref "J19") (pin "2") (pinfunction "2_2") (pintype "bidirectional"))
      (node (ref "R27") (pin "2") (pinfunction "2_2") (pintype "passive"))
      (node (ref "R29") (pin "7") (pinfunction "2_7") (pintype "passive"))
    )
    (net (code "56") (name "DOOR2_R") (class "Default")
      (node (ref "IC3") (pin "55") (pinfunction "CN72/RPI45/RF6_55") (pintype "bidirectional"))
      (node (ref "R29") (pin "1") (pinfunction "1_1") (pintype "passive"))
      (node (ref "R29") (pin "4") (pinfunction "1_4") (pintype "passive"))
    )
    (net (code "57") (name "DOOR2_R_SW") (class "Default")
      (node (ref "C47") (pin "1") (pinfunction "1_1") (pintype "passive"))
      (node (ref "J19") (pin "4") (pinfunction "4_4") (pintype "bidirectional"))
      (node (ref "R28") (pin "2") (pinfunction "2_2") (pintype "passive"))
      (node (ref "R29") (pin "8") (pinfunction "2_8") (pintype "passive"))
    )
    (net (code "58") (name "DOOR_L") (class "Default")
      (node (ref "IC3") (pin "73") (pinfunction "RC13/SOSCI/CN1_73") (pintype "bidirectional"))
      (node (ref "R21") (pin "2") (pinfunction "1_2") (pintype "passive"))
      (node (ref "R21") (pin "3") (pinfunction "1_3") (pintype "passive"))
    )
    (net (code "59") (name "DOOR_L_SW") (class "Default")
      (node (ref "C25") (pin "1") (pinfunction "1_1") (pintype "passive"))
      (node (ref "J19") (pin "6") (pinfunction "6_6") (pintype "bidirectional"))
      (node (ref "R18") (pin "2") (pinfunction "2_2") (pintype "passive"))
      (node (ref "R21") (pin "7") (pinfunction "2_7") (pintype "passive"))
    )
    (net (code "60") (name "DOOR_ON") (class "Default")
      (node (ref "IC3") (pin "87") (pinfunction "CN68/RF0_87") (pintype "bidirectional"))
      (node (ref "Q5") (pin "5") (pinfunction "Q1G_5") (pintype "input"))
      (node (ref "R20") (pin "7") (pinfunction "2_7") (pintype "passive"))
    )
    (net (code "61") (name "DOOR_R") (class "Default")
      (node (ref "IC3") (pin "91") (pinfunction "RA6/CN39_91") (pintype "bidirectional"))
      (node (ref "R21") (pin "1") (pinfunction "1_1") (pintype "passive"))
      (node (ref "R21") (pin "4") (pinfunction "1_4") (pintype "passive"))
    )
    (net (code "62") (name "DOOR_R_SW") (class "Default")
      (node (ref "C26") (pin "1") (pinfunction "1_1") (pintype "passive"))
      (node (ref "J19") (pin "8") (pinfunction "8_8") (pintype "bidirectional"))
      (node (ref "R19") (pin "2") (pinfunction "2_2") (pintype "passive"))
      (node (ref "R21") (pin "8") (pinfunction "2_8") (pintype "passive"))
    )
    (net (code "63") (name "DOUT_SM_B") (class "Default")
      (node (ref "IC3") (pin "7") (pinfunction "RC2/CN46/RPI39_7") (pintype "bidirectional"))
      (node (ref "U1") (pin "28") (pinfunction "DOUT_28") (pintype "bidirectional"))
    )
    (net (code "64") (name "ID1_L_N") (class "Default")
      (node (ref "C31") (pin "2") (pinfunction "2_2") (pintype "passive"))
      (node (ref "IC9") (pin "3") (pinfunction "FB_3") (pintype "input"))
      (node (ref "J14") (pin "1") (pinfunction "1_1") (pintype "passive"))
      (node (ref "J18") (pin "8") (pinfunction "8_8") (pintype "bidirectional"))
      (node (ref "R26") (pin "1") (pinfunction "1_1") (pintype "passive"))
    )
    (net (code "65") (name "ID_L_P") (class "Default")
      (node (ref "C31") (pin "1") (pinfunction "1_1") (pintype "passive"))
      (node (ref "C32") (pin "1") (pinfunction "1_1") (pintype "passive"))
      (node (ref "D3") (pin "A") (pinfunction "A_A") (pintype "passive"))
      (node (ref "J14") (pin "2") (pinfunction "2_2") (pintype "passive"))
      (node (ref "J18") (pin "7") (pinfunction "7_7") (pintype "bidirectional"))
      (node (ref "L3") (pin "2") (pinfunction "2_2") (pintype "passive"))
    )
    (net (code "66") (name "ID_PWM") (class "Default")
      (node (ref "IC3") (pin "51") (pinfunction "CN71/RP16/RF3_51") (pintype "bidirectional"))
      (node (ref "R23") (pin "1") (pinfunction "1_1") (pintype "passive"))
    )
    (net (code "67") (name "IOB") (class "Default")
      (node (ref "J10") (pin "C7") (pinfunction "C7_C7") (pintype "bidirectional"))
      (node (ref "U1") (pin "20") (pinfunction "IOB_20") (pintype "bidirectional"))
    )
    (net (code "68") (name "ISENSEA") (class "Default")
      (node (ref "IC19") (pin "1") (pinfunction "OUT_1") (pintype "output"))
      (node (ref "IC19") (pin "2") (pinfunction "-IN_2") (pintype "input"))
      (node (ref "IC3") (pin "43") (pinfunction "RB14/AN14/CN32/RP14_43") (pintype "bidirectional"))
    )
    (net (code "69") (name "ISEN_OP_EN") (class "Default")
      (node (ref "C134") (pin "1") (pinfunction "1_1") (pintype "passive"))
      (node (ref "IC19") (pin "8") (pinfunction "V+_8") (pintype "power_in"))
      (node (ref "IC3") (pin "68") (pinfunction "CN53/RP2/RD8_68") (pintype "bidirectional"))
    )
    (net (code "70") (name "LD_SM") (class "Default")
      (node (ref "IC3") (pin "9") (pinfunction "RC4/CN48/RPI41_9") (pintype "bidirectional"))
      (node (ref "U1") (pin "25") (pinfunction "/LD_25") (pintype "bidirectional"))
    )
    (net (code "71") (name "MICROPHONE") (class "Default")
      (node (ref "J17") (pin "2") (pinfunction "2_2") (pintype "bidirectional"))
      (node (ref "J48") (pin "2") (pinfunction "2_2") (pintype "passive"))
      (node (ref "R207") (pin "2") (pinfunction "2_2") (pintype "passive"))
      (node (ref "R208") (pin "1") (pinfunction "1_1") (pintype "passive"))
      (node (ref "U9") (pin "3") (pinfunction "+IN_3") (pintype "input"))
    )
    (net (code "72") (name "MIC_AMP_EN") (class "Default")
      (node (ref "IC3") (pin "96") (pinfunction "CN79/RG12_96") (pintype "bidirectional"))
      (node (ref "J49") (pin "1") (pinfunction "1_1") (pintype "passive"))
      (node (ref "Q24") (pin "1") (pinfunction "G_1") (pintype "passive"))
      (node (ref "R210") (pin "1") (pinfunction "1_1") (pintype "passive"))
      (node (ref "U9") (pin "5") (pinfunction "~{SHDN}_5") (pintype "power_in"))
    )
    (net (code "73") (name "N$5") (class "Default")
      (node (ref "J15") (pin "6") (pinfunction "6_6") (pintype "bidirectional"))
      (node (ref "J15") (pin "6A") (pinfunction "6_6A") (pintype "bidirectional"))
      (node (ref "J15") (pin "8") (pinfunction "8_8") (pintype "bidirectional"))
      (node (ref "J15") (pin "8A") (pinfunction "8_8A") (pintype "bidirectional"))
      (node (ref "R38") (pin "2") (pinfunction "2_2") (pintype "passive"))
    )
    (net (code "74") (name "N$10") (class "Default")
      (node (ref "IC19") (pin "3") (pinfunction "+IN_3") (pintype "input"))
      (node (ref "IC19") (pin "5") (pinfunction "+IN_5") (pintype "input"))
      (node (ref "Q14") (pin "3") (pinfunction "OUT_3") (pintype "output"))
    )
    (net (code "75") (name "N$41") (class "Default")
      (node (ref "J15") (pin "2") (pinfunction "2_2") (pintype "bidirectional"))
      (node (ref "J15") (pin "2A") (pinfunction "2_2A") (pintype "bidirectional"))
      (node (ref "J15") (pin "4") (pinfunction "4_4") (pintype "bidirectional"))
      (node (ref "J15") (pin "4A") (pinfunction "4_4A") (pintype "bidirectional"))
      (node (ref "R39") (pin "2") (pinfunction "2_2") (pintype "passive"))
    )
    (net (code "76") (name "Net-(C164-Pad1)") (class "Default")
      (node (ref "C164") (pin "1") (pinfunction "1_1") (pintype "passive"))
      (node (ref "R193") (pin "1") (pinfunction "1_1") (pintype "passive"))
    )
    (net (code "77") (name "Net-(C171-Pad1)") (class "Default")
      (node (ref "C171") (pin "1") (pinfunction "1_1") (pintype "passive"))
      (node (ref "R16") (pin "1") (pinfunction "1_1") (pintype "passive"))
      (node (ref "R198") (pin "1") (pinfunction "1_1") (pintype "passive"))
      (node (ref "U8") (pin "7") (pinfunction "AVCC_7") (pintype "power_in"))
    )
    (net (code "78") (name "Net-(C185-Pad2)") (class "Default")
      (node (ref "C185") (pin "2") (pinfunction "2_2") (pintype "passive"))
      (node (ref "R211") (pin "1") (pinfunction "1_1") (pintype "passive"))
    )
    (net (code "79") (name "Net-(D2-K)") (class "Default")
      (node (ref "C30") (pin "1") (pinfunction "1_1") (pintype "passive"))
      (node (ref "D2") (pin "C") (pinfunction "K_C") (pintype "passive"))
      (node (ref "D3") (pin "C") (pinfunction "K_C") (pintype "passive"))
      (node (ref "IC9") (pin "1") (pinfunction "BOOST_1") (pintype "input"))
    )
    (net (code "80") (name "Net-(D17-A)") (class "Default")
      (node (ref "D17") (pin "2") (pinfunction "A_2") (pintype "passive"))
      (node (ref "R151") (pin "1") (pinfunction "1_1") (pintype "passive"))
    )
    (net (code "81") (name "Net-(D17-K)") (class "Default")
      (node (ref "D17") (pin "1+") (pinfunction "K_1+") (pintype "passive"))
      (node (ref "IC18") (pin "22") (pinfunction "GPIO0_22") (pintype "output"))
    )
    (net (code "82") (name "Net-(D19-A)") (class "Default")
      (node (ref "D19") (pin "2") (pinfunction "A_2") (pintype "passive"))
      (node (ref "R152") (pin "1") (pinfunction "1_1") (pintype "passive"))
    )
    (net (code "83") (name "Net-(D19-K)") (class "Default")
      (node (ref "D19") (pin "1+") (pinfunction "K_1+") (pintype "passive"))
      (node (ref "IC18") (pin "23") (pinfunction "GPIO1_23") (pintype "output"))
    )
    (net (code "84") (name "Net-(D23-A)") (class "Default")
      (node (ref "D23") (pin "2") (pinfunction "A_2") (pintype "passive"))
      (node (ref "R175") (pin "1") (pinfunction "1_1") (pintype "passive"))
    )
    (net (code "85") (name "Net-(D24-A)") (class "Default")
      (node (ref "D24") (pin "2") (pinfunction "A_2") (pintype "passive"))
      (node (ref "R176") (pin "1") (pinfunction "1_1") (pintype "passive"))
    )
    (net (code "86") (name "Net-(IC1-VIN)") (class "Default")
      (node (ref "C23") (pin "1") (pinfunction "1_1") (pintype "passive"))
      (node (ref "C59") (pin "1") (pinfunction "1_1") (pintype "passive"))
      (node (ref "IC1") (pin "1") (pinfunction "VIN_1") (pintype "power_in"))
      (node (ref "R37") (pin "1") (pinfunction "1_1") (pintype "passive"))
    )
    (net (code "87") (name "Net-(IC3-AVDD)") (class "Default")
      (node (ref "C3") (pin "1") (pinfunction "1_1") (pintype "passive"))
      (node (ref "C7") (pin "1") (pinfunction "1_1") (pintype "passive"))
      (node (ref "IC3") (pin "30") (pinfunction "AVDD_30") (pintype "power_in"))
      (node (ref "R1") (pin "1") (pinfunction "1_1") (pintype "passive"))
    )
    (net (code "88") (name "Net-(IC3-OSC1{slash}CLKI{slash}RC12)") (class "Default")
      (node (ref "C18") (pin "2") (pinfunction "2_2") (pintype "passive"))
      (node (ref "IC3") (pin "63") (pinfunction "OSC1/CLKI/RC12_63") (pintype "bidirectional"))
      (node (ref "Q4") (pin "3") (pinfunction "2_3") (pintype "passive"))
    )
    (net (code "89") (name "Net-(IC3-OSC2{slash}CLKO{slash}RC15)") (class "Default")
      (node (ref "C19") (pin "2") (pinfunction "2_2") (pintype "passive"))
      (node (ref "IC3") (pin "64") (pinfunction "OSC2/CLKO/RC15_64") (pintype "bidirectional"))
      (node (ref "Q4") (pin "1") (pinfunction "1_1") (pintype "passive"))
    )
    (net (code "90") (name "Net-(IC3-RA4{slash}TDI{slash}CN37)") (class "Default")
      (node (ref "IC3") (pin "60") (pinfunction "RA4/TDI/CN37_60") (pintype "bidirectional"))
      (node (ref "TP2") (pin "P$1") (pinfunction "TP_P$1") (pintype "passive"))
    )
    (net (code "91") (name "Net-(IC3-RB10{slash}AN10{slash}CN28{slash}CVREF)") (class "Default")
      (node (ref "IC3") (pin "34") (pinfunction "RB10/AN10/CN28/CVREF_34") (pintype "bidirectional"))
      (node (ref "TP3") (pin "P$1") (pinfunction "TP_P$1") (pintype "passive"))
    )
    (net (code "92") (name "Net-(IC3-VDDCORE)") (class "Default")
      (node (ref "C10") (pin "2") (pinfunction "2_2") (pintype "passive"))
      (node (ref "C38") (pin "2") (pinfunction "2_2") (pintype "passive"))
      (node (ref "IC3") (pin "85") (pinfunction "VDDCORE_85") (pintype "passive"))
    )
    (net (code "93") (name "Net-(IC4-VDD)") (class "Default")
      (node (ref "C21") (pin "1") (pinfunction "1_1") (pintype "passive"))
      (node (ref "IC4") (pin "5") (pinfunction "VDD_5") (pintype "power_in"))
      (node (ref "J12") (pin "2") (pinfunction "2_2") (pintype "passive"))
      (node (ref "R15") (pin "1") (pinfunction "1_1") (pintype "passive"))
    )
    (net (code "94") (name "Net-(IC9-EN{slash}DIM)") (class "Default")
      (node (ref "C34") (pin "1") (pinfunction "1_1") (pintype "passive"))
      (node (ref "IC9") (pin "4") (pinfunction "EN/DIM_4") (pintype "input"))
      (node (ref "R23") (pin "2") (pinfunction "2_2") (pintype "passive"))
    )
    (net (code "95") (name "Net-(IC9-SW)") (class "Default")
      (node (ref "C30") (pin "2") (pinfunction "2_2") (pintype "passive"))
      (node (ref "D4") (pin "K") (pinfunction "K_K") (pintype "passive"))
      (node (ref "IC9") (pin "6") (pinfunction "SW_6") (pintype "output"))
      (node (ref "L3") (pin "1") (pinfunction "1_1") (pintype "passive"))
    )
    (net (code "96") (name "Net-(IC18-VCC30)") (class "Default")
      (node (ref "C121") (pin "2") (pinfunction "2_2") (pintype "passive"))
      (node (ref "IC18") (pin "17") (pinfunction "VCC30_17") (pintype "power_in"))
      (node (ref "IC18") (pin "4") (pinfunction "VCCIO_4") (pintype "power_in"))
      (node (ref "TP60") (pin "P$1") (pinfunction "TP_P$1") (pintype "passive"))
    )
    (net (code "97") (name "Net-(IC19B--IN)") (class "Default")
      (node (ref "IC19") (pin "6") (pinfunction "-IN_6") (pintype "input"))
      (node (ref "IC19") (pin "7") (pinfunction "OUT_7") (pintype "output"))
    )
    (net (code "98") (name "Net-(IC21-ITH)") (class "Default")
      (node (ref "IC21") (pin "2") (pinfunction "ITH_2") (pintype "input"))
      (node (ref "R193") (pin "2") (pinfunction "2_2") (pintype "passive"))
    )
    (net (code "99") (name "Net-(IC21-PGATE)") (class "Default")
      (node (ref "IC21") (pin "5") (pinfunction "PGATE_5") (pintype "output"))
      (node (ref "Q23") (pin "1") (pinfunction "G_1") (pintype "passive"))
    )
    (net (code "100") (name "Net-(IC21-SENSE)") (class "Default")
      (node (ref "C155") (pin "2") (pinfunction "2_2") (pintype "passive"))
      (node (ref "IC21") (pin "7") (pinfunction "SENSE_7") (pintype "input"))
      (node (ref "Q23") (pin "2") (pinfunction "S_2") (pintype "passive"))
      (node (ref "R189") (pin "1") (pinfunction "1_1") (pintype "passive"))
    )
    (net (code "101") (name "Net-(IC21-VFB)") (class "Default")
      (node (ref "C160") (pin "1") (pinfunction "1_1") (pintype "passive"))
      (node (ref "IC21") (pin "3") (pinfunction "VFB_3") (pintype "input"))
      (node (ref "R194") (pin "2") (pinfunction "2_2") (pintype "passive"))
      (node (ref "R197") (pin "1") (pinfunction "1_1") (pintype "passive"))
    )
    (net (code "102") (name "Net-(J45-Pad2)") (class "Default")
      (node (ref "J45") (pin "2") (pinfunction "2_2") (pintype "passive"))
      (node (ref "R46") (pin "2") (pinfunction "2_2") (pintype "passive"))
    )
    (net (code "103") (name "Net-(J45-Pad3)") (class "Default")
      (node (ref "J45") (pin "3") (pinfunction "3_3") (pintype "passive"))
      (node (ref "R45") (pin "2") (pinfunction "2_2") (pintype "passive"))
    )
    (net (code "104") (name "Net-(Q2-Q2G)") (class "Default")
      (node (ref "Q2") (pin "6") (pinfunction "Q2G_6") (pintype "input"))
      (node (ref "R3") (pin "2") (pinfunction "2_2") (pintype "passive"))
    )
    (net (code "105") (name "Net-(Q5-Q2D1)") (class "Default")
      (node (ref "Q5") (pin "2") (pinfunction "Q2D1_2") (pintype "bidirectional"))
      (node (ref "Q5") (pin "3") (pinfunction "Q2D2_3") (pintype "bidirectional"))
      (node (ref "R18") (pin "1") (pinfunction "1_1") (pintype "passive"))
      (node (ref "R19") (pin "1") (pinfunction "1_1") (pintype "passive"))
      (node (ref "R27") (pin "1") (pinfunction "1_1") (pintype "passive"))
      (node (ref "R28") (pin "1") (pinfunction "1_1") (pintype "passive"))
    )
    (net (code "106") (name "Net-(Q5-Q2G)") (class "Default")
      (node (ref "Q5") (pin "6") (pinfunction "Q2G_6") (pintype "input"))
      (node (ref "R20") (pin "3") (pinfunction "1_3") (pintype "passive"))
    )
    (net (code "107") (name "Net-(Q14-VIN+)") (class "Default")
      (node (ref "C187") (pin "+") (pinfunction "+_+") (pintype "passive"))
      (node (ref "D32") (pin "C") (pinfunction "C_C") (pintype "passive"))
      (node (ref "F3") (pin "2") (pinfunction "2_2") (pintype "passive"))
      (node (ref "Q14") (pin "5") (pinfunction "VIN+_5") (pintype "input"))
      (node (ref "R154") (pin "1") (pinfunction "1_1") (pintype "passive"))
      (node (ref "R40") (pin "1") (pinfunction "1_1") (pintype "passive"))
      (node (ref "R41") (pin "1") (pinfunction "1_1") (pintype "passive"))
      (node (ref "TP63") (pin "TP") (pinfunction "TP_TP") (pintype "input"))
    )
    (net (code "108") (name "Net-(Q15A-D)") (class "Default")
      (node (ref "Q15") (pin "7") (pinfunction "D_7") (pintype "passive"))
      (node (ref "Q15") (pin "8") (pinfunction "D1_8") (pintype "passive"))
      (node (ref "R159") (pin "1") (pinfunction "1_1") (pintype "passive"))
    )
    (net (code "109") (name "Net-(Q15B-D)") (class "Default")
      (node (ref "C122") (pin "1") (pinfunction "1_1") (pintype "passive"))
      (node (ref "C123") (pin "1") (pinfunction "1_1") (pintype "passive"))
      (node (ref "C125") (pin "1") (pinfunction "1_1") (pintype "passive"))
      (node (ref "Q15") (pin "5") (pinfunction "D_5") (pintype "passive"))
      (node (ref "Q15") (pin "6") (pinfunction "D1_6") (pintype "passive"))
      (node (ref "R157") (pin "2") (pinfunction "2_2") (pintype "passive"))
      (node (ref "R42") (pin "1") (pinfunction "1_1") (pintype "passive"))
      (node (ref "R43") (pin "1") (pinfunction "1_1") (pintype "passive"))
      (node (ref "U6") (pin "7") (pinfunction "VIN_7") (pintype "power_in"))
    )
    (net (code "110") (name "Net-(Q15B-G)") (class "Default")
      (node (ref "Q15") (pin "4") (pinfunction "G_4") (pintype "passive"))
      (node (ref "R156") (pin "1") (pinfunction "1_1") (pintype "passive"))
      (node (ref "R159") (pin "2") (pinfunction "2_2") (pintype "passive"))
    )
    (net (code "111") (name "Net-(Q18A-D)") (class "Default")
      (node (ref "Q18") (pin "7") (pinfunction "D_7") (pintype "passive"))
      (node (ref "Q18") (pin "8") (pinfunction "D1_8") (pintype "passive"))
      (node (ref "R173") (pin "2") (pinfunction "2_2") (pintype "passive"))
    )
    (net (code "112") (name "Net-(Q18B-D)") (class "Default")
      (node (ref "C136") (pin "1") (pinfunction "1_1") (pintype "passive"))
      (node (ref "C137") (pin "1") (pinfunction "1_1") (pintype "passive"))
      (node (ref "C139") (pin "1") (pinfunction "1_1") (pintype "passive"))
      (node (ref "Q18") (pin "5") (pinfunction "D_5") (pintype "passive"))
      (node (ref "Q18") (pin "6") (pinfunction "D1_6") (pintype "passive"))
      (node (ref "R171") (pin "2") (pinfunction "2_2") (pintype "passive"))
      (node (ref "R44") (pin "1") (pinfunction "1_1") (pintype "passive"))
      (node (ref "U7") (pin "7") (pinfunction "VIN_7") (pintype "power_in"))
    )
    (net (code "113") (name "Net-(Q18B-G)") (class "Default")
      (node (ref "Q18") (pin "4") (pinfunction "G_4") (pintype "passive"))
      (node (ref "R170") (pin "2") (pinfunction "2_2") (pintype "passive"))
      (node (ref "R173") (pin "1") (pinfunction "1_1") (pintype "passive"))
    )
    (net (code "114") (name "Net-(Q23-D)") (class "Default")
      (node (ref "D30") (pin "K") (pinfunction "K_K") (pintype "passive"))
      (node (ref "L14") (pin "1") (pinfunction "1_1") (pintype "passive"))
      (node (ref "Q23") (pin "3") (pinfunction "D_3") (pintype "passive"))
    )
    (net (code "115") (name "Net-(Q24-D)") (class "Default")
      (node (ref "Q24") (pin "3") (pinfunction "D_3") (pintype "passive"))
      (node (ref "R208") (pin "2") (pinfunction "2_2") (pintype "passive"))
    )
    (net (code "116") (name "Net-(R16-Pad2)") (class "Default")
      (node (ref "R16") (pin "2") (pinfunction "2_2") (pintype "passive"))
      (node (ref "U8") (pin "14") (pinfunction "AVCC_14") (pintype "power_in"))
    )
    (net (code "117") (name "Net-(TP69-TP)") (class "Default")
      (node (ref "R204") (pin "2") (pinfunction "2_2") (pintype "passive"))
      (node (ref "TP69") (pin "1") (pinfunction "TP_1") (pintype "passive"))
    )
    (net (code "118") (name "Net-(U1--UNDERV)") (class "Default")
      (node (ref "R12") (pin "1") (pinfunction "1_1") (pintype "passive"))
      (node (ref "U1") (pin "23") (pinfunction "-UNDERV_23") (pintype "bidirectional"))
    )
    (net (code "119") (name "Net-(U1-C+)") (class "Default")
      (node (ref "C15") (pin "2") (pinfunction "2_2") (pintype "passive"))
      (node (ref "U1") (pin "14") (pinfunction "C+_14") (pintype "bidirectional"))
    )
    (net (code "120") (name "Net-(U1-C-)") (class "Default")
      (node (ref "C15") (pin "1") (pinfunction "1_1") (pintype "passive"))
      (node (ref "U1") (pin "11") (pinfunction "C-_11") (pintype "bidirectional"))
    )
    (net (code "121") (name "Net-(U1-CLKB)") (class "Default")
      (node (ref "J10") (pin "C3") (pinfunction "C3_C3") (pintype "bidirectional"))
      (node (ref "U1") (pin "18") (pinfunction "CLKB_18") (pintype "bidirectional"))
    )
    (net (code "122") (name "Net-(U1-CPO)") (class "Default")
      (node (ref "C20") (pin "2") (pinfunction "2_2") (pintype "passive"))
      (node (ref "U1") (pin "15") (pinfunction "CPO_15") (pintype "bidirectional"))
    )
    (net (code "123") (name "Net-(U1-NC{slash}-NO)") (class "Default")
      (node (ref "R13") (pin "2") (pinfunction "2_2") (pintype "passive"))
      (node (ref "U1") (pin "22") (pinfunction "NC/-NO_22") (pintype "bidirectional"))
    )
    (net (code "124") (name "Net-(U1-RSTB)") (class "Default")
      (node (ref "J10") (pin "C2") (pinfunction "C2_C2") (pintype "bidirectional"))
      (node (ref "U1") (pin "19") (pinfunction "RSTB_19") (pintype "bidirectional"))
    )
    (net (code "125") (name "Net-(U1-VCCB)") (class "Default")
      (node (ref "J10") (pin "C1") (pinfunction "C1_C1") (pintype "bidirectional"))
      (node (ref "U1") (pin "17") (pinfunction "VCCB_17") (pintype "bidirectional"))
    )
    (net (code "126") (name "Net-(U3-AIN0)") (class "Default")
      (node (ref "C39") (pin "1") (pinfunction "1_1") (pintype "passive"))
      (node (ref "R33") (pin "1") (pinfunction "1_1") (pintype "passive"))
      (node (ref "R34") (pin "2") (pinfunction "2_2") (pintype "passive"))
      (node (ref "U3") (pin "4") (pinfunction "AIN0_4") (pintype "bidirectional"))
    )
    (net (code "127") (name "Net-(U3-AIN2)") (class "Default")
      (node (ref "C41") (pin "1") (pinfunction "1_1") (pintype "passive"))
      (node (ref "R35") (pin "1") (pinfunction "1_1") (pintype "passive"))
      (node (ref "R36") (pin "2") (pinfunction "2_2") (pintype "passive"))
      (node (ref "U3") (pin "6") (pinfunction "AIN2_6") (pintype "bidirectional"))
    )
    (net (code "128") (name "Net-(U9--IN)") (class "Default")
      (node (ref "C185") (pin "1") (pinfunction "1_1") (pintype "passive"))
      (node (ref "C186") (pin "1") (pinfunction "1_1") (pintype "passive"))
      (node (ref "R209") (pin "2") (pinfunction "2_2") (pintype "passive"))
      (node (ref "U9") (pin "4") (pinfunction "-IN_4") (pintype "input"))
    )
    (net (code "129") (name "Net-(U9-OUT)") (class "Default")
      (node (ref "C183") (pin "1") (pinfunction "1_1") (pintype "passive"))
      (node (ref "C184") (pin "1") (pinfunction "1_1") (pintype "passive"))
      (node (ref "C186") (pin "2") (pinfunction "2_2") (pintype "passive"))
      (node (ref "R209") (pin "1") (pinfunction "1_1") (pintype "passive"))
      (node (ref "U9") (pin "1") (pinfunction "OUT_1") (pintype "output"))
    )
    (net (code "130") (name "OUTN_UNF") (class "Default")
      (node (ref "C178") (pin "2") (pinfunction "2_2") (pintype "passive"))
      (node (ref "L16") (pin "2") (pinfunction "2_2") (pintype "passive"))
      (node (ref "U8") (pin "23") (pinfunction "OUTN_23") (pintype "output"))
      (node (ref "U8") (pin "25") (pinfunction "OUTN_25") (pintype "output"))
    )
    (net (code "131") (name "OUTP_UNF") (class "Default")
      (node (ref "C173") (pin "2") (pinfunction "2_2") (pintype "passive"))
      (node (ref "L15") (pin "2") (pinfunction "2_2") (pintype "passive"))
      (node (ref "U8") (pin "18") (pinfunction "OUTP_18") (pintype "output"))
      (node (ref "U8") (pin "20") (pinfunction "OUTP_20") (pintype "output"))
    )
    (net (code "132") (name "OUT_S1") (class "Default")
      (node (ref "D23") (pin "1+") (pinfunction "K_1+") (pintype "passive"))
      (node (ref "D25") (pin "A") (pinfunction "A_A") (pintype "passive"))
      (node (ref "J15") (pin "12") (pinfunction "12_12") (pintype "bidirectional"))
      (node (ref "J15") (pin "12A") (pinfunction "12_12A") (pintype "bidirectional"))
      (node (ref "Q20") (pin "3") (pinfunction "D_3") (pintype "passive"))
    )
    (net (code "133") (name "OUT_S2") (class "Default")
      (node (ref "D24") (pin "1+") (pinfunction "K_1+") (pintype "passive"))
      (node (ref "D26") (pin "A") (pinfunction "A_A") (pintype "passive"))
      (node (ref "J16") (pin "2") (pinfunction "2_2") (pintype "bidirectional"))
      (node (ref "J16") (pin "2A") (pinfunction "2_2A") (pintype "bidirectional"))
      (node (ref "Q21") (pin "3") (pinfunction "D_3") (pintype "passive"))
    )
    (net (code "134") (name "P12V") (class "Default")
      (node (ref "C128") (pin "1") (pinfunction "1_1") (pintype "passive"))
      (node (ref "C129") (pin "1") (pinfunction "1_1") (pintype "passive"))
      (node (ref "C130") (pin "1") (pinfunction "1_1") (pintype "passive"))
      (node (ref "C165") (pin "1") (pinfunction "1_1") (pintype "passive"))
      (node (ref "C166") (pin "1") (pinfunction "1_1") (pintype "passive"))
      (node (ref "C167") (pin "1") (pinfunction "1_1") (pintype "passive"))
      (node (ref "C168") (pin "1") (pinfunction "1_1") (pintype "passive"))
      (node (ref "C169") (pin "1") (pinfunction "1_1") (pintype "passive"))
      (node (ref "C170") (pin "1") (pinfunction "1_1") (pintype "passive"))
      (node (ref "C44") (pin "+") (pinfunction "+_+") (pintype "passive"))
      (node (ref "D20") (pin "K") (pinfunction "K_K") (pintype "passive"))
      (node (ref "J18") (pin "3") (pinfunction "3_3") (pintype "bidirectional"))
      (node (ref "J50") (pin "3") (pinfunction "3_3") (pintype "bidirectional"))
      (node (ref "J50") (pin "4") (pinfunction "4_4") (pintype "bidirectional"))
      (node (ref "Q16") (pin "1_2") (pinfunction "VIN_1_2") (pintype "passive"))
      (node (ref "R160") (pin "2") (pinfunction "2_2") (pintype "passive"))
      (node (ref "R198") (pin "2") (pinfunction "2_2") (pintype "passive"))
      (node (ref "TP61") (pin "TP") (pinfunction "TP_TP") (pintype "input"))
      (node (ref "U8") (pin "15") (pinfunction "PVCC_15") (pintype "power_in"))
      (node (ref "U8") (pin "16") (pinfunction "PVCC_16") (pintype "power_in"))
      (node (ref "U8") (pin "27") (pinfunction "PVCC_27") (pintype "power_in"))
      (node (ref "U8") (pin "28") (pinfunction "PVCC_28") (pintype "power_in"))
    )
    (net (code "135") (name "PGC") (class "Default")
      (node (ref "IC3") (pin "26") (pinfunction "RB6/AN6/PGC2/RP6_26") (pintype "bidirectional"))
      (node (ref "J11") (pin "5") (pinfunction "5_5") (pintype "passive"))
    )
    (net (code "136") (name "PGD") (class "Default")
      (node (ref "IC3") (pin "27") (pinfunction "RB7/AN7/PGD2/RP7_27") (pintype "bidirectional"))
      (node (ref "J11") (pin "4") (pinfunction "4_4") (pintype "passive"))
    )
    (net (code "137") (name "PHOTOCELL") (class "Default")
      (node (ref "R7") (pin "2") (pinfunction "2_2") (pintype "passive"))
      (node (ref "R8") (pin "2") (pinfunction "2_2") (pintype "passive"))
      (node (ref "TP6") (pin "P$1") (pinfunction "TP_P$1") (pintype "passive"))
    )
    (net (code "138") (name "PHOTO_PIN") (class "Default")
      (node (ref "IC3") (pin "24") (pinfunction "RB1/AN1/CN3/PGC1/RP1_24") (pintype "bidirectional"))
      (node (ref "R8") (pin "1") (pinfunction "1_1") (pintype "passive"))
    )
    (net (code "139") (name "PHOTO_PWR") (class "Default")
      (node (ref "IC3") (pin "25") (pinfunction "RB0/AN0/CN2/PGD1/RP0_25") (pintype "bidirectional"))
      (node (ref "R7") (pin "1") (pinfunction "1_1") (pintype "passive"))
    )
    (net (code "140") (name "PIC_INT") (class "Default")
      (node (ref "IC3") (pin "38") (pinfunction "RA1/TCK_38") (pintype "bidirectional"))
      (node (ref "J1") (pin "3") (pinfunction "3_3") (pintype "passive"))
    )
    (net (code "141") (name "RTC_CS") (class "Default")
      (node (ref "IC3") (pin "79") (pinfunction "CN57/RPI42/RD12_79") (pintype "bidirectional"))
    )
    (net (code "142") (name "RTC_INT") (class "Default")
      (node (ref "IC3") (pin "80") (pinfunction "CN19/RD13_80") (pintype "bidirectional"))
    )
    (net (code "143") (name "SBC_5V_VBUS") (class "Default")
      (node (ref "C114") (pin "2") (pinfunction "2_2") (pintype "passive"))
      (node (ref "C115") (pin "2") (pinfunction "2_2") (pintype "passive"))
      (node (ref "IC18") (pin "19") (pinfunction "/RESET_19") (pintype "bidirectional"))
      (node (ref "IC18") (pin "20") (pinfunction "VCC5I_20") (pintype "power_in"))
      (node (ref "J41") (pin "3") (pinfunction "3_3") (pintype "passive"))
      (node (ref "R151") (pin "2") (pinfunction "2_2") (pintype "passive"))
      (node (ref "R152") (pin "2") (pinfunction "2_2") (pintype "passive"))
      (node (ref "X2") (pin "1") (pinfunction "1_1") (pintype "passive"))
    )
    (net (code "144") (name "SBC_LINL") (class "Default")
      (node (ref "C184") (pin "2") (pinfunction "2_2") (pintype "passive"))
      (node (ref "J17") (pin "4") (pinfunction "4_4") (pintype "bidirectional"))
      (node (ref "J47") (pin "6") (pinfunction "6_6") (pintype "passive"))
    )
    (net (code "145") (name "SBC_LINR") (class "Default")
      (node (ref "C183") (pin "2") (pinfunction "2_2") (pintype "passive"))
      (node (ref "J17") (pin "5") (pinfunction "5_5") (pintype "bidirectional"))
      (node (ref "J47") (pin "2") (pinfunction "2_2") (pintype "passive"))
    )
    (net (code "146") (name "SBC_LOUTL") (class "Default")
      (node (ref "C175") (pin "1") (pinfunction "1_1") (pintype "passive"))
      (node (ref "J17") (pin "7") (pinfunction "7_7") (pintype "bidirectional"))
      (node (ref "J47") (pin "5") (pinfunction "5_5") (pintype "passive"))
    )
    (net (code "147") (name "SBC_LOUTR") (class "Default")
      (node (ref "C174") (pin "1") (pinfunction "1_1") (pintype "passive"))
      (node (ref "J17") (pin "8") (pinfunction "8_8") (pintype "bidirectional"))
      (node (ref "J47") (pin "1") (pinfunction "1_1") (pintype "passive"))
    )
    (net (code "148") (name "SBC_USB_B_D_N") (class "Default")
      (node (ref "IC18") (pin "16") (pinfunction "USBDM_16") (pintype "bidirectional"))
      (node (ref "X2") (pin "2") (pinfunction "2_2") (pintype "passive"))
    )
    (net (code "149") (name "SBC_USB_B_D_P") (class "Default")
      (node (ref "IC18") (pin "15") (pinfunction "USBDP_15") (pintype "bidirectional"))
      (node (ref "X2") (pin "3") (pinfunction "3_3") (pintype "passive"))
    )
    (net (code "150") (name "SCL1") (class "Default")
      (node (ref "IC3") (pin "57") (pinfunction "RG2/SCL1/CN83_57") (pintype "bidirectional"))
      (node (ref "IC5") (pin "2") (pinfunction "SCL_2") (pintype "input"))
      (node (ref "IC6") (pin "6") (pinfunction "SCL_6") (pintype "input"))
      (node (ref "J8") (pin "16") (pinfunction "16_16") (pintype "passive"))
      (node (ref "R30") (pin "2") (pinfunction "2_2") (pintype "passive"))
      (node (ref "R32") (pin "1") (pinfunction "1_1") (pintype "passive"))
      (node (ref "U3") (pin "1") (pinfunction "ADDR_1") (pintype "bidirectional"))
      (node (ref "U3") (pin "10") (pinfunction "SCL_10") (pintype "bidirectional"))
    )
    (net (code "151") (name "SCLK1") (class "Default")
      (node (ref "IC3") (pin "77") (pinfunction "CN51/RP23/RD2_77") (pintype "bidirectional"))
      (node (ref "IC8") (pin "6") (pinfunction "C_6") (pintype "input"))
    )
    (net (code "152") (name "SCLK2") (class "Default")
      (node (ref "IC3") (pin "10") (pinfunction "RG6/CN8/RP21_10") (pintype "bidirectional"))
      (node (ref "J1") (pin "5") (pinfunction "5_5") (pintype "passive"))
      (node (ref "J8") (pin "12") (pinfunction "12_12") (pintype "passive"))
      (node (ref "U1") (pin "31") (pinfunction "ASYNC_31") (pintype "bidirectional"))
    )
    (net (code "153") (name "SCLK_SM_B") (class "Default")
      (node (ref "IC3") (pin "8") (pinfunction "RC3/CN47/RPI40_8") (pintype "bidirectional"))
      (node (ref "U1") (pin "26") (pinfunction "SCLK_26") (pintype "bidirectional"))
    )
    (net (code "154") (name "SDA1") (class "Default")
      (node (ref "IC3") (pin "56") (pinfunction "RG3/SDA1/CN84_56") (pintype "bidirectional"))
      (node (ref "IC5") (pin "1") (pinfunction "SDA_1") (pintype "bidirectional"))
      (node (ref "IC6") (pin "5") (pinfunction "SDA_5") (pintype "bidirectional"))
      (node (ref "J8") (pin "15") (pinfunction "15_15") (pintype "passive"))
      (node (ref "R25") (pin "2") (pinfunction "2_2") (pintype "passive"))
      (node (ref "R31") (pin "1") (pinfunction "1_1") (pintype "passive"))
      (node (ref "U3") (pin "9") (pinfunction "SDA_9") (pintype "bidirectional"))
    )
    (net (code "155") (name "SDI1") (class "Default")
      (node (ref "IC3") (pin "72") (pinfunction "CN49/RP11/RD0_72") (pintype "bidirectional"))
      (node (ref "IC8") (pin "2") (pinfunction "Q_2") (pintype "bidirectional"))
    )
    (net (code "156") (name "SDI2") (class "Default")
      (node (ref "IC3") (pin "11") (pinfunction "RG7/CN9/RP26_11") (pintype "bidirectional"))
      (node (ref "J1") (pin "8") (pinfunction "8_8") (pintype "passive"))
      (node (ref "J8") (pin "11") (pinfunction "11_11") (pintype "passive"))
    )
    (net (code "157") (name "SDO1") (class "Default")
      (node (ref "IC3") (pin "76") (pinfunction "CN50/RP24/RD1_76") (pintype "bidirectional"))
      (node (ref "IC8") (pin "5") (pinfunction "D_5") (pintype "input"))
    )
    (net (code "158") (name "SDO2") (class "Default")
      (node (ref "IC3") (pin "12") (pinfunction "CN10/RP19/RG8_12") (pintype "bidirectional"))
      (node (ref "J1") (pin "6") (pinfunction "6_6") (pintype "passive"))
      (node (ref "J8") (pin "14") (pinfunction "14_14") (pintype "passive"))
    )
    (net (code "159") (name "SMB_SCL") (class "Default")
      (node (ref "D31") (pin "6") (pinfunction "AK_6") (pintype "passive"))
      (node (ref "IC3") (pin "66") (pinfunction "RA14/RPI36/CN43_66") (pintype "bidirectional"))
      (node (ref "R190") (pin "1") (pinfunction "1_1") (pintype "passive"))
      (node (ref "R46") (pin "1") (pinfunction "1_1") (pintype "passive"))
    )
    (net (code "160") (name "SMB_SDA") (class "Default")
      (node (ref "D31") (pin "3") (pinfunction "AK_3") (pintype "passive"))
      (node (ref "IC3") (pin "67") (pinfunction "RA15/RPI35/CN44_67") (pintype "bidirectional"))
      (node (ref "R187") (pin "1") (pinfunction "1_1") (pintype "passive"))
      (node (ref "R45") (pin "1") (pinfunction "1_1") (pintype "passive"))
    )
    (net (code "161") (name "SM_C4A") (class "Default")
      (node (ref "J3") (pin "2") (pinfunction "2_2") (pintype "bidirectional"))
      (node (ref "U1") (pin "4") (pinfunction "C4A_4") (pintype "bidirectional"))
      (node (ref "X1") (pin "2") (pinfunction "1_2") (pintype "passive"))
    )
    (net (code "162") (name "SM_C8A") (class "Default")
      (node (ref "J3") (pin "1") (pinfunction "1_1") (pintype "bidirectional"))
      (node (ref "U1") (pin "3") (pinfunction "C8A_3") (pintype "bidirectional"))
      (node (ref "X1") (pin "1") (pinfunction "1_1") (pintype "passive"))
    )
    (net (code "163") (name "SM_CLK_A") (class "Default")
      (node (ref "J3") (pin "4") (pinfunction "4_4") (pintype "bidirectional"))
      (node (ref "U1") (pin "7") (pinfunction "CLKA_7") (pintype "bidirectional"))
      (node (ref "X1") (pin "4") (pinfunction "1_4") (pintype "passive"))
    )
    (net (code "164") (name "SM_DATA") (class "Default")
      (node (ref "IC3") (pin "14") (pinfunction "CN11/RP27/RG9_14") (pintype "bidirectional"))
      (node (ref "U1") (pin "29") (pinfunction "DATA_29") (pintype "bidirectional"))
    )
    (net (code "165") (name "SM_DET_A") (class "Default")
      (node (ref "J3") (pin "10") (pinfunction "10_10") (pintype "bidirectional"))
      (node (ref "U1") (pin "2") (pinfunction "PRESA_2") (pintype "bidirectional"))
      (node (ref "X1") (pin "10") (pinfunction "1_10") (pintype "passive"))
    )
    (net (code "166") (name "SM_IO_A") (class "Default")
      (node (ref "J3") (pin "3") (pinfunction "3_3") (pintype "bidirectional"))
      (node (ref "U1") (pin "5") (pinfunction "IOA_5") (pintype "bidirectional"))
      (node (ref "X1") (pin "3") (pinfunction "1_3") (pintype "passive"))
    )
    (net (code "167") (name "SM_RST") (class "Default")
      (node (ref "IC3") (pin "5") (pinfunction "CN65/SDA3/RE7_5") (pintype "bidirectional"))
      (node (ref "U1") (pin "30") (pinfunction "RIN_30") (pintype "bidirectional"))
    )
    (net (code "168") (name "SM_RST_A") (class "Default")
      (node (ref "J3") (pin "6") (pinfunction "6_6") (pintype "bidirectional"))
      (node (ref "U1") (pin "6") (pinfunction "RSTA_6") (pintype "bidirectional"))
      (node (ref "X1") (pin "6") (pinfunction "1_6") (pintype "passive"))
    )
    (net (code "169") (name "SM_SYNC") (class "Default")
      (node (ref "IC3") (pin "4") (pinfunction "CN64/SCL3/RE6_4") (pintype "bidirectional"))
      (node (ref "U1") (pin "32") (pinfunction "SYNC_32") (pintype "bidirectional"))
    )
    (net (code "170") (name "SM_VCC_A") (class "Default")
      (node (ref "J3") (pin "9") (pinfunction "9_9") (pintype "bidirectional"))
      (node (ref "U1") (pin "8") (pinfunction "VCCA_8") (pintype "bidirectional"))
      (node (ref "X1") (pin "9") (pinfunction "1_9") (pintype "passive"))
    )
    (net (code "171") (name "SPKR1_P") (class "Default")
      (node (ref "C176") (pin "1") (pinfunction "1_1") (pintype "passive"))
      (node (ref "J17") (pin "11") (pinfunction "11_11") (pintype "bidirectional"))
      (node (ref "J4") (pin "1") (pinfunction "1_1") (pintype "passive"))
      (node (ref "L15") (pin "1") (pinfunction "1_1") (pintype "passive"))
    )
    (net (code "172") (name "SPKR_N") (class "Default")
      (node (ref "C179") (pin "1") (pinfunction "1_1") (pintype "passive"))
      (node (ref "J17") (pin "10") (pinfunction "10_10") (pintype "bidirectional"))
      (node (ref "J4") (pin "2") (pinfunction "2_2") (pintype "passive"))
      (node (ref "L16") (pin "1") (pinfunction "1_1") (pintype "passive"))
    )
    (net (code "173") (name "STRIKE_EN") (class "Default")
      (node (ref "IC3") (pin "47") (pinfunction "CN20/RPI43/RD14_47") (pintype "bidirectional"))
      (node (ref "Q18") (pin "2") (pinfunction "G_2") (pintype "passive"))
      (node (ref "R174") (pin "1") (pinfunction "1_1") (pintype "passive"))
      (node (ref "R179") (pin "2") (pinfunction "2_2") (pintype "passive"))
      (node (ref "U7") (pin "15") (pinfunction "EN_15") (pintype "input"))
    )
    (net (code "174") (name "STR_BOOT") (class "Default")
      (node (ref "C140") (pin "1") (pinfunction "1_1") (pintype "passive"))
      (node (ref "U7") (pin "11") (pinfunction "BOOT_11") (pintype "passive"))
    )
    (net (code "175") (name "STR_COMP") (class "Default")
      (node (ref "C146") (pin "1") (pinfunction "1_1") (pintype "passive"))
      (node (ref "R181") (pin "2") (pinfunction "2_2") (pintype "passive"))
      (node (ref "U7") (pin "3") (pinfunction "COMP_3") (pintype "passive"))
    )
    (net (code "176") (name "STR_FB") (class "Default")
      (node (ref "R177") (pin "1") (pinfunction "1_1") (pintype "passive"))
      (node (ref "R185") (pin "2") (pinfunction "2_2") (pintype "passive"))
      (node (ref "U7") (pin "4") (pinfunction "FB_4") (pintype "input"))
    )
    (net (code "177") (name "STR_FEED") (class "Default")
      (node (ref "L12") (pin "2") (pinfunction "2_2") (pintype "passive"))
      (node (ref "R172") (pin "2") (pinfunction "2_2") (pintype "passive"))
      (node (ref "R44") (pin "2") (pinfunction "2_2") (pintype "passive"))
    )
    (net (code "178") (name "STR_HDRV") (class "Default")
      (node (ref "R178") (pin "2") (pinfunction "2_2") (pintype "passive"))
      (node (ref "U7") (pin "13") (pinfunction "HDRV_13") (pintype "output"))
    )
    (net (code "179") (name "STR_HG1") (class "Default")
      (node (ref "Q19") (pin "3") (pinfunction "TG_3") (pintype "passive"))
      (node (ref "R178") (pin "1") (pinfunction "1_1") (pintype "passive"))
    )
    (net (code "180") (name "STR_ISNS+") (class "Default")
      (node (ref "C138") (pin "1") (pinfunction "1_1") (pintype "passive"))
      (node (ref "R171") (pin "1") (pinfunction "1_1") (pintype "passive"))
      (node (ref "U7") (pin "6") (pinfunction "ISNS+_6") (pintype "input"))
    )
    (net (code "181") (name "STR_ISNS-") (class "Default")
      (node (ref "C138") (pin "2") (pinfunction "2_2") (pintype "passive"))
      (node (ref "R172") (pin "1") (pinfunction "1_1") (pintype "passive"))
      (node (ref "U7") (pin "5") (pinfunction "ISNS-_5") (pintype "input"))
    )
    (net (code "182") (name "STR_L") (class "Default")
      (node (ref "D22") (pin "A") (pinfunction "A_A") (pintype "passive"))
      (node (ref "L12") (pin "1") (pinfunction "1_1") (pintype "passive"))
      (node (ref "Q19") (pin "6") (pinfunction "VSW_6") (pintype "passive"))
      (node (ref "Q19") (pin "7") (pinfunction "VSW_7") (pintype "passive"))
      (node (ref "Q19") (pin "8") (pinfunction "VSW_8") (pintype "passive"))
    )
    (net (code "183") (name "STR_LDRV") (class "Default")
      (node (ref "R180") (pin "2") (pinfunction "2_2") (pintype "passive"))
      (node (ref "U7") (pin "8") (pinfunction "LDRV_8") (pintype "output"))
    )
    (net (code "184") (name "STR_LG1") (class "Default")
      (node (ref "Q19") (pin "5") (pinfunction "BG_5") (pintype "passive"))
      (node (ref "R180") (pin "1") (pinfunction "1_1") (pintype "passive"))
    )
    (net (code "185") (name "STR_PG") (class "Default")
      (node (ref "IC3") (pin "74") (pinfunction "RC14/SOSCO/CN0/RPI37_74") (pintype "bidirectional"))
      (node (ref "R186") (pin "1") (pinfunction "1_1") (pintype "passive"))
      (node (ref "U7") (pin "14") (pinfunction "PGOOD_14") (pintype "open_collector"))
    )
    (net (code "186") (name "STR_RC") (class "Default")
      (node (ref "C148") (pin "1") (pinfunction "1_1") (pintype "passive"))
      (node (ref "R181") (pin "1") (pinfunction "1_1") (pintype "passive"))
    )
    (net (code "187") (name "STR_RT") (class "Default")
      (node (ref "R182") (pin "2") (pinfunction "2_2") (pintype "passive"))
      (node (ref "U7") (pin "1") (pinfunction "RT/CLK_1") (pintype "passive"))
    )
    (net (code "188") (name "STR_SS") (class "Default")
      (node (ref "C147") (pin "1") (pinfunction "1_1") (pintype "passive"))
      (node (ref "U7") (pin "2") (pinfunction "SS_2") (pintype "passive"))
    )
    (net (code "189") (name "STR_SW") (class "Default")
      (node (ref "C140") (pin "2") (pinfunction "2_2") (pintype "passive"))
      (node (ref "Q19") (pin "4") (pinfunction "TGR_4") (pintype "passive"))
      (node (ref "U7") (pin "12") (pinfunction "SW_12") (pintype "output"))
    )
    (net (code "190") (name "STR_VCC") (class "Default")
      (node (ref "C141") (pin "1") (pinfunction "1_1") (pintype "passive"))
      (node (ref "U7") (pin "10") (pinfunction "VCC_10") (pintype "output"))
    )
    (net (code "191") (name "U1RX") (class "Default")
      (node (ref "IC18") (pin "1") (pinfunction "TXD_1") (pintype "output"))
      (node (ref "IC3") (pin "70") (pinfunction "CN55/RP3/RD10_70") (pintype "bidirectional"))
      (node (ref "J41") (pin "4") (pinfunction "4_4") (pintype "passive"))
    )
    (net (code "192") (name "U1TX") (class "Default")
      (node (ref "IC18") (pin "5") (pinfunction "RXD_5") (pintype "input"))
      (node (ref "IC3") (pin "71") (pinfunction "CN56/RP12/RD11_71") (pintype "bidirectional"))
      (node (ref "J41") (pin "5") (pinfunction "5_5") (pintype "passive"))
    )
    (net (code "193") (name "U2CTL") (class "Default")
      (node (ref "IC2") (pin "2") (pinfunction "/RE_2") (pintype "input"))
      (node (ref "IC2") (pin "3") (pinfunction "DE_3") (pintype "input"))
      (node (ref "IC3") (pin "19") (pinfunction "RPI34/CN67/RE9_19") (pintype "bidirectional"))
    )
    (net (code "194") (name "U2RX") (class "Default")
      (node (ref "IC2") (pin "1") (pinfunction "R_1") (pintype "output"))
      (node (ref "IC3") (pin "81") (pinfunction "CN13/RP25/RD4_81") (pintype "bidirectional"))
    )
    (net (code "195") (name "U2TX") (class "Default")
      (node (ref "IC2") (pin "4") (pinfunction "D_4") (pintype "input"))
      (node (ref "IC3") (pin "82") (pinfunction "CN14/RP20/RD5_82") (pintype "bidirectional"))
    )
    (net (code "196") (name "U3RX") (class "Default")
      (node (ref "IC3") (pin "23") (pinfunction "RB2/AN2/CN4/RP13_23") (pintype "bidirectional"))
      (node (ref "J2") (pin "3") (pinfunction "3_3") (pintype "passive"))
      (node (ref "JP1") (pin "3") (pinfunction "3_3") (pintype "passive"))
    )
    (net (code "197") (name "U3TX") (class "Default")
      (node (ref "IC3") (pin "33") (pinfunction "RB9/AN9/CN27/RP9_33") (pintype "bidirectional"))
      (node (ref "J2") (pin "4") (pinfunction "4_4") (pintype "passive"))
      (node (ref "JP1") (pin "4") (pinfunction "4_4") (pintype "passive"))
    )
    (net (code "198") (name "US-S_O") (class "Default")
      (node (ref "IC3") (pin "78") (pinfunction "CN52/RP22/RD3_78") (pintype "bidirectional"))
      (node (ref "J18") (pin "11") (pinfunction "11_11") (pintype "bidirectional"))
      (node (ref "J30") (pin "5") (pinfunction "SERIAL_5") (pintype "bidirectional"))
    )
    (net (code "199") (name "USRF_EN") (class "Default")
      (node (ref "IC3") (pin "97") (pinfunction "CN80/RG13_97") (pintype "bidirectional"))
      (node (ref "J18") (pin "12") (pinfunction "12_12") (pintype "bidirectional"))
      (node (ref "J30") (pin "4") (pinfunction "EN_4") (pintype "bidirectional"))
    )
    (net (code "200") (name "VACT") (class "Default")
      (node (ref "C142") (pin "1") (pinfunction "1_1") (pintype "passive"))
      (node (ref "C143") (pin "1") (pinfunction "1_1") (pintype "passive"))
      (node (ref "C144") (pin "1") (pinfunction "1_1") (pintype "passive"))
      (node (ref "C145") (pin "1") (pinfunction "1_1") (pintype "passive"))
      (node (ref "C43") (pin "+") (pinfunction "+_+") (pintype "passive"))
      (node (ref "D21") (pin "+") (pinfunction "C_+") (pintype "passive"))
      (node (ref "D22") (pin "K") (pinfunction "K_K") (pintype "passive"))
      (node (ref "D25") (pin "C") (pinfunction "K_C") (pintype "passive"))
      (node (ref "D26") (pin "C") (pinfunction "K_C") (pintype "passive"))
      (node (ref "J15") (pin "11") (pinfunction "11_11") (pintype "bidirectional"))
      (node (ref "J15") (pin "11A") (pinfunction "11_11A") (pintype "bidirectional"))
      (node (ref "J16") (pin "1") (pinfunction "1_1") (pintype "bidirectional"))
      (node (ref "J16") (pin "1A") (pinfunction "1_1A") (pintype "bidirectional"))
      (node (ref "J18") (pin "1") (pinfunction "1_1") (pintype "bidirectional"))
      (node (ref "Q19") (pin "1_2") (pinfunction "VIN_1_2") (pintype "passive"))
      (node (ref "R175") (pin "2") (pinfunction "2_2") (pintype "passive"))
      (node (ref "R176") (pin "2") (pinfunction "2_2") (pintype "passive"))
      (node (ref "R177") (pin "2") (pinfunction "2_2") (pintype "passive"))
      (node (ref "TP62") (pin "TP") (pinfunction "TP_TP") (pintype "input"))
    )
    (net (code "201") (name "VPS_ON") (class "Default")
      (node (ref "IC3") (pin "100") (pinfunction "CN62/RE4_100") (pintype "bidirectional"))
      (node (ref "Q2") (pin "5") (pinfunction "Q1G_5") (pintype "input"))
      (node (ref "R5") (pin "2") (pinfunction "2_2") (pintype "passive"))
    )
    (net (code "202") (name "VPS_PWR") (class "Default")
      (node (ref "J7") (pin "5") (pinfunction "5_5") (pintype "passive"))
      (node (ref "J9") (pin "5") (pinfunction "5_5") (pintype "passive"))
      (node (ref "Q2") (pin "2") (pinfunction "Q2D1_2") (pintype "bidirectional"))
      (node (ref "Q2") (pin "3") (pinfunction "Q2D2_3") (pintype "bidirectional"))
      (node (ref "R4") (pin "2") (pinfunction "2_2") (pintype "passive"))
    )
    (net (code "203") (name "VPS_SEN") (class "Default")
      (node (ref "IC3") (pin "99") (pinfunction "CN61/RE3_99") (pintype "bidirectional"))
      (node (ref "R4") (pin "1") (pinfunction "1_1") (pintype "passive"))
      (node (ref "R6") (pin "2") (pinfunction "2_2") (pintype "passive"))
    )
    (net (code "204") (name "VREF2.5") (class "Default")
      (node (ref "C4") (pin "1") (pinfunction "1_1") (pintype "passive"))
      (node (ref "IC1") (pin "2") (pinfunction "VOUT_2") (pintype "output"))
      (node (ref "IC3") (pin "29") (pinfunction "RA10/VR+/CN42_29") (pintype "bidirectional"))
      (node (ref "TP1") (pin "P$1") (pinfunction "TP_P$1") (pintype "passive"))
    )
    (net (code "205") (name "VSOLAR") (class "Default")
      (node (ref "J1") (pin "2") (pinfunction "2_2") (pintype "passive"))
    )
    (net (code "206") (name "XB_RTS") (class "Default")
      (node (ref "IC3") (pin "48") (pinfunction "CN21/RP5/RD15_48") (pintype "bidirectional"))
      (node (ref "J2") (pin "7") (pinfunction "7_7") (pintype "passive"))
    )
    (net (code "207") (name "XB_SLEEP") (class "Default")
      (node (ref "IC3") (pin "22") (pinfunction "RB3/AN3/CN5_22") (pintype "bidirectional"))
      (node (ref "J2") (pin "5") (pinfunction "5_5") (pintype "passive"))
      (node (ref "JP1") (pin "5") (pinfunction "5_5") (pintype "passive"))
    )
    (net (code "208") (name "unconnected-(IC3-CN15{slash}RD6-Pad83)") (class "Default")
      (node (ref "IC3") (pin "83") (pinfunction "CN15/RD6_83") (pintype "bidirectional"))
    )
    (net (code "209") (name "unconnected-(IC3-CN17{slash}RP10{slash}RF4-Pad49)") (class "Default")
      (node (ref "IC3") (pin "49") (pinfunction "CN17/RP10/RF4_49") (pintype "bidirectional"))
    )
    (net (code "210") (name "unconnected-(IC3-CN58{slash}RE0-Pad93)") (class "Default")
      (node (ref "IC3") (pin "93") (pinfunction "CN58/RE0_93") (pintype "bidirectional"))
    )
    (net (code "211") (name "unconnected-(IC3-CN60{slash}RE2-Pad98)") (class "Default")
      (node (ref "IC3") (pin "98") (pinfunction "CN60/RE2_98") (pintype "bidirectional"))
    )
    (net (code "212") (name "unconnected-(IC3-CN69{slash}RF1-Pad88)") (class "Default")
      (node (ref "IC3") (pin "88") (pinfunction "CN69/RF1_88") (pintype "bidirectional"))
    )
    (net (code "213") (name "unconnected-(IC3-CN73{slash}RPI44{slash}RF7-Pad54)") (class "Default")
      (node (ref "IC3") (pin "54") (pinfunction "CN73/RPI44/RF7_54") (pintype "bidirectional"))
    )
    (net (code "214") (name "unconnected-(IC3-CN76{slash}RP31{slash}RF13-Pad39)") (class "Default")
      (node (ref "IC3") (pin "39") (pinfunction "CN76/RP31/RF13_39") (pintype "bidirectional"))
    )
    (net (code "215") (name "unconnected-(IC3-RA2{slash}SCL2-Pad58)") (class "Default")
      (node (ref "IC3") (pin "58") (pinfunction "RA2/SCL2_58") (pintype "bidirectional"))
    )
    (net (code "216") (name "unconnected-(IC3-RA3{slash}SDA2-Pad59)") (class "Default")
      (node (ref "IC3") (pin "59") (pinfunction "RA3/SDA2_59") (pintype "bidirectional"))
    )
    (net (code "217") (name "unconnected-(IC3-RB8{slash}AN8{slash}CN26{slash}RP8-Pad32)") (class "Default")
      (node (ref "IC3") (pin "32") (pinfunction "RB8/AN8/CN26/RP8_32") (pintype "bidirectional"))
    )
    (net (code "218") (name "unconnected-(IC3-RB11{slash}AN11{slash}CN29-Pad35)") (class "Default")
      (node (ref "IC3") (pin "35") (pinfunction "RB11/AN11/CN29_35") (pintype "bidirectional"))
    )
    (net (code "219") (name "unconnected-(IC3-RB15{slash}AN15{slash}CN12{slash}RP29-Pad44)") (class "Default")
      (node (ref "IC3") (pin "44") (pinfunction "RB15/AN15/CN12/RP29_44") (pintype "bidirectional"))
    )
    (net (code "220") (name "unconnected-(IC5-OS-Pad3)") (class "Default")
      (node (ref "IC5") (pin "3") (pinfunction "OS_3") (pintype "output"))
    )
    (net (code "221") (name "unconnected-(IC18-AVCC-NC-Pad24)") (class "Default")
      (node (ref "IC18") (pin "24") (pinfunction "AVCC-NC_24") (pintype "no_connect"))
    )
    (net (code "222") (name "unconnected-(IC18-GPIO2-Pad13)") (class "Default")
      (node (ref "IC18") (pin "13") (pinfunction "GPIO2_13") (pintype "output"))
    )
    (net (code "223") (name "unconnected-(IC18-GPIO3-Pad14)") (class "Default")
      (node (ref "IC18") (pin "14") (pinfunction "GPIO3_14") (pintype "bidirectional"))
    )
    (net (code "224") (name "unconnected-(IC18-OSCI-Pad27)") (class "Default")
      (node (ref "IC18") (pin "27") (pinfunction "OSCI_27") (pintype "bidirectional"))
    )
    (net (code "225") (name "unconnected-(IC18-OSCO-Pad28)") (class "Default")
      (node (ref "IC18") (pin "28") (pinfunction "OSCO_28") (pintype "output"))
    )
    (net (code "226") (name "unconnected-(IC18-VCC3I-NC-Pad8)") (class "Default")
      (node (ref "IC18") (pin "8") (pinfunction "VCC3I-NC_8") (pintype "no_connect"))
    )
    (net (code "227") (name "unconnected-(IC18-{slash}DCD-Pad10)") (class "Default")
      (node (ref "IC18") (pin "10") (pinfunction "/DCD_10") (pintype "bidirectional"))
    )
    (net (code "228") (name "unconnected-(IC18-{slash}DSR-Pad9)") (class "Default")
      (node (ref "IC18") (pin "9") (pinfunction "/DSR_9") (pintype "bidirectional"))
    )
    (net (code "229") (name "unconnected-(IC18-{slash}DTR-Pad2)") (class "Default")
      (node (ref "IC18") (pin "2") (pinfunction "/DTR_2") (pintype "output"))
    )
    (net (code "230") (name "unconnected-(IC18-{slash}RI-Pad6)") (class "Default")
      (node (ref "IC18") (pin "6") (pinfunction "/RI_6") (pintype "bidirectional"))
    )
    (net (code "231") (name "unconnected-(IC18-{slash}SLEEP-Pad12)") (class "Default")
      (node (ref "IC18") (pin "12") (pinfunction "/SLEEP_12") (pintype "bidirectional"))
    )
    (net (code "232") (name "unconnected-(J8-Pad1)") (class "Default")
      (node (ref "J8") (pin "1") (pinfunction "1_1") (pintype "passive"))
    )
    (net (code "233") (name "unconnected-(J8-Pad2)") (class "Default")
      (node (ref "J8") (pin "2") (pinfunction "2_2") (pintype "passive"))
    )
    (net (code "234") (name "unconnected-(J8-Pad3)") (class "Default")
      (node (ref "J8") (pin "3") (pinfunction "3_3") (pintype "passive"))
    )
    (net (code "235") (name "unconnected-(J8-Pad4)") (class "Default")
      (node (ref "J8") (pin "4") (pinfunction "4_4") (pintype "passive"))
    )
    (net (code "236") (name "unconnected-(J8-Pad5)") (class "Default")
      (node (ref "J8") (pin "5") (pinfunction "5_5") (pintype "passive"))
    )
    (net (code "237") (name "unconnected-(J8-Pad6)") (class "Default")
      (node (ref "J8") (pin "6") (pinfunction "6_6") (pintype "passive"))
    )
    (net (code "238") (name "unconnected-(J8-Pad7)") (class "Default")
      (node (ref "J8") (pin "7") (pinfunction "7_7") (pintype "passive"))
    )
    (net (code "239") (name "unconnected-(J8-Pad8)") (class "Default")
      (node (ref "J8") (pin "8") (pinfunction "8_8") (pintype "passive"))
    )
    (net (code "240") (name "unconnected-(J10-PadC4)") (class "Default")
      (node (ref "J10") (pin "C4") (pinfunction "C4_C4") (pintype "bidirectional"))
    )
    (net (code "241") (name "unconnected-(J10-PadC6)") (class "Default")
      (node (ref "J10") (pin "C6") (pinfunction "C6_C6") (pintype "bidirectional"))
    )
    (net (code "242") (name "unconnected-(J10-PadC8)") (class "Default")
      (node (ref "J10") (pin "C8") (pinfunction "C8_C8") (pintype "bidirectional"))
    )
    (net (code "243") (name "unconnected-(J30-AN{slash}O-Pad3)") (class "Default")
      (node (ref "J30") (pin "3") (pinfunction "AN/O_3") (pintype "bidirectional"))
    )
    (net (code "244") (name "unconnected-(J30-PWM-Pad2)") (class "Default")
      (node (ref "J30") (pin "2") (pinfunction "PWM_2") (pintype "bidirectional"))
    )
    (net (code "245") (name "unconnected-(J30-TEMP(NC)-Pad1)") (class "Default")
      (node (ref "J30") (pin "1") (pinfunction "TEMP(NC)_1") (pintype "bidirectional"))
    )
    (net (code "246") (name "unconnected-(J47-Pad7)") (class "Default")
      (node (ref "J47") (pin "7") (pinfunction "7_7") (pintype "passive"))
    )
    (net (code "247") (name "unconnected-(J47-Pad8)") (class "Default")
      (node (ref "J47") (pin "8") (pinfunction "8_8") (pintype "passive"))
    )
    (net (code "248") (name "unconnected-(J47-Pad9)") (class "Default")
      (node (ref "J47") (pin "9") (pinfunction "9_9") (pintype "passive"))
    )
    (net (code "249") (name "unconnected-(J47-Pad10)") (class "Default")
      (node (ref "J47") (pin "10") (pinfunction "10_10") (pintype "passive"))
    )
    (net (code "250") (name "unconnected-(JP1-Pad8)") (class "Default")
      (node (ref "JP1") (pin "8") (pinfunction "8_8") (pintype "passive"))
    )
    (net (code "251") (name "unconnected-(Q3-Pad4)") (class "Default")
      (node (ref "Q3") (pin "4") (pinfunction "4_4") (pintype "passive"))
    )
    (net (code "252") (name "unconnected-(U1-NC-Pad16)") (class "Default")
      (node (ref "U1") (pin "16") (pinfunction "NC_16") (pintype "bidirectional"))
    )
    (net (code "253") (name "unconnected-(U3-ALERT{slash}RDY-Pad2)") (class "Default")
      (node (ref "U3") (pin "2") (pinfunction "ALERT/RDY_2") (pintype "bidirectional"))
    )
    (net (code "254") (name "unconnected-(U8-NC-Pad13)") (class "Default")
      (node (ref "U8") (pin "13") (pinfunction "NC_13") (pintype "no_connect"))
    )
    (net (code "255") (name "unconnected-(X1F-1-Pad5)") (class "Default")
      (node (ref "X1") (pin "5") (pinfunction "1_5") (pintype "passive"))
    )
    (net (code "256") (name "{slash}3.3V1_ON") (class "Default")
      (node (ref "IC3") (pin "95") (pinfunction "CN81/RG14_95") (pintype "bidirectional"))
      (node (ref "Q7") (pin "2") (pinfunction "G_2") (pintype "passive"))
    )
    (net (code "257") (name "{slash}3.3V2_ON") (class "Default")
      (node (ref "IC3") (pin "94") (pinfunction "CN59/RE1_94") (pintype "bidirectional"))
      (node (ref "Q7") (pin "5") (pinfunction "G_5") (pintype "passive"))
    )
    (net (code "258") (name "{slash}3.3V3_ON") (class "Default")
      (node (ref "IC3") (pin "61") (pinfunction "RA5/TDO/CN38_61") (pintype "bidirectional"))
    )
    (net (code "259") (name "{slash}CL_CS1") (class "Default")
      (node (ref "IC3") (pin "1") (pinfunction "CN82/RG15_1") (pintype "bidirectional"))
      (node (ref "TP10") (pin "P$1") (pinfunction "TP_P$1") (pintype "passive"))
    )
    (net (code "260") (name "{slash}CL_CS2") (class "Default")
      (node (ref "IC3") (pin "17") (pinfunction "RA0/TMS_17") (pintype "bidirectional"))
      (node (ref "J1") (pin "7") (pinfunction "7_7") (pintype "passive"))
    )
    (net (code "261") (name "{slash}CTS") (class "Default")
      (node (ref "IC18") (pin "11") (pinfunction "/CTS_11") (pintype "bidirectional"))
      (node (ref "J41") (pin "2") (pinfunction "2_2") (pintype "passive"))
    )
    (net (code "262") (name "{slash}FMEM1_CS") (class "Default")
      (node (ref "IC3") (pin "28") (pinfunction "RA9/VR-/CN41_28") (pintype "bidirectional"))
      (node (ref "IC8") (pin "1") (pinfunction "/S_1") (pintype "input"))
      (node (ref "R24") (pin "2") (pinfunction "2_2") (pintype "passive"))
    )
    (net (code "263") (name "{slash}MCLR") (class "Default")
      (node (ref "IC3") (pin "13") (pinfunction "MCLR_13") (pintype "input"))
      (node (ref "IC4") (pin "4") (pinfunction "GP2/T0CK_4") (pintype "bidirectional"))
      (node (ref "J11") (pin "1") (pinfunction "1_1") (pintype "passive"))
      (node (ref "R14") (pin "1") (pinfunction "1_1") (pintype "passive"))
    )
    (net (code "264") (name "{slash}MCLR2") (class "Default")
      (node (ref "IC4") (pin "6") (pinfunction "GP3/MCLR_6") (pintype "bidirectional"))
      (node (ref "J12") (pin "1") (pinfunction "1_1") (pintype "passive"))
    )
    (net (code "265") (name "{slash}RAM_CS") (class "Default")
      (node (ref "IC3") (pin "3") (pinfunction "CN63/RE5_3") (pintype "bidirectional"))
      (node (ref "J8") (pin "13") (pinfunction "13_13") (pintype "passive"))
    )
    (net (code "266") (name "{slash}RTS") (class "Default")
      (node (ref "IC18") (pin "3") (pinfunction "/RTS_3") (pintype "output"))
      (node (ref "J41") (pin "6") (pinfunction "6_6") (pintype "passive"))
    )
    (net (code "267") (name "{slash}SM_FAULT") (class "Default")
      (node (ref "IC3") (pin "21") (pinfunction "RB4/AN4/CN6/RP28_21") (pintype "bidirectional"))
      (node (ref "U1") (pin "24") (pinfunction "-FAULT_24") (pintype "bidirectional"))
    )
    (net (code "268") (name "{slash}XB_RESET") (class "Default")
      (node (ref "IC3") (pin "18") (pinfunction "RPI33/CN66/RE8_18") (pintype "bidirectional"))
      (node (ref "J2") (pin "6") (pinfunction "6_6") (pintype "passive"))
      (node (ref "JP1") (pin "7") (pinfunction "7_7") (pintype "passive"))
    )
  )
)
